# Masters_Project.net
KiCad netlist of a schematic drawn in EAGLE
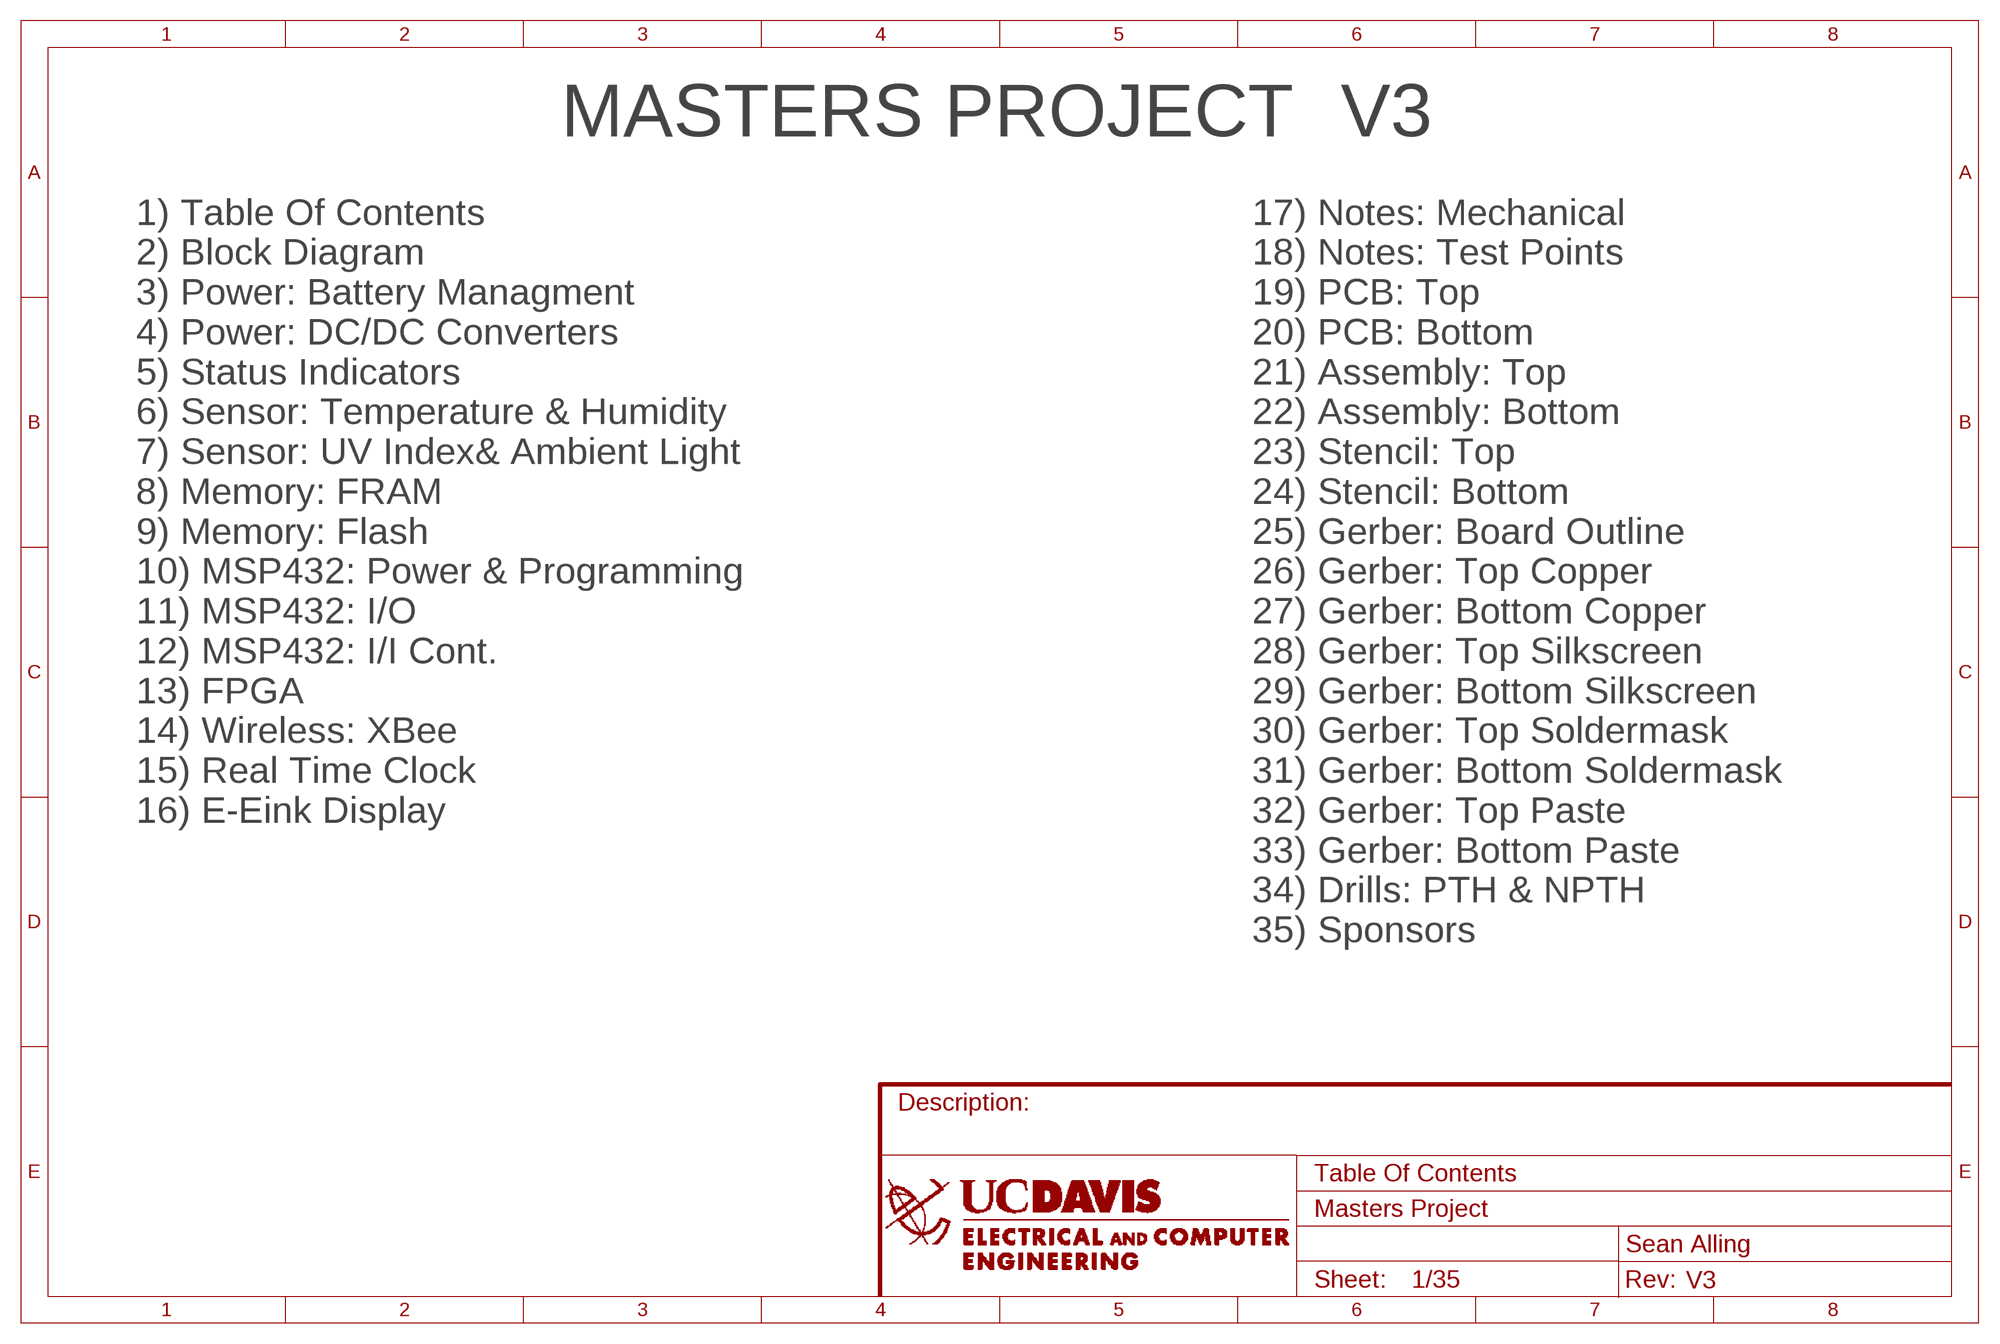
[diagram p0: schematic, sheet 1]
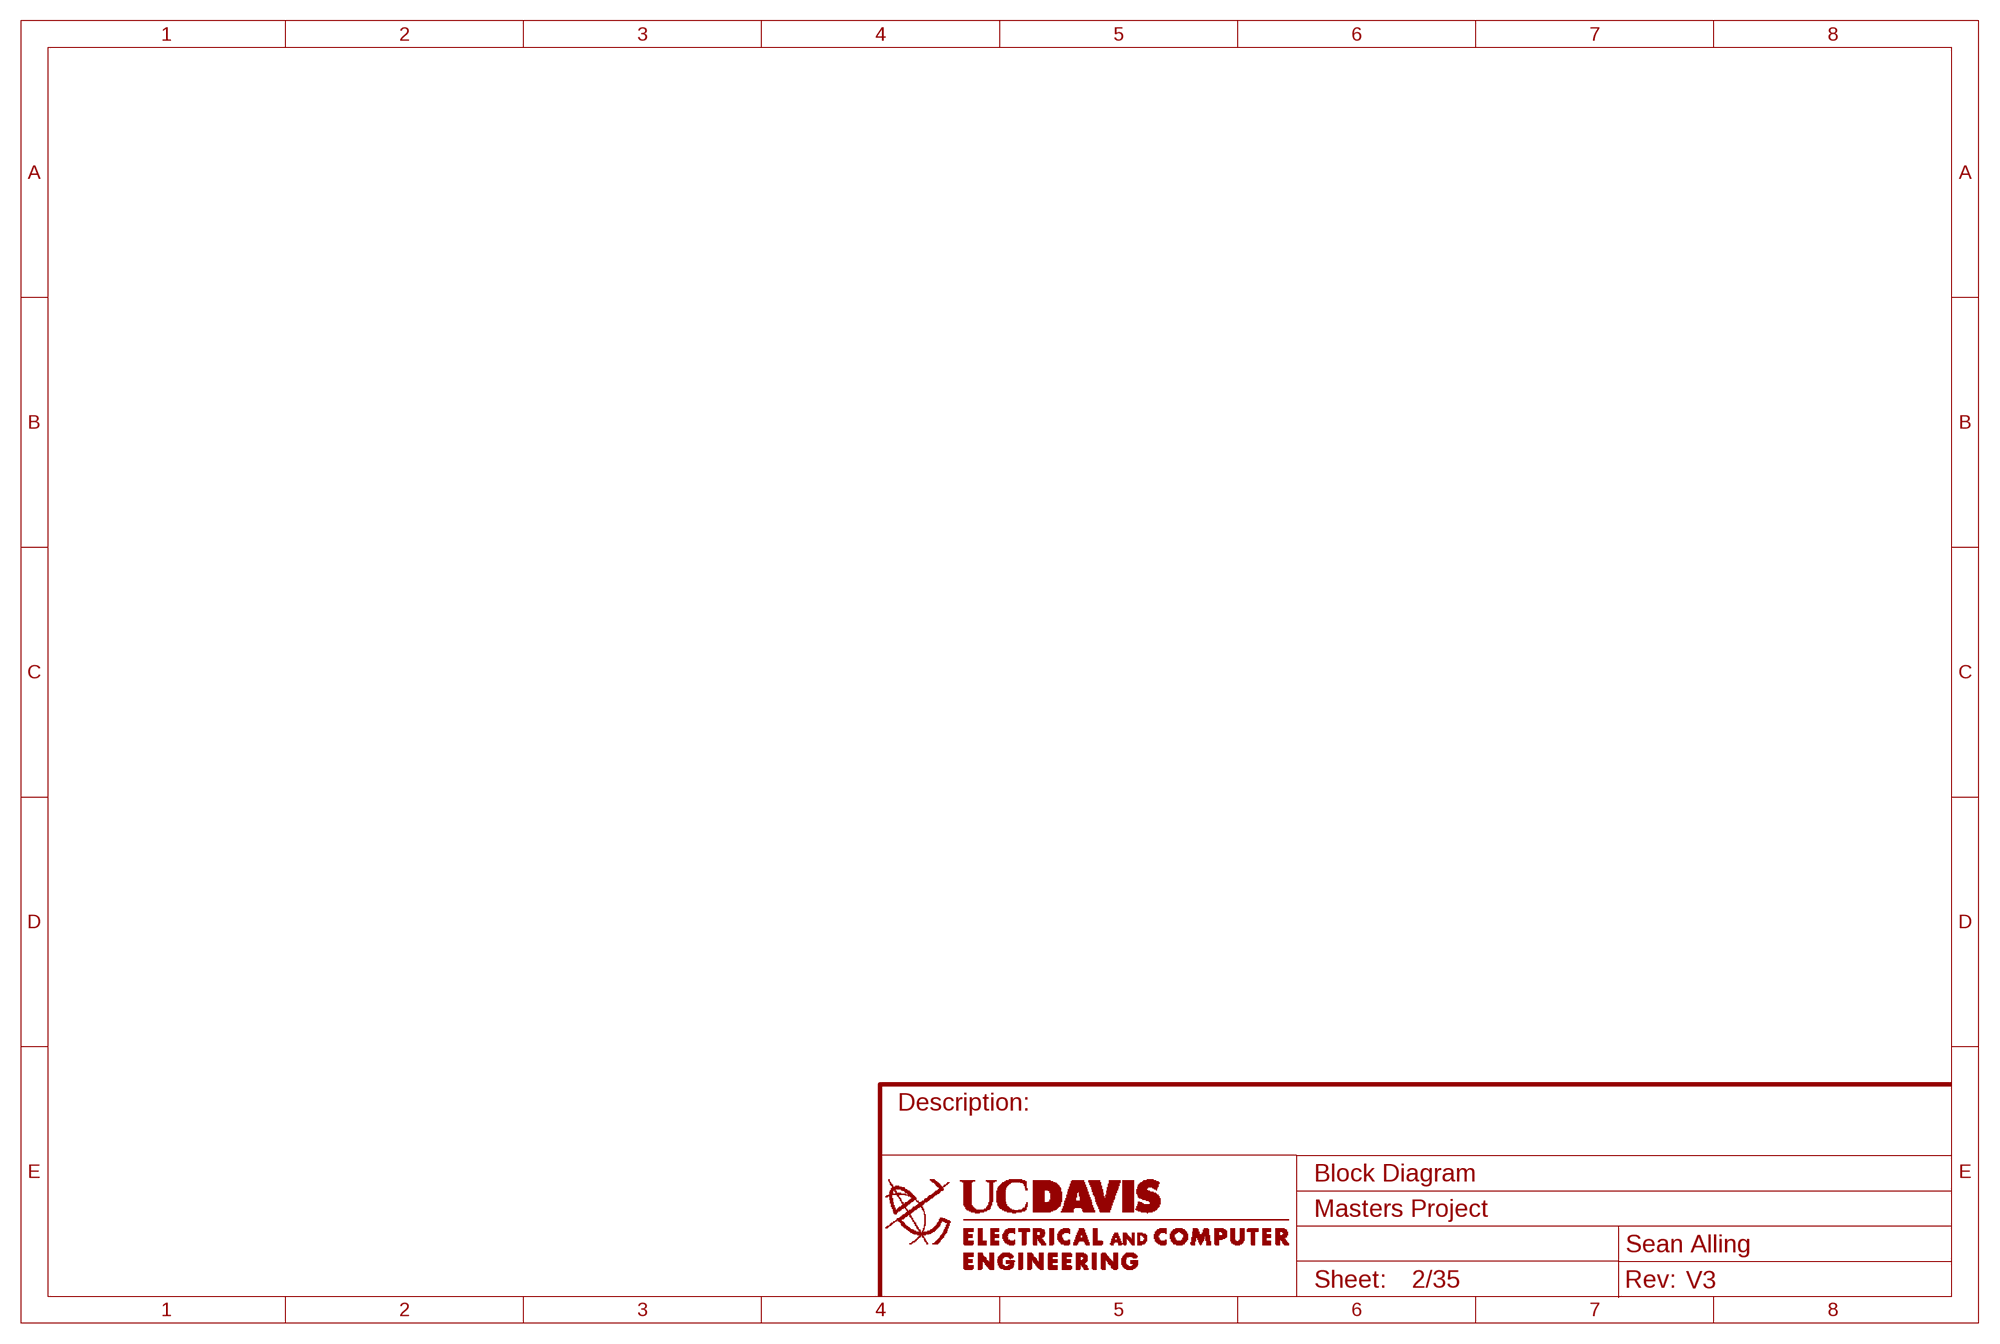
[diagram p1: schematic, sheet 2]
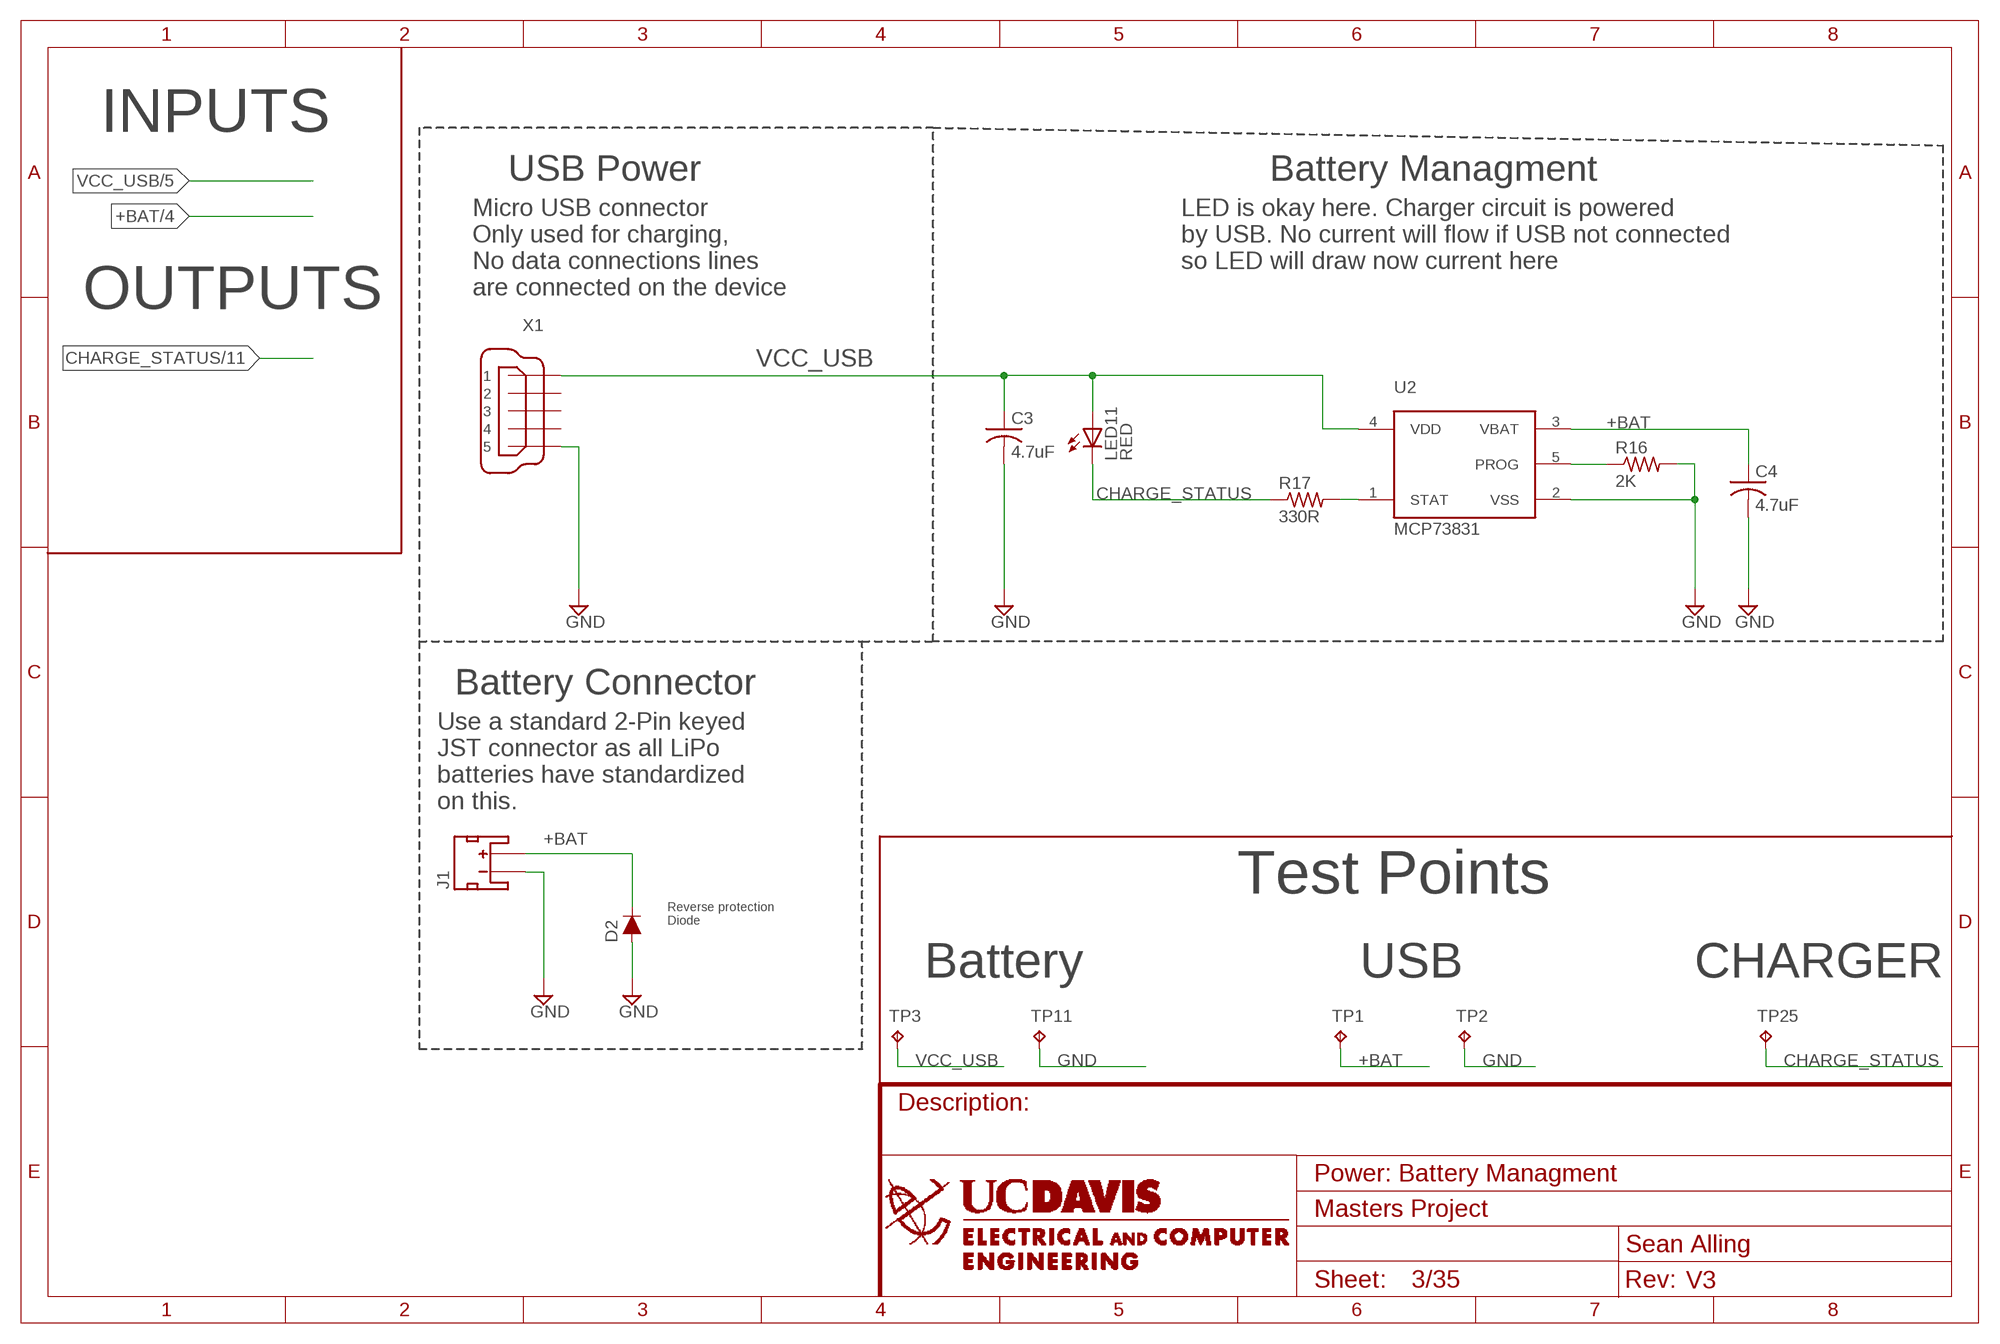
[diagram p2: schematic, sheet 3]
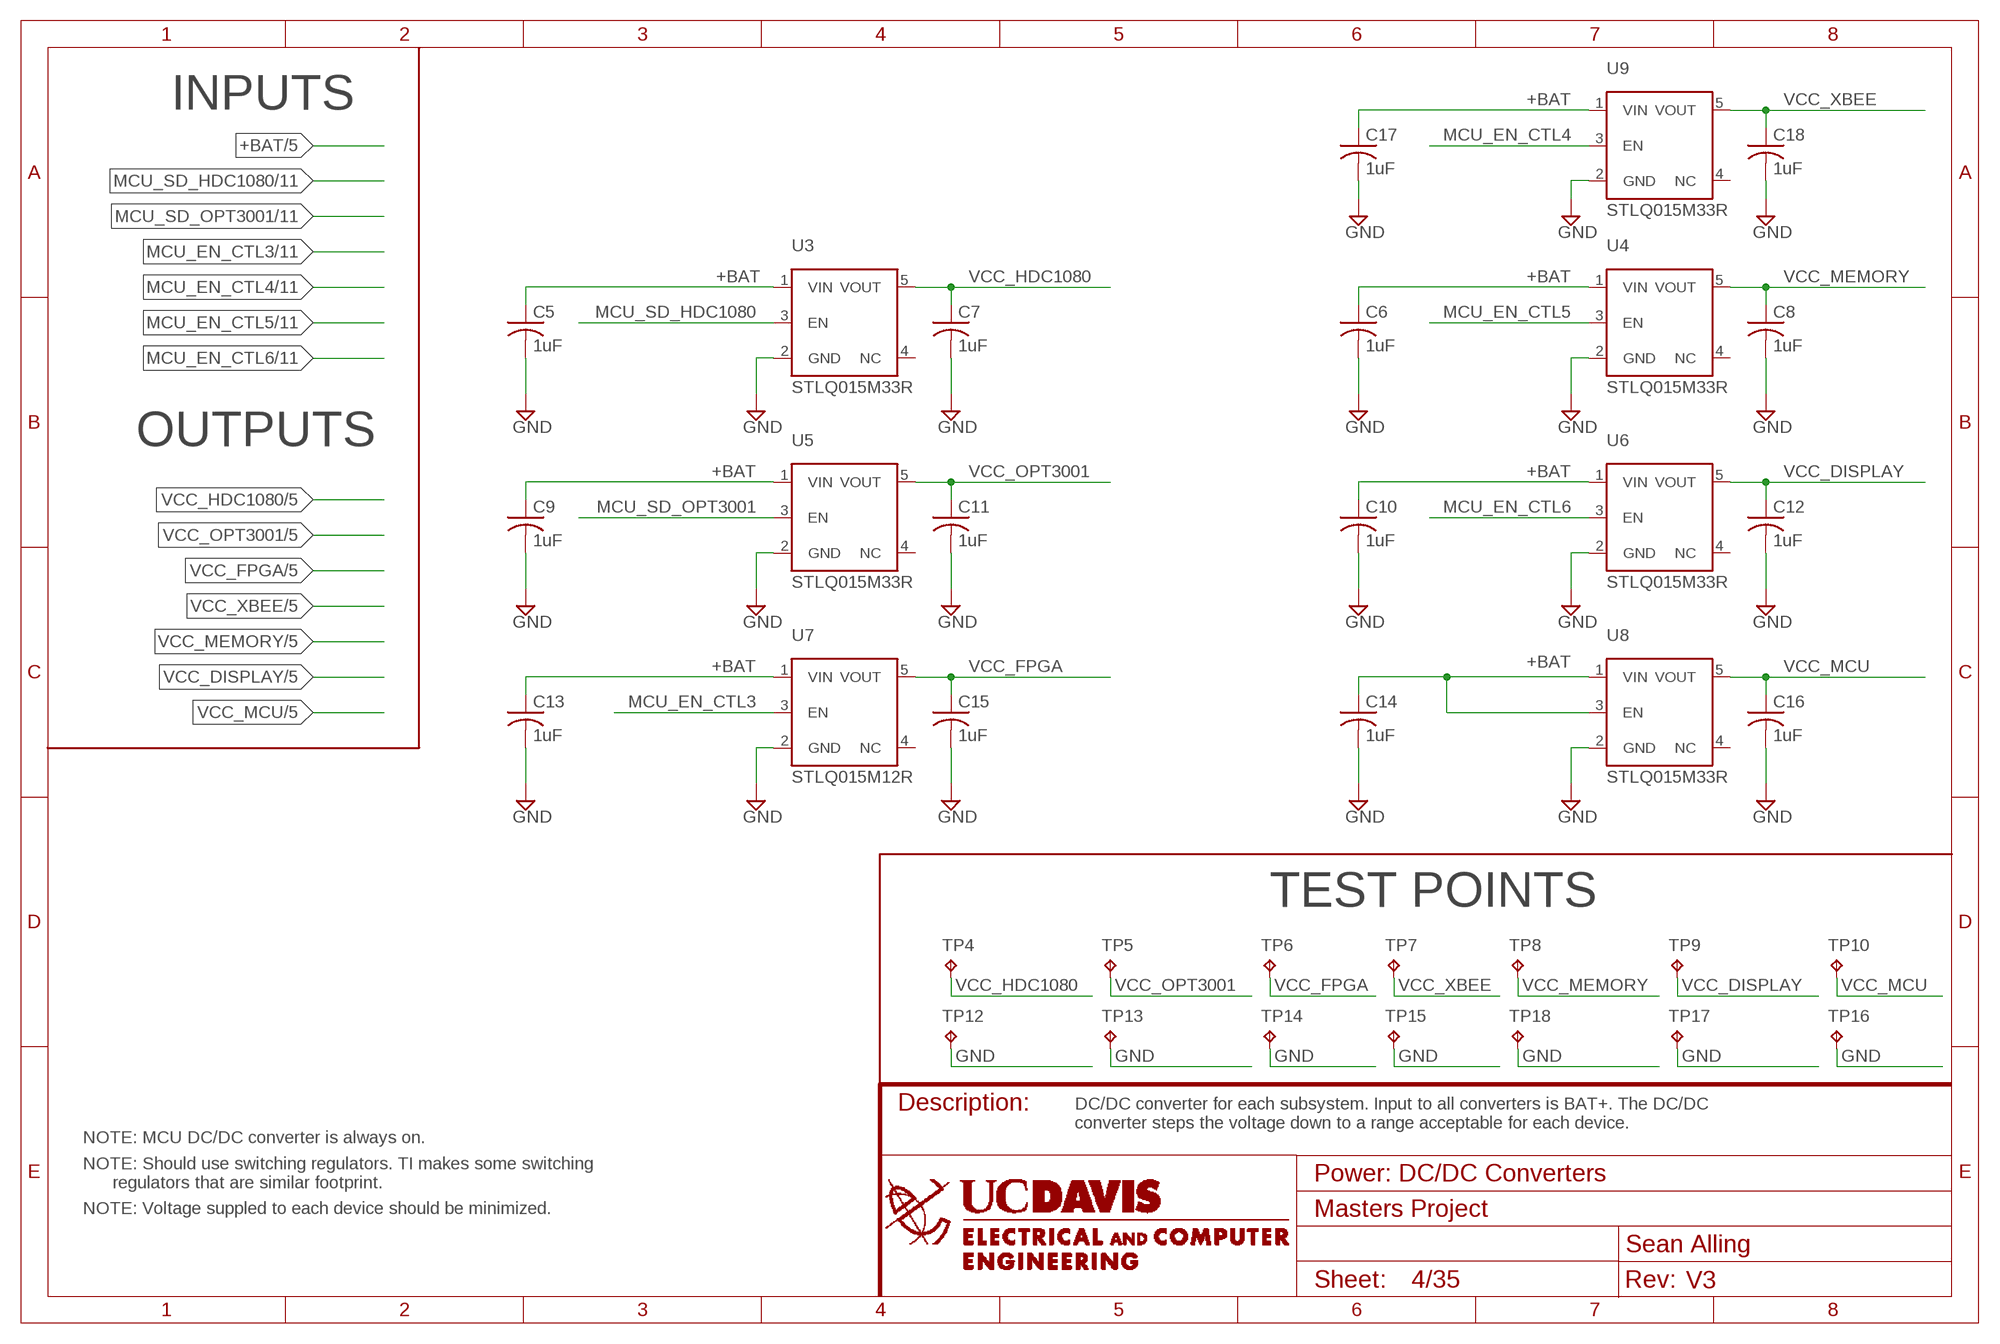
[diagram p3: schematic, sheet 4]
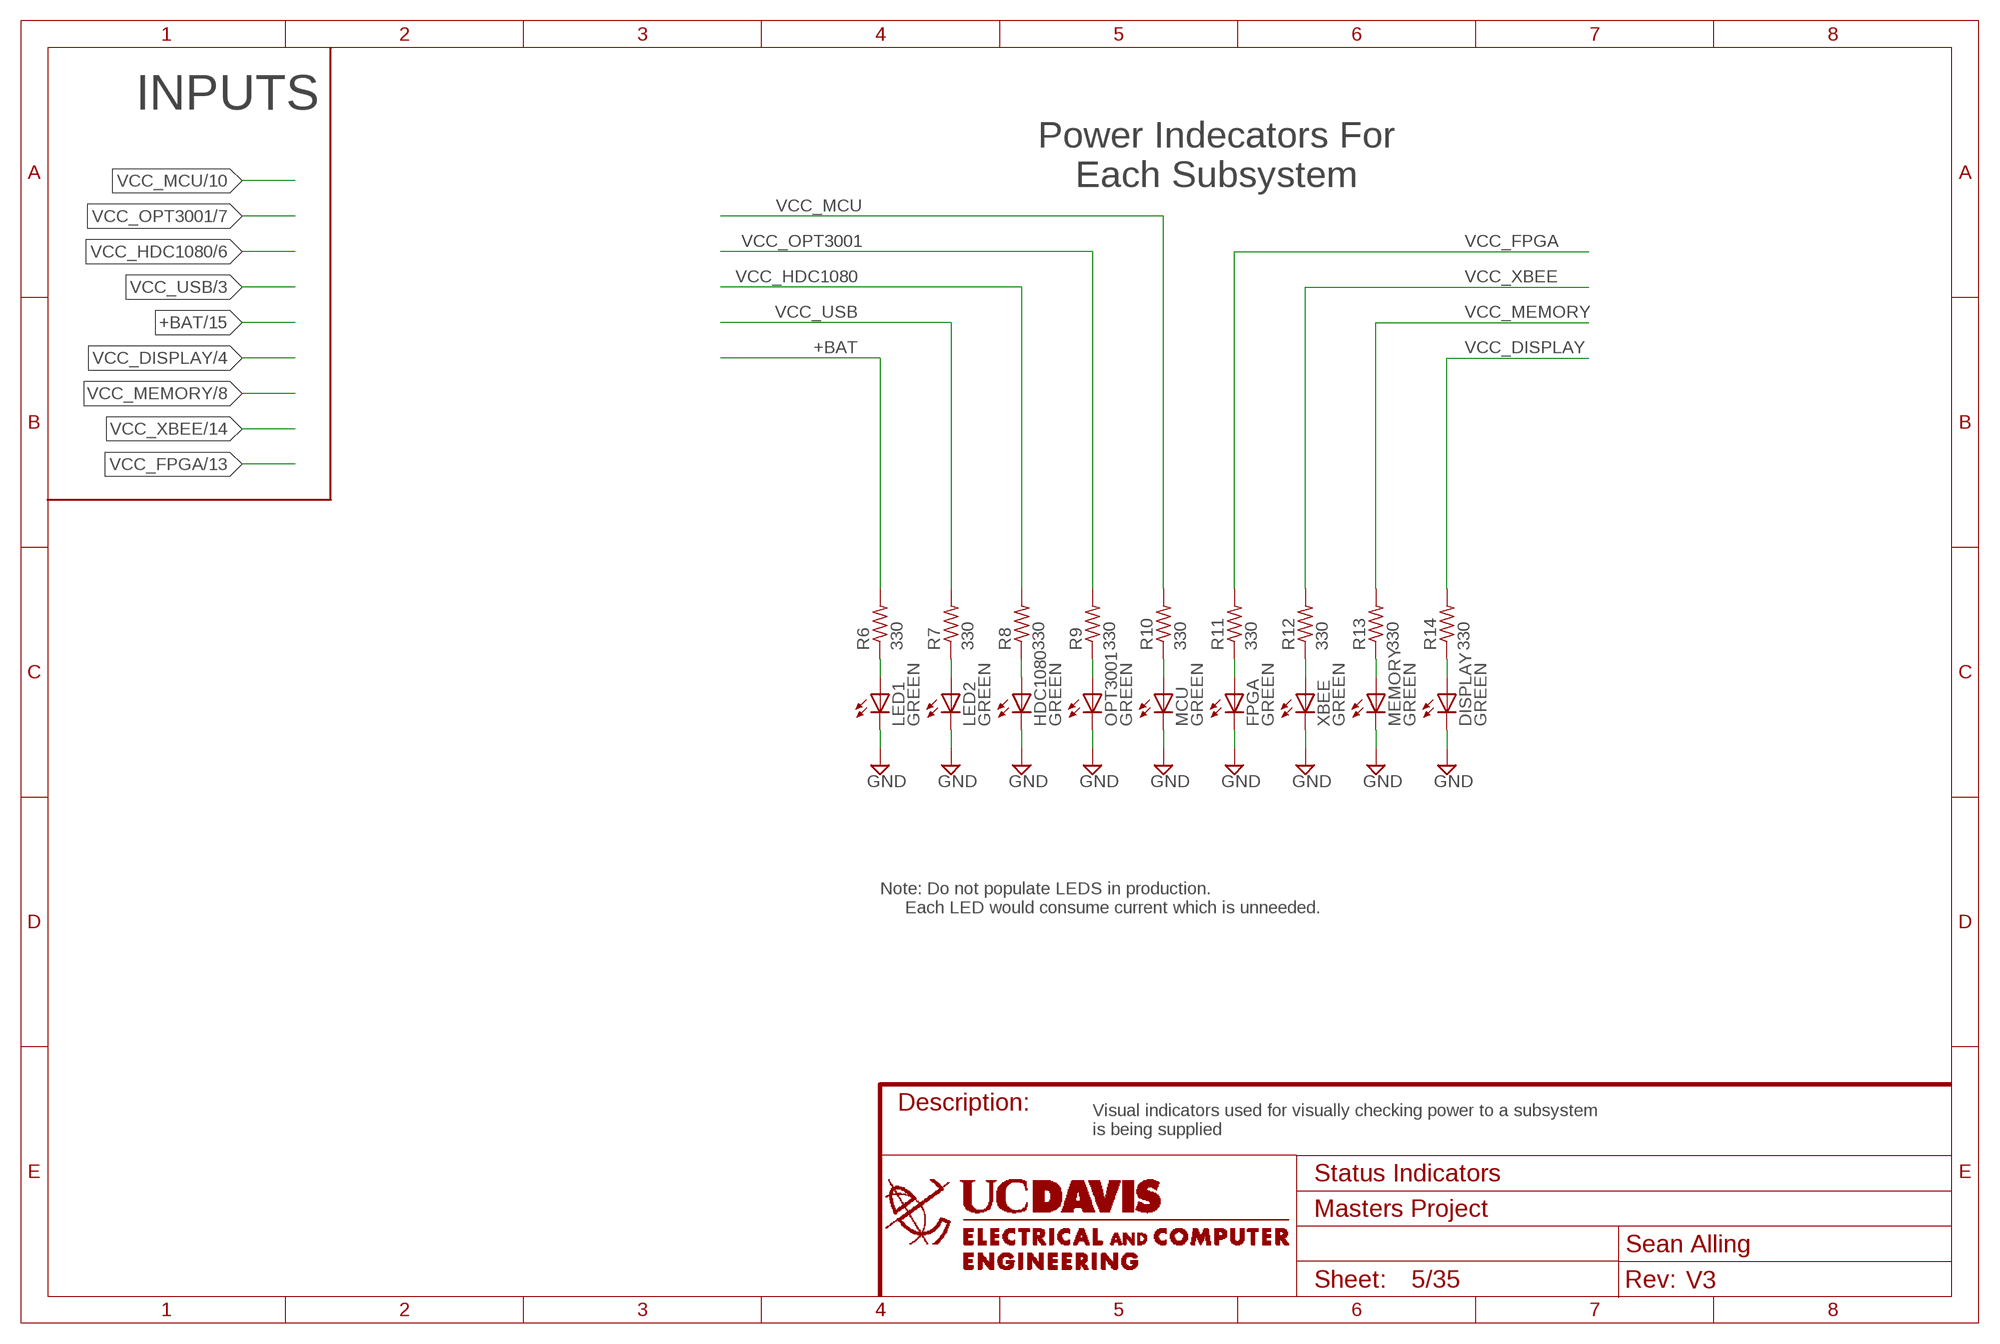
[diagram p4: schematic, sheet 5]
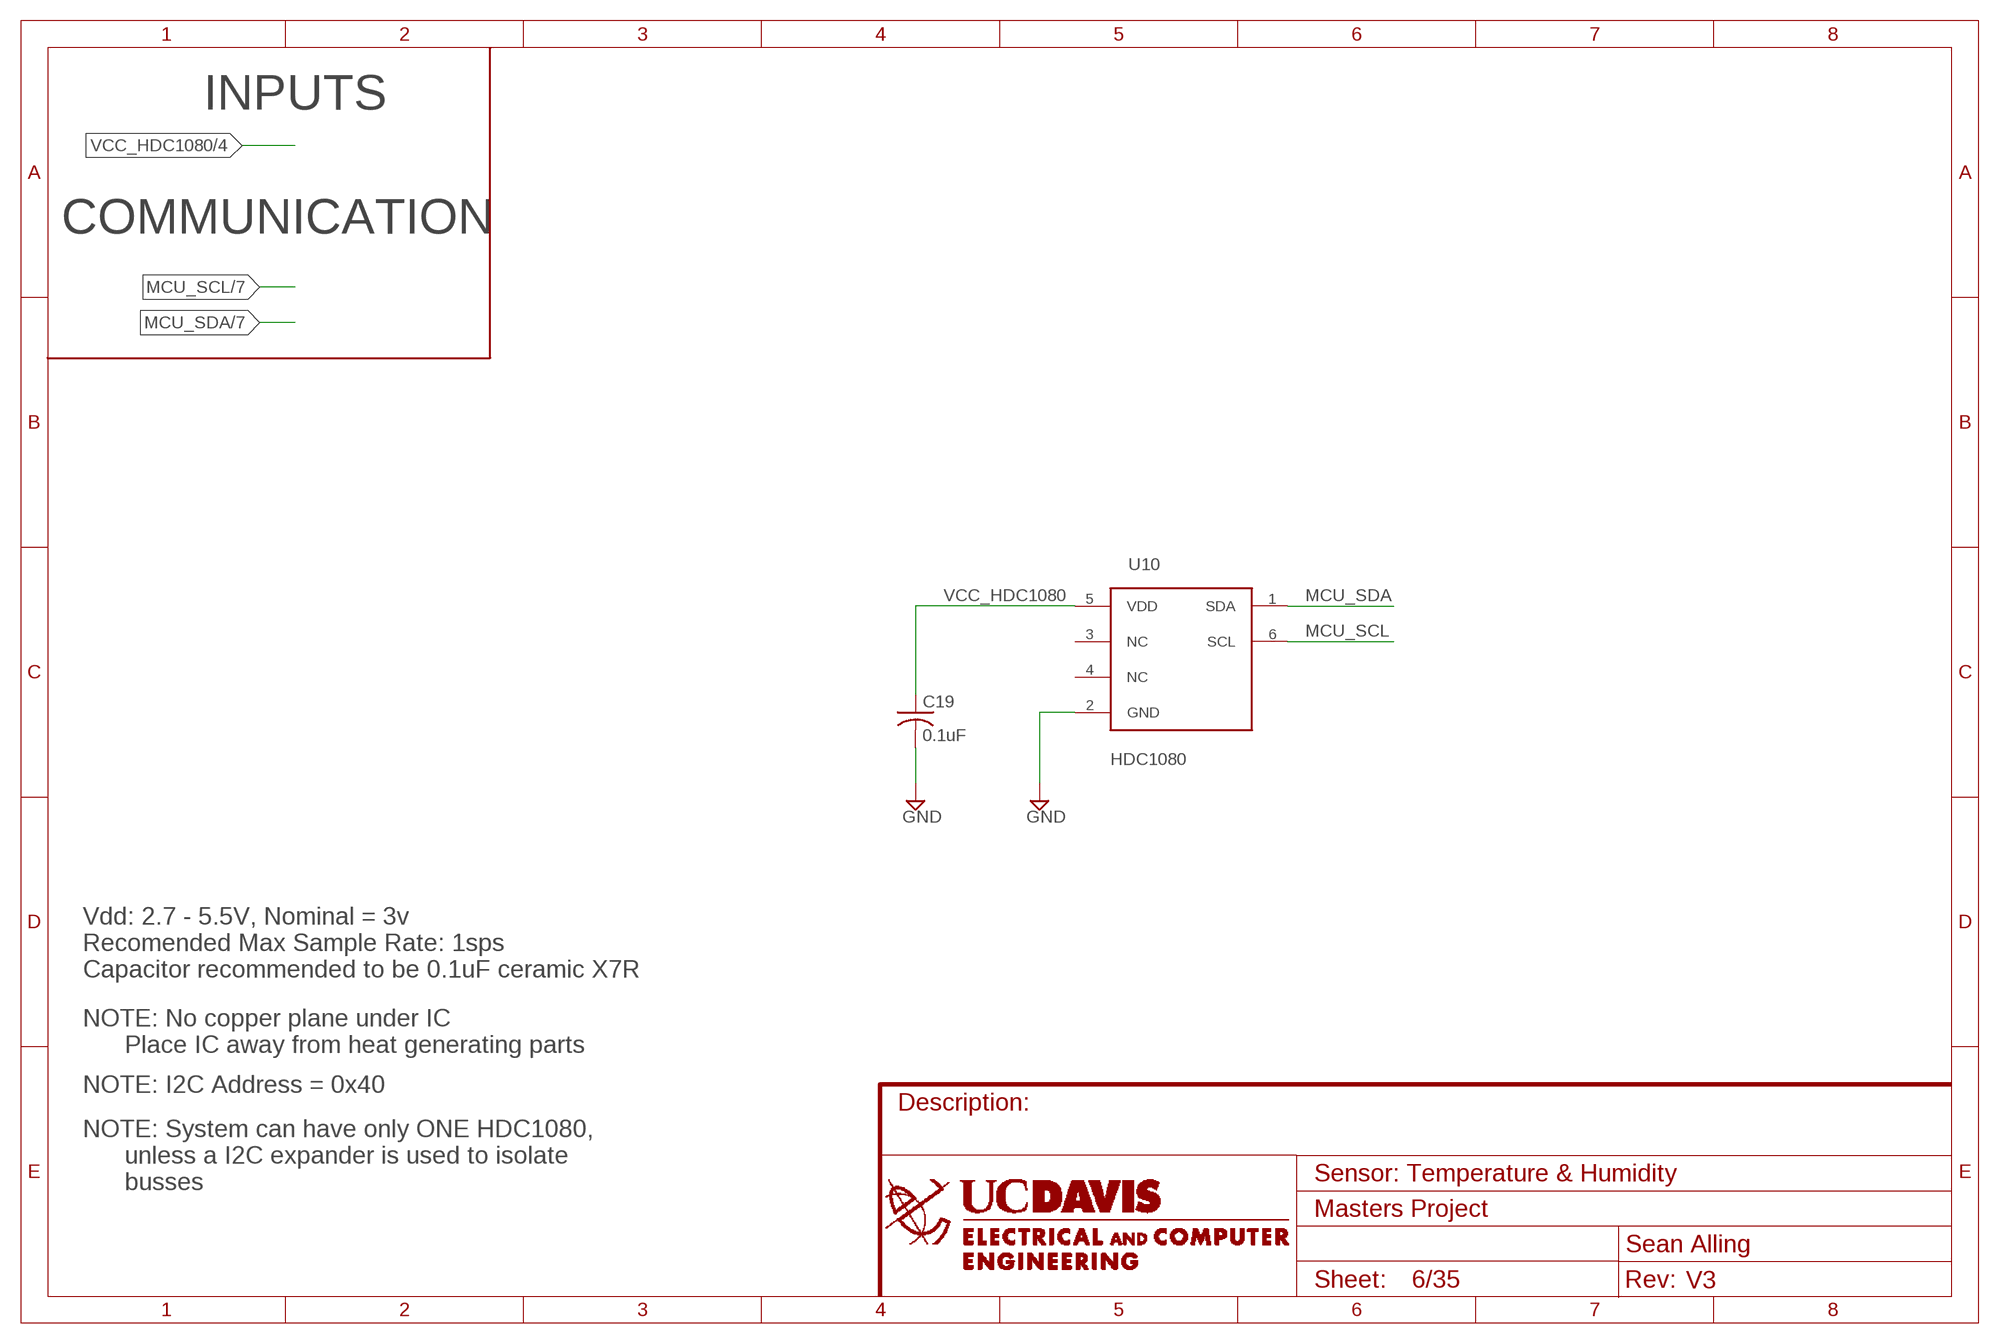
[diagram p5: schematic, sheet 6]
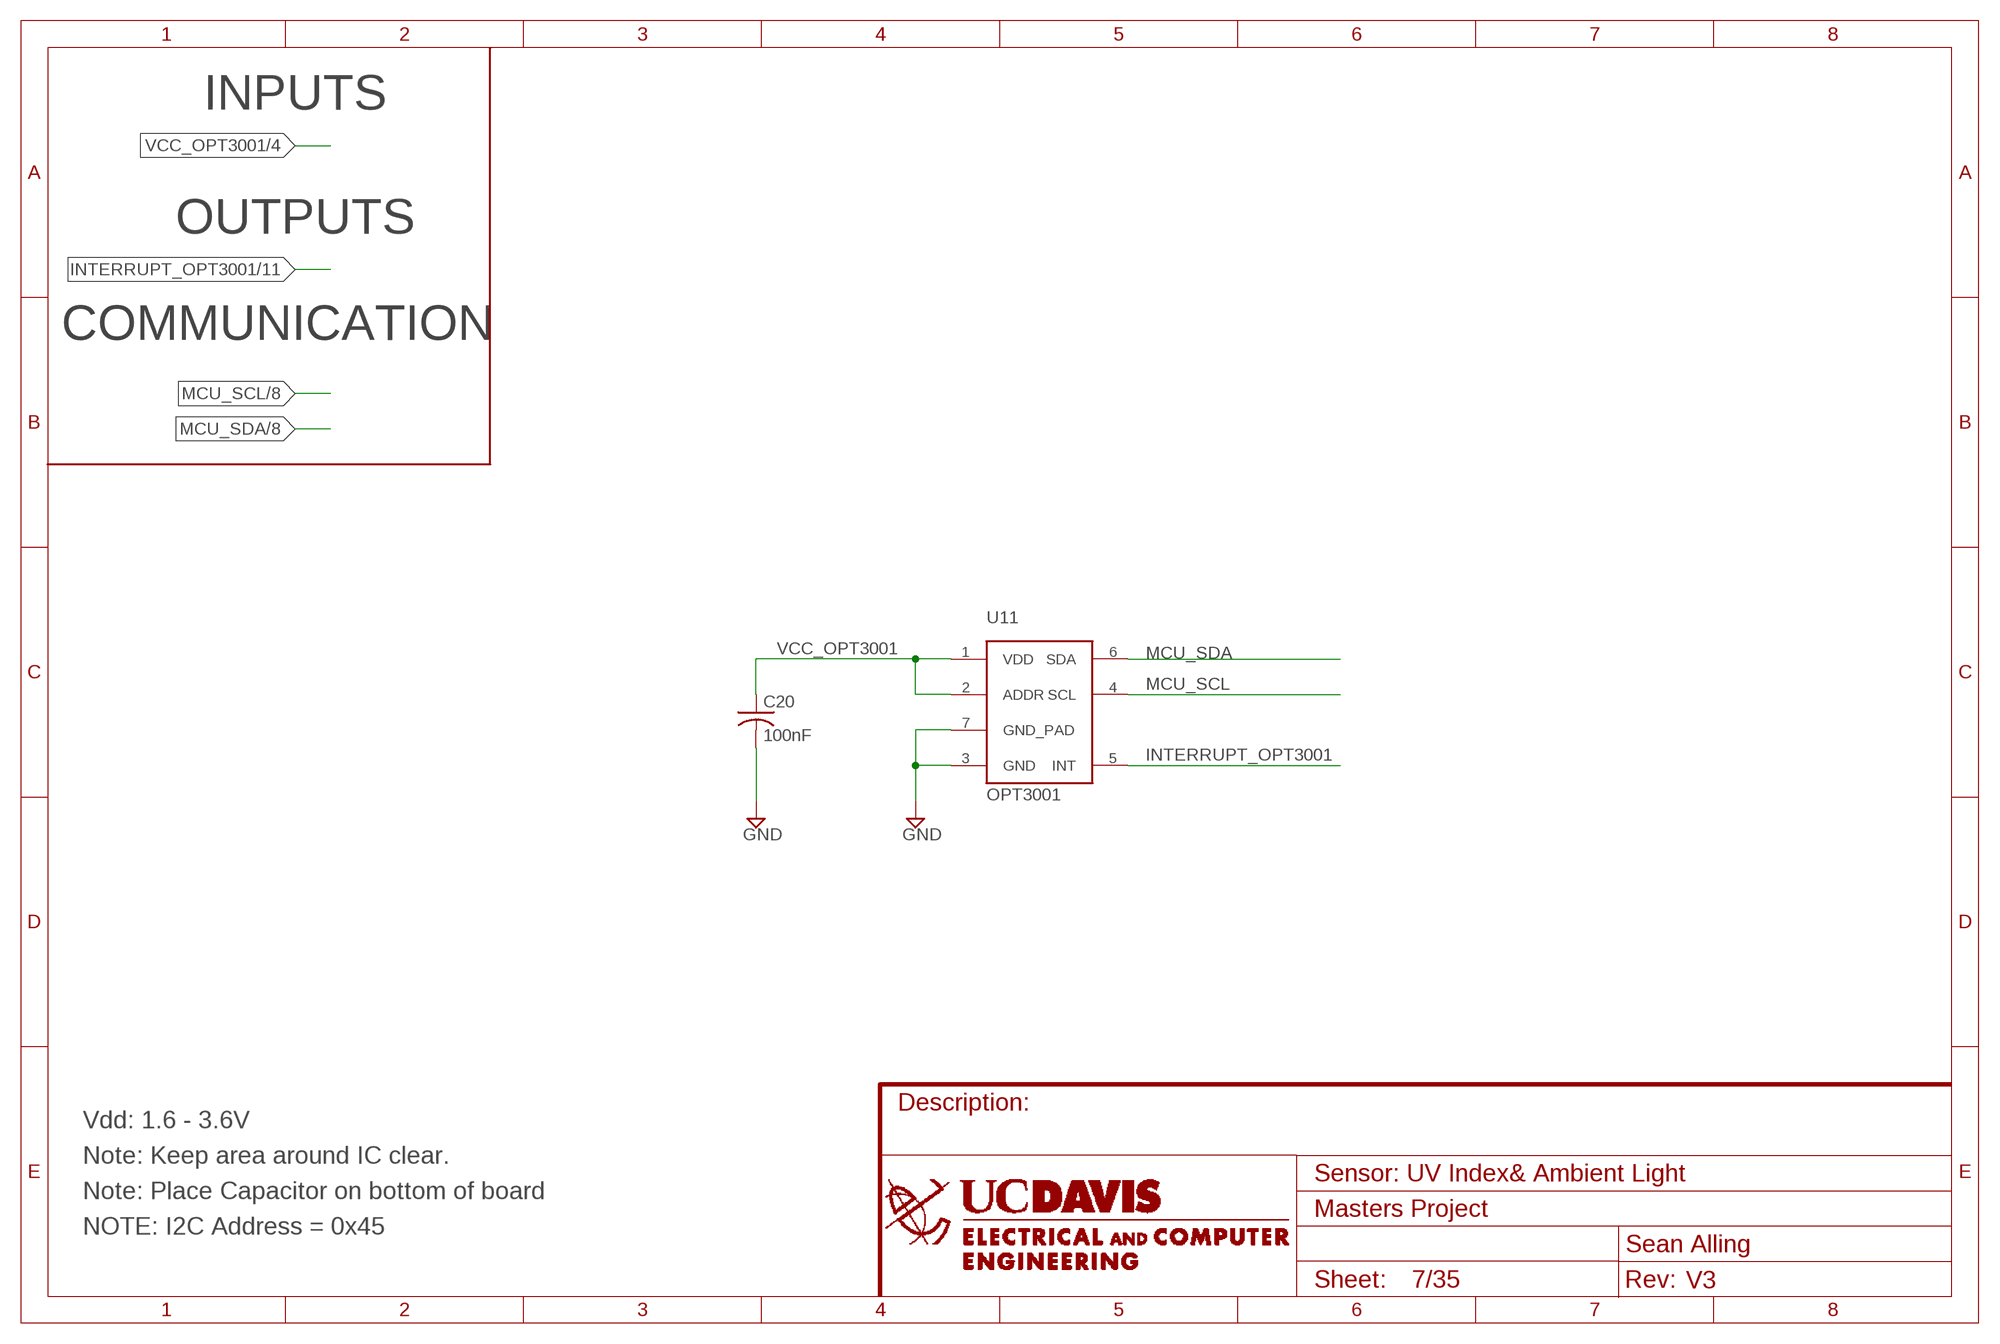
[diagram p6: schematic, sheet 7]
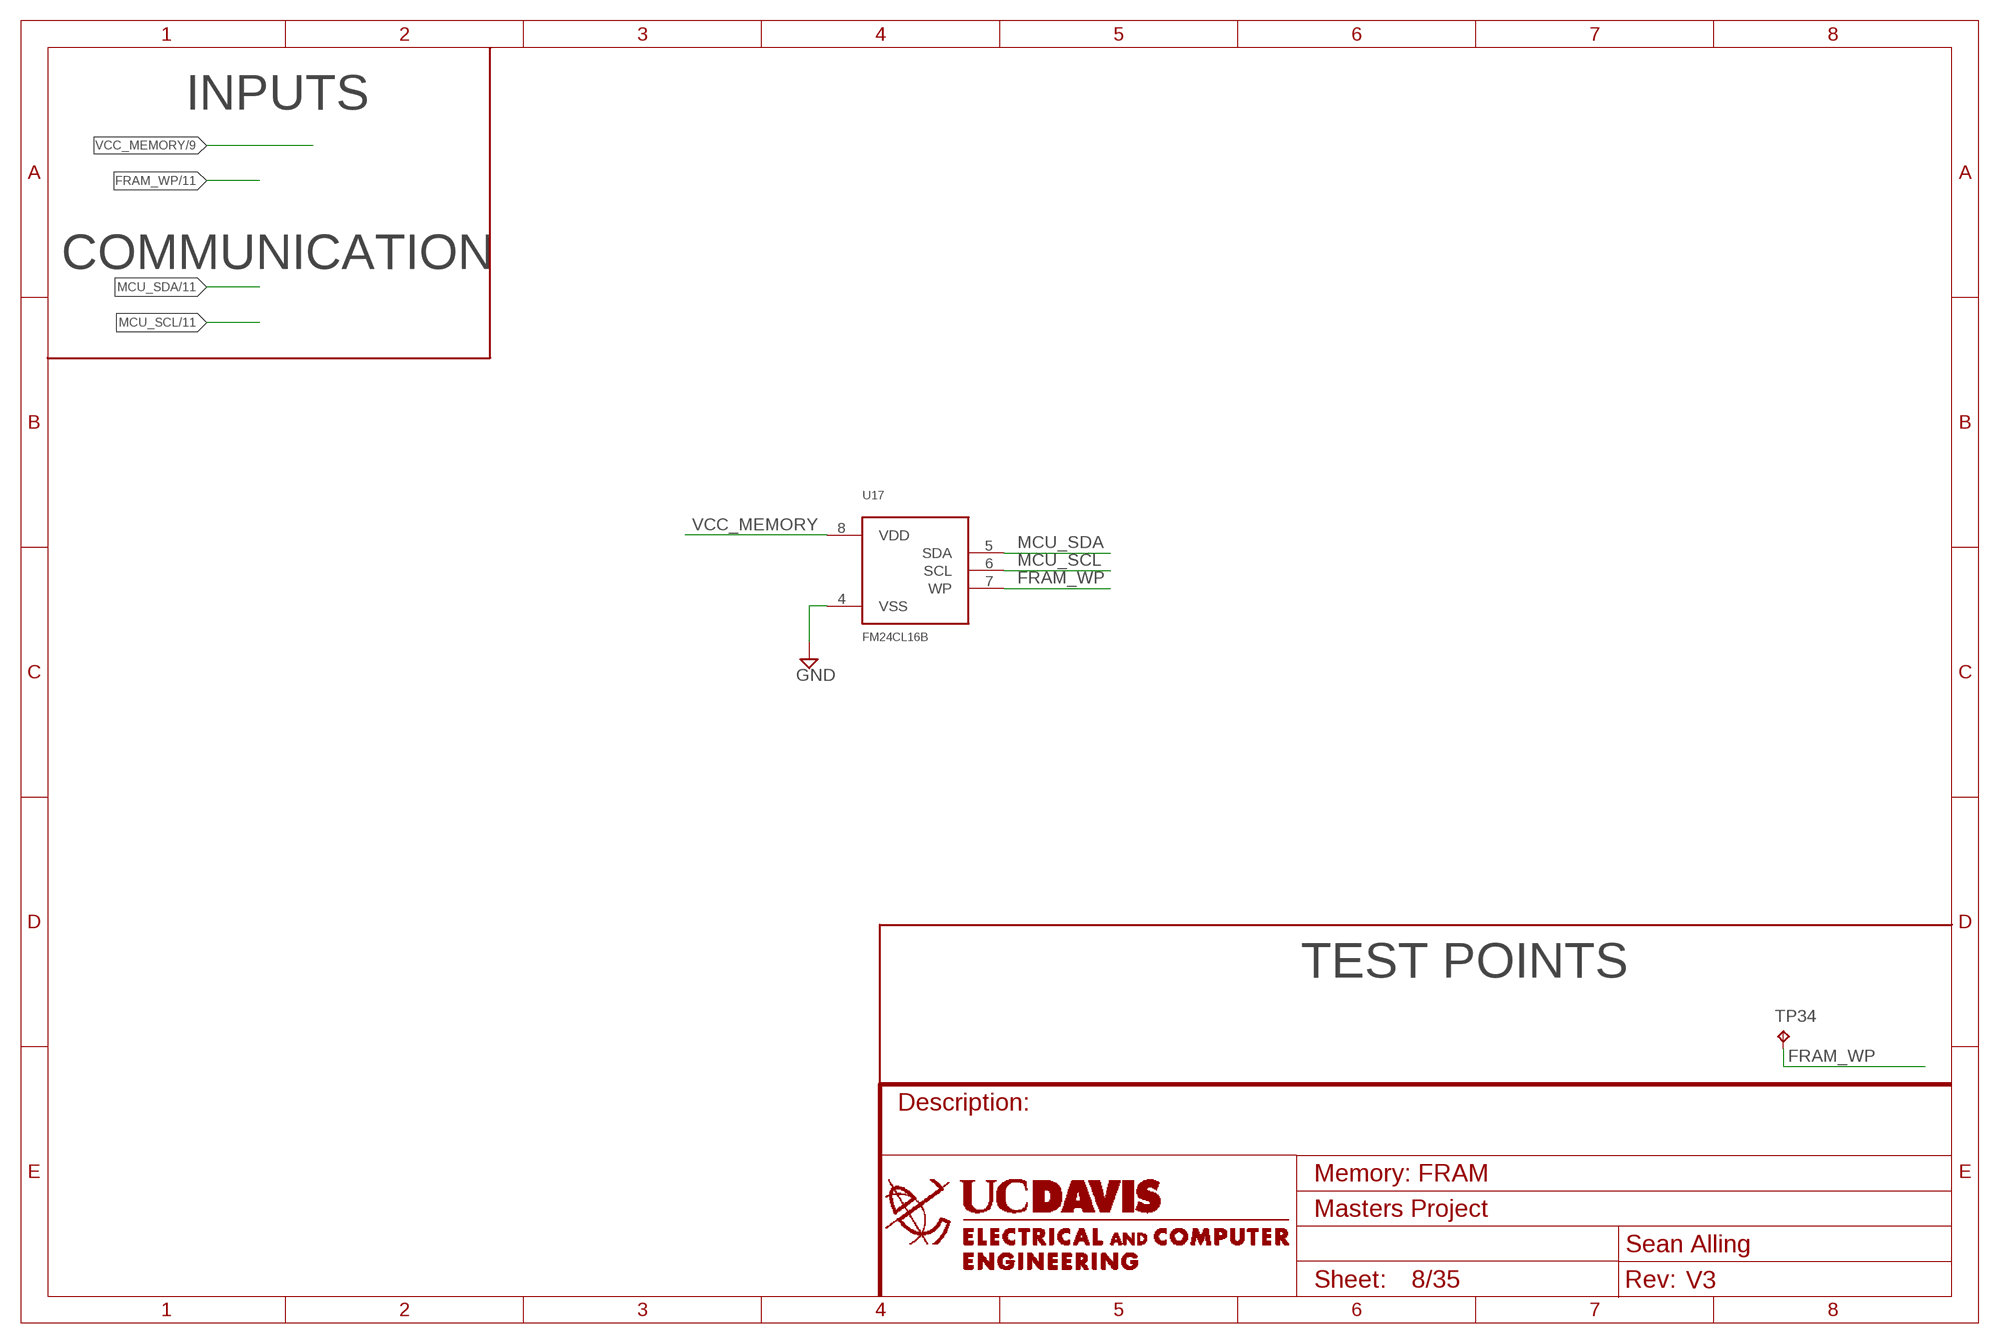
[diagram p7: schematic, sheet 8]
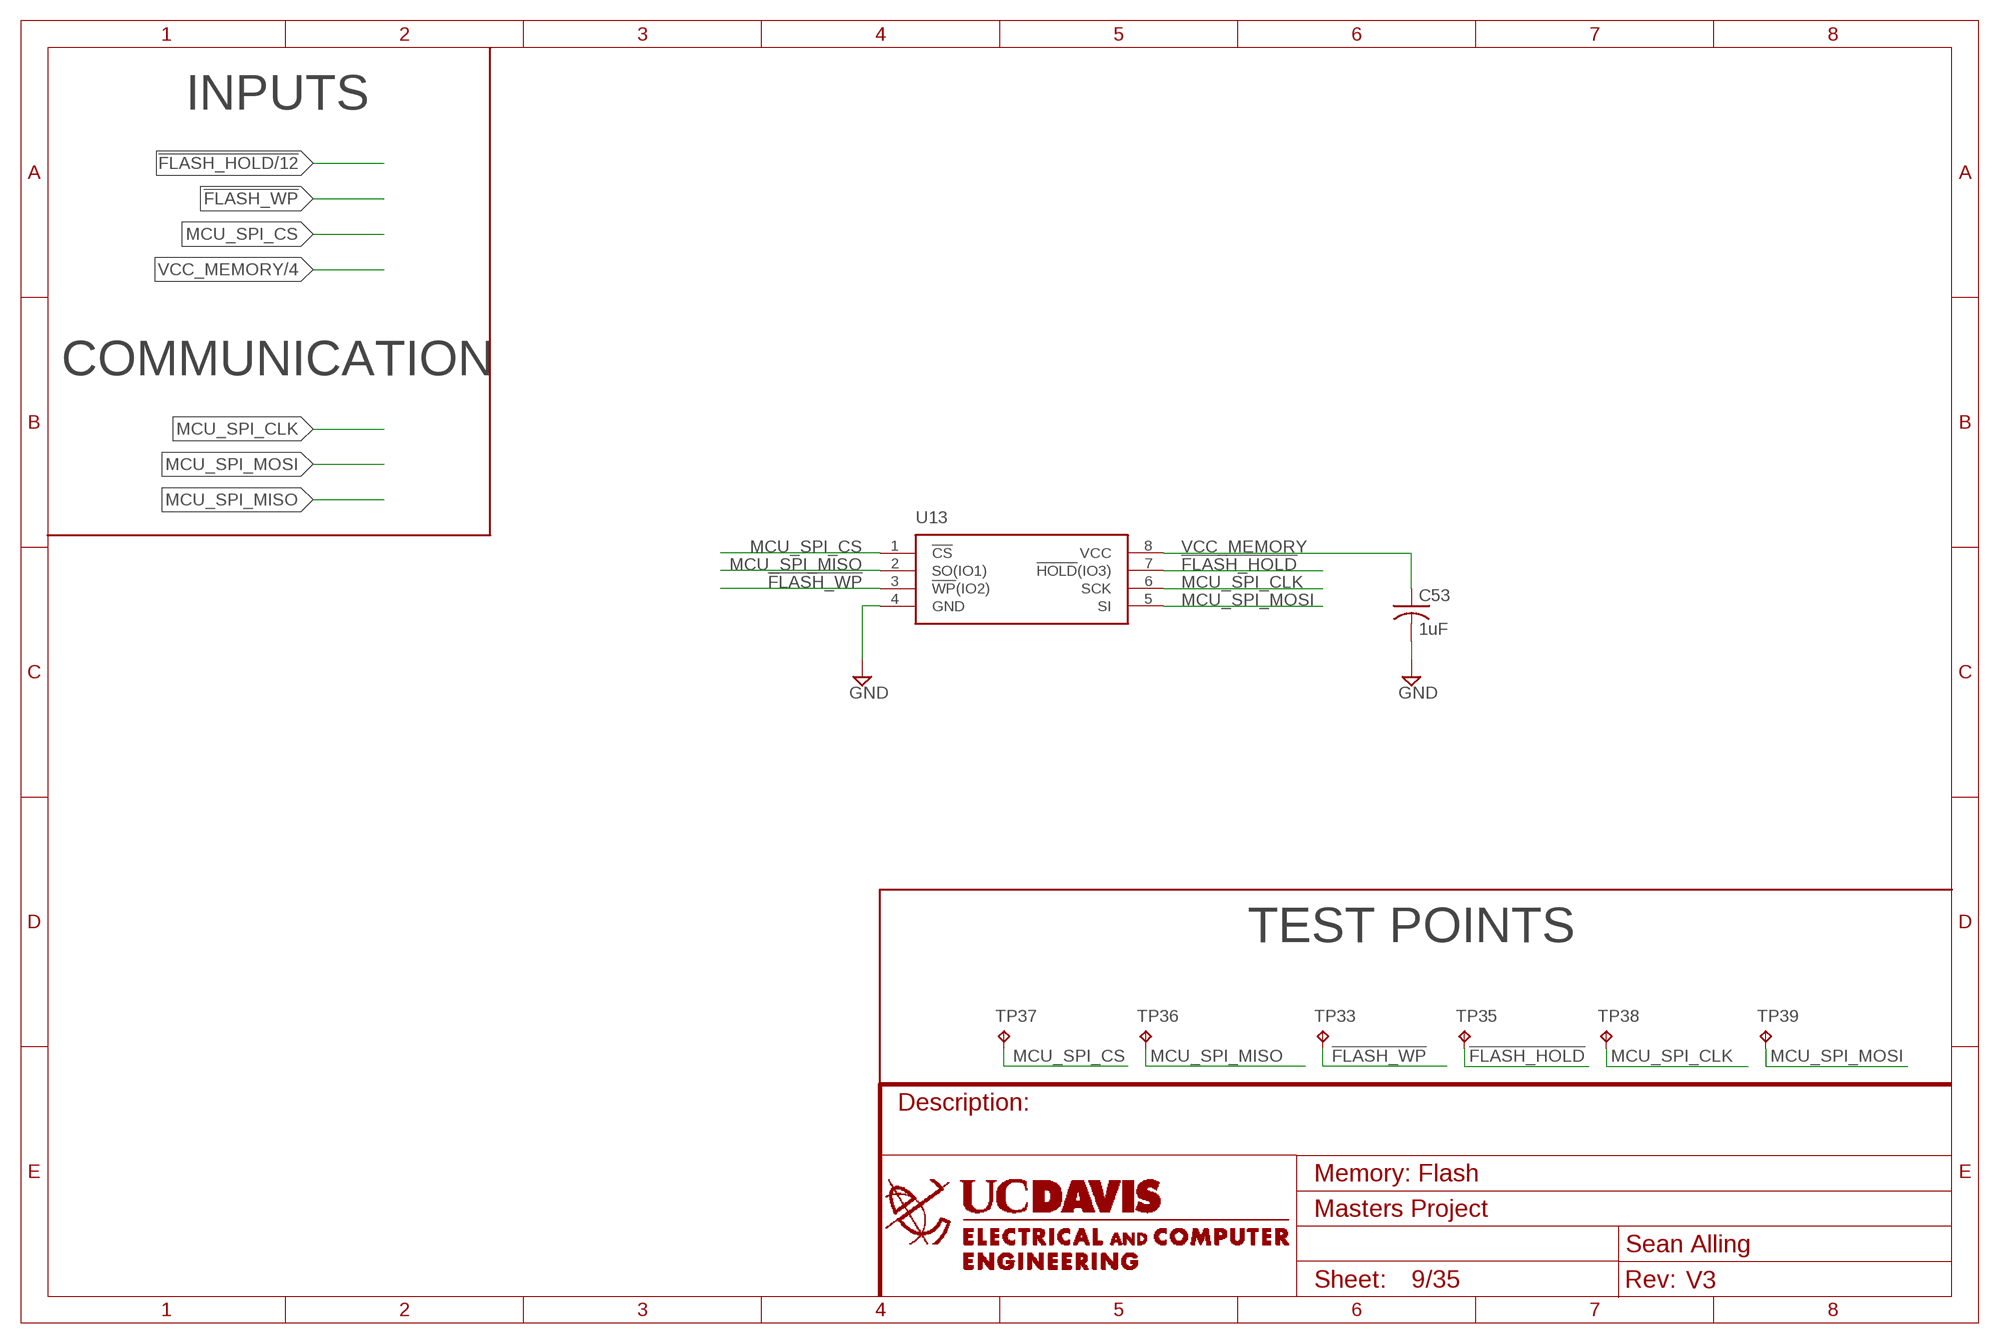
[diagram p8: schematic, sheet 9]
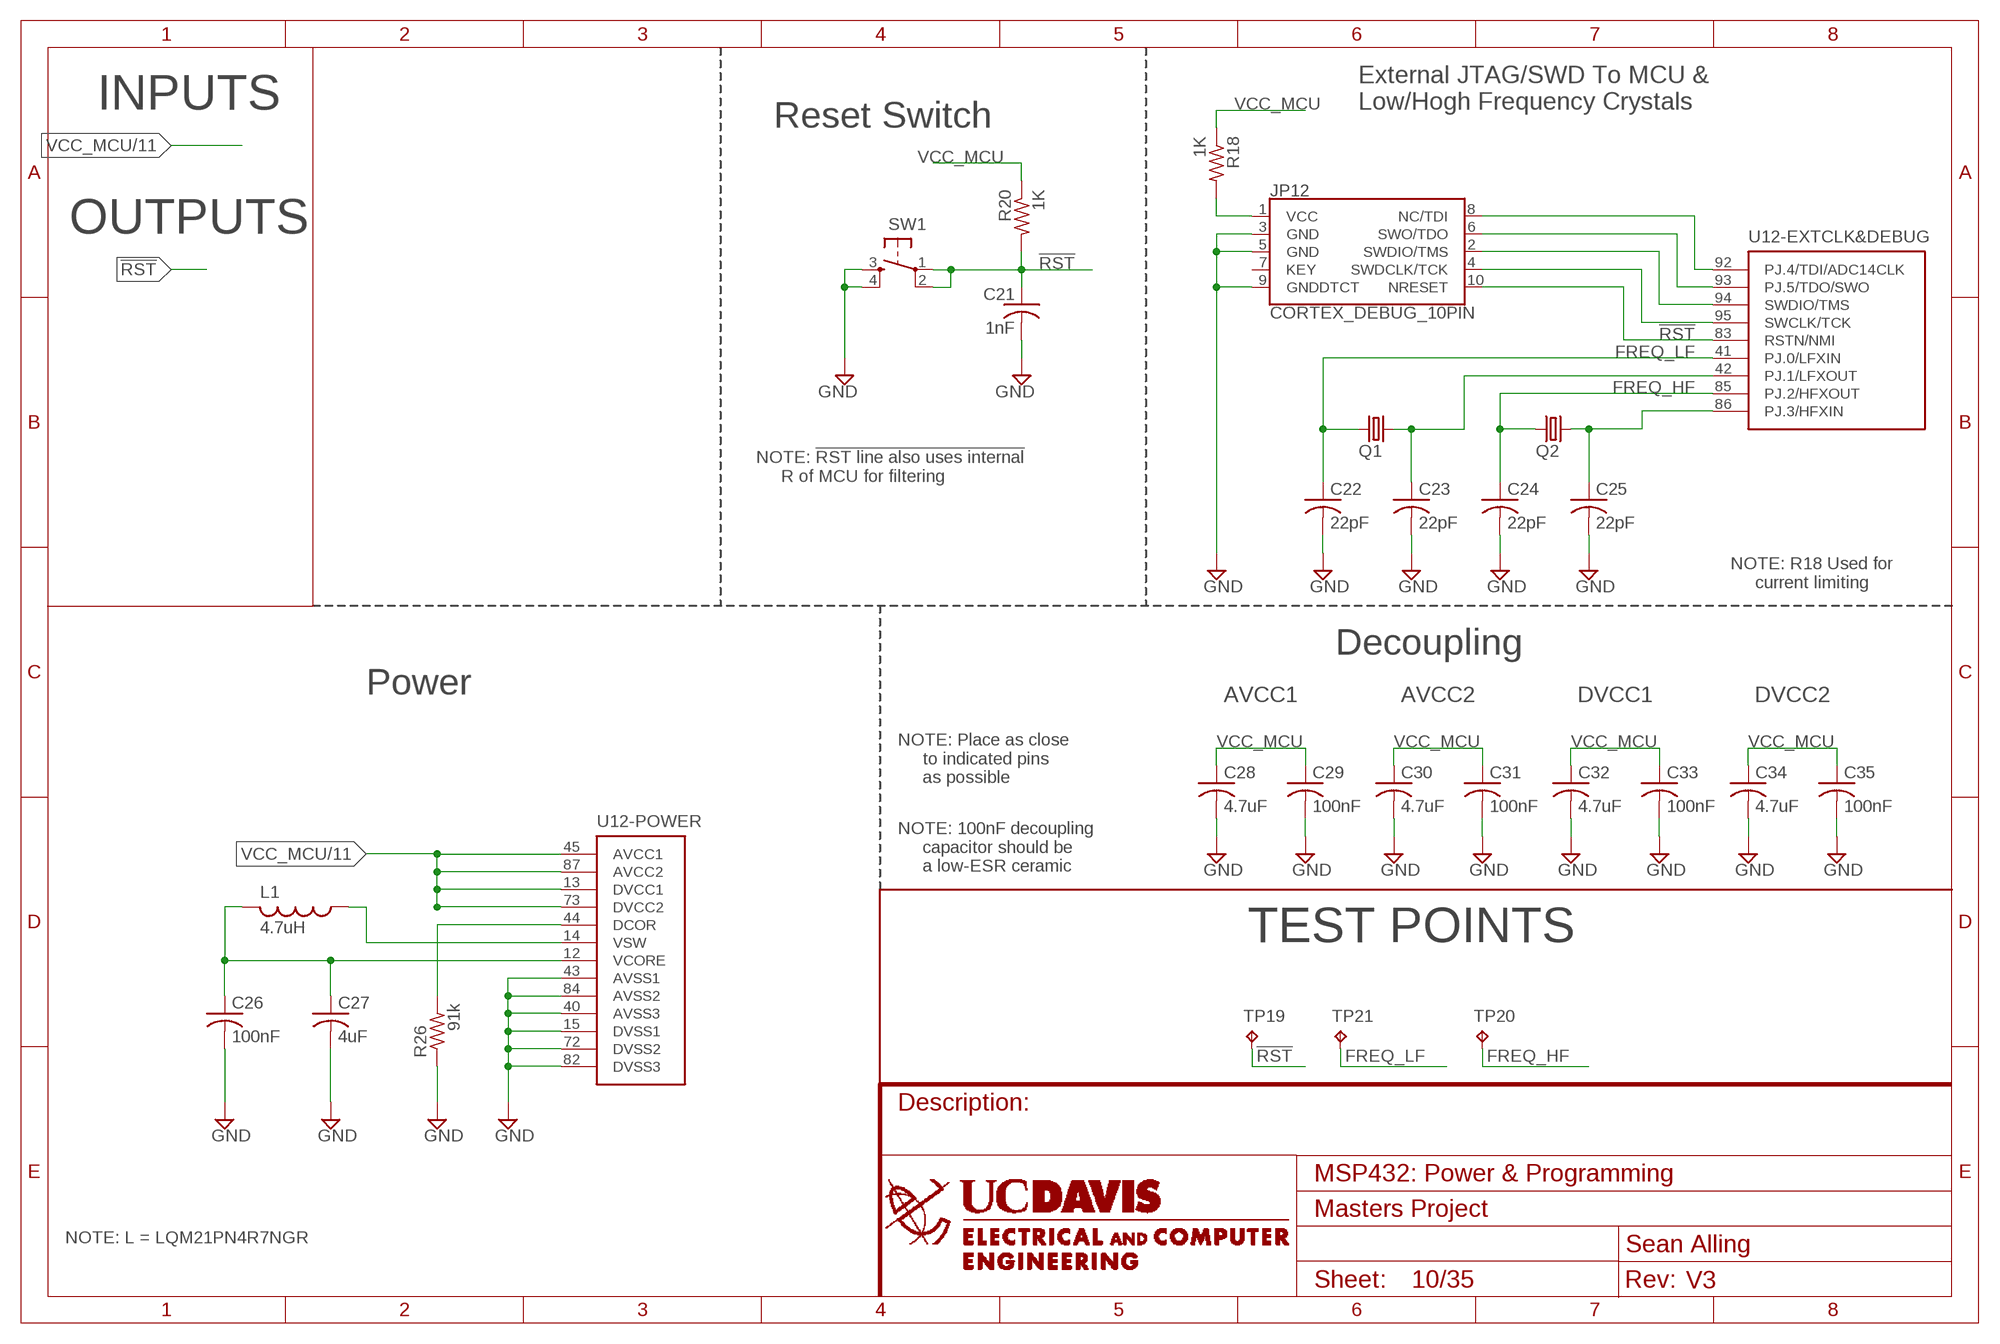
[diagram p9: schematic, sheet 10]
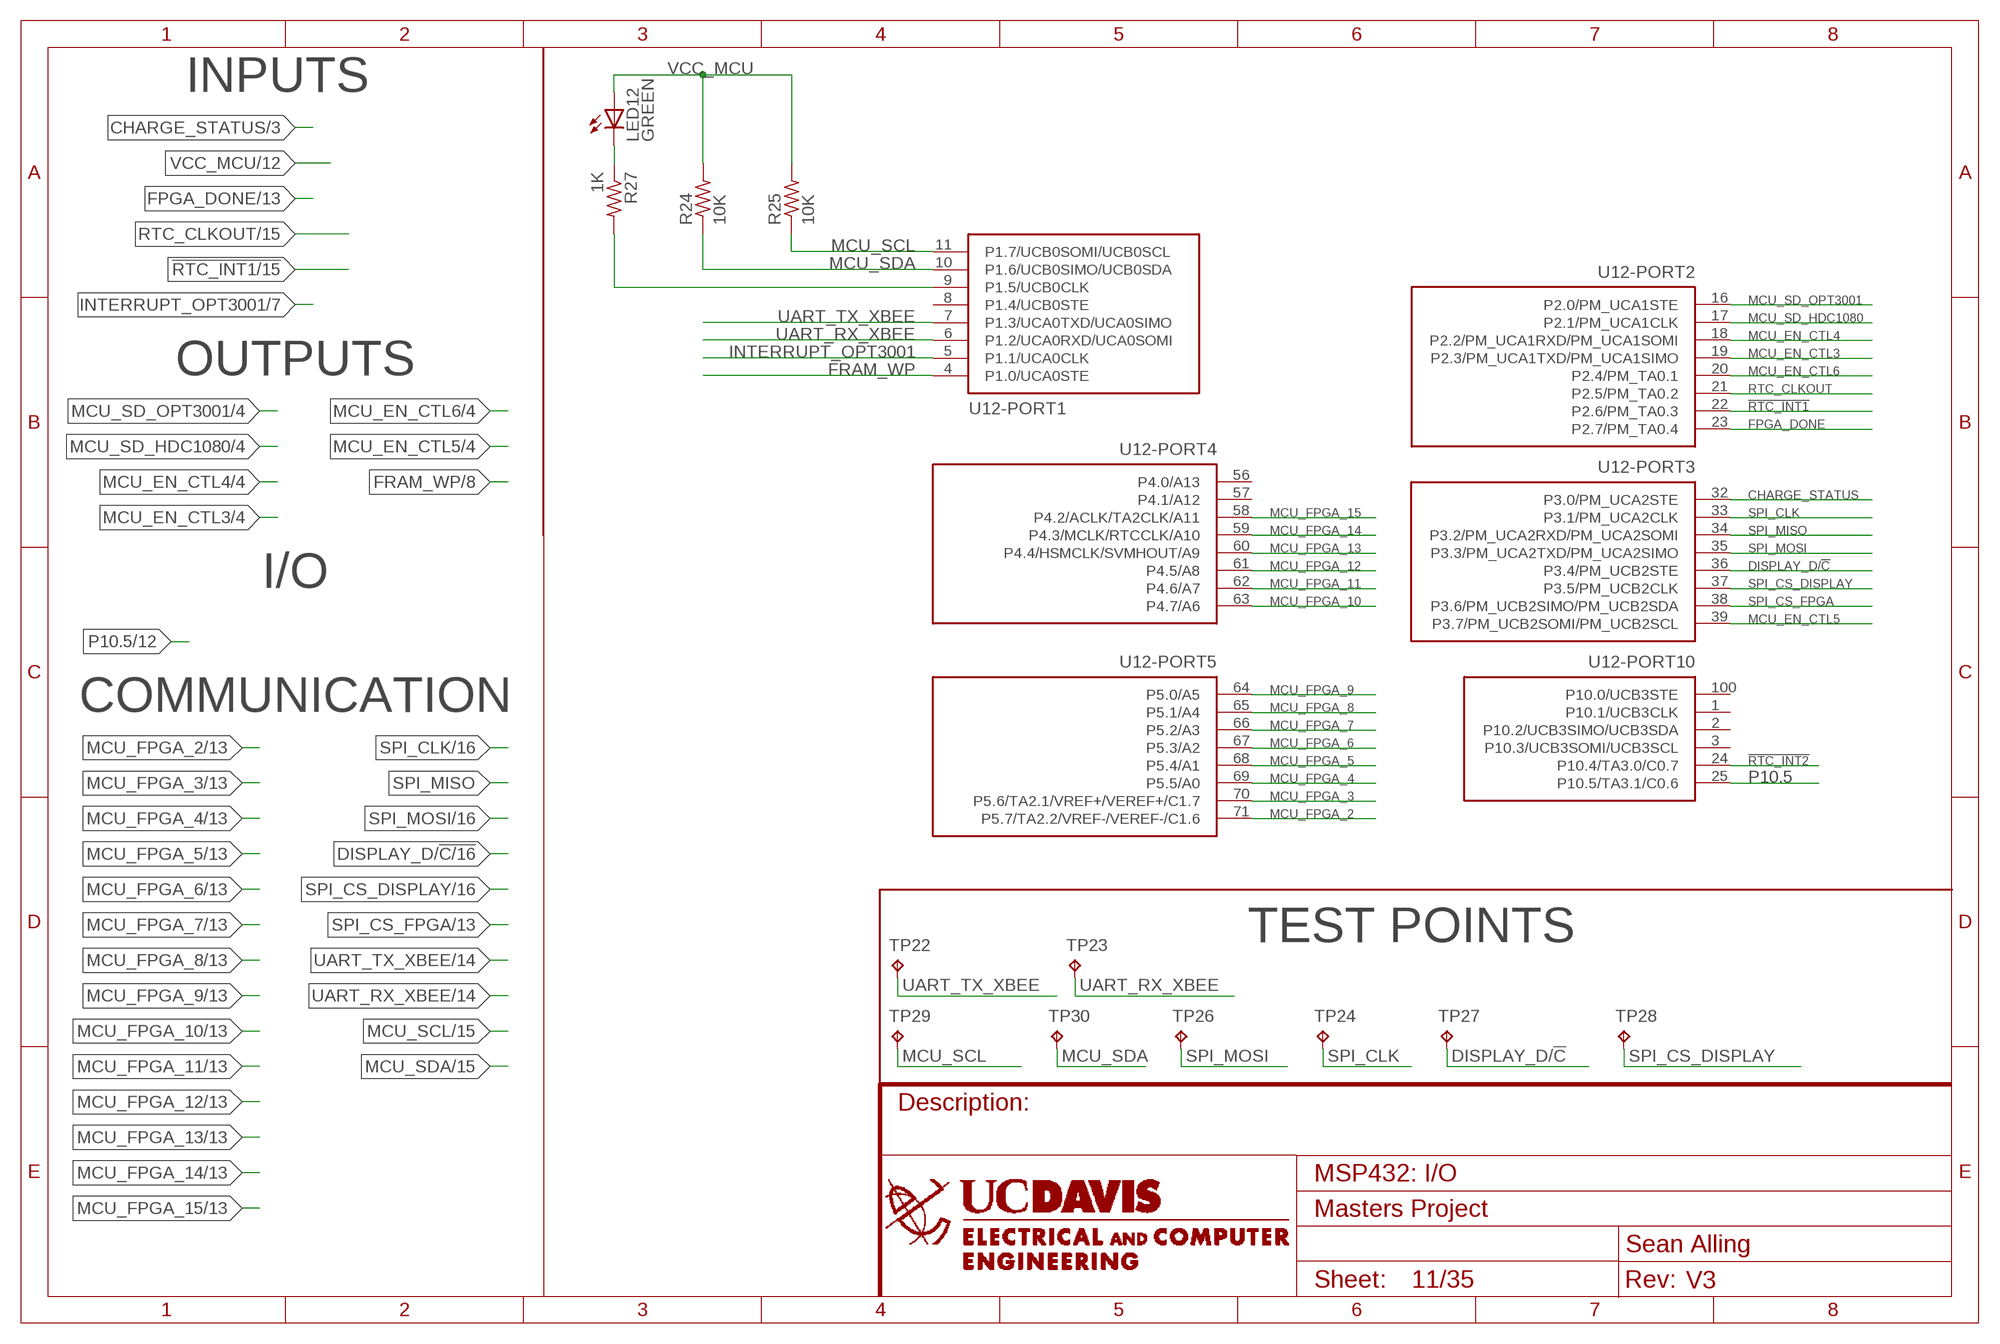
[diagram p10: schematic, sheet 11]
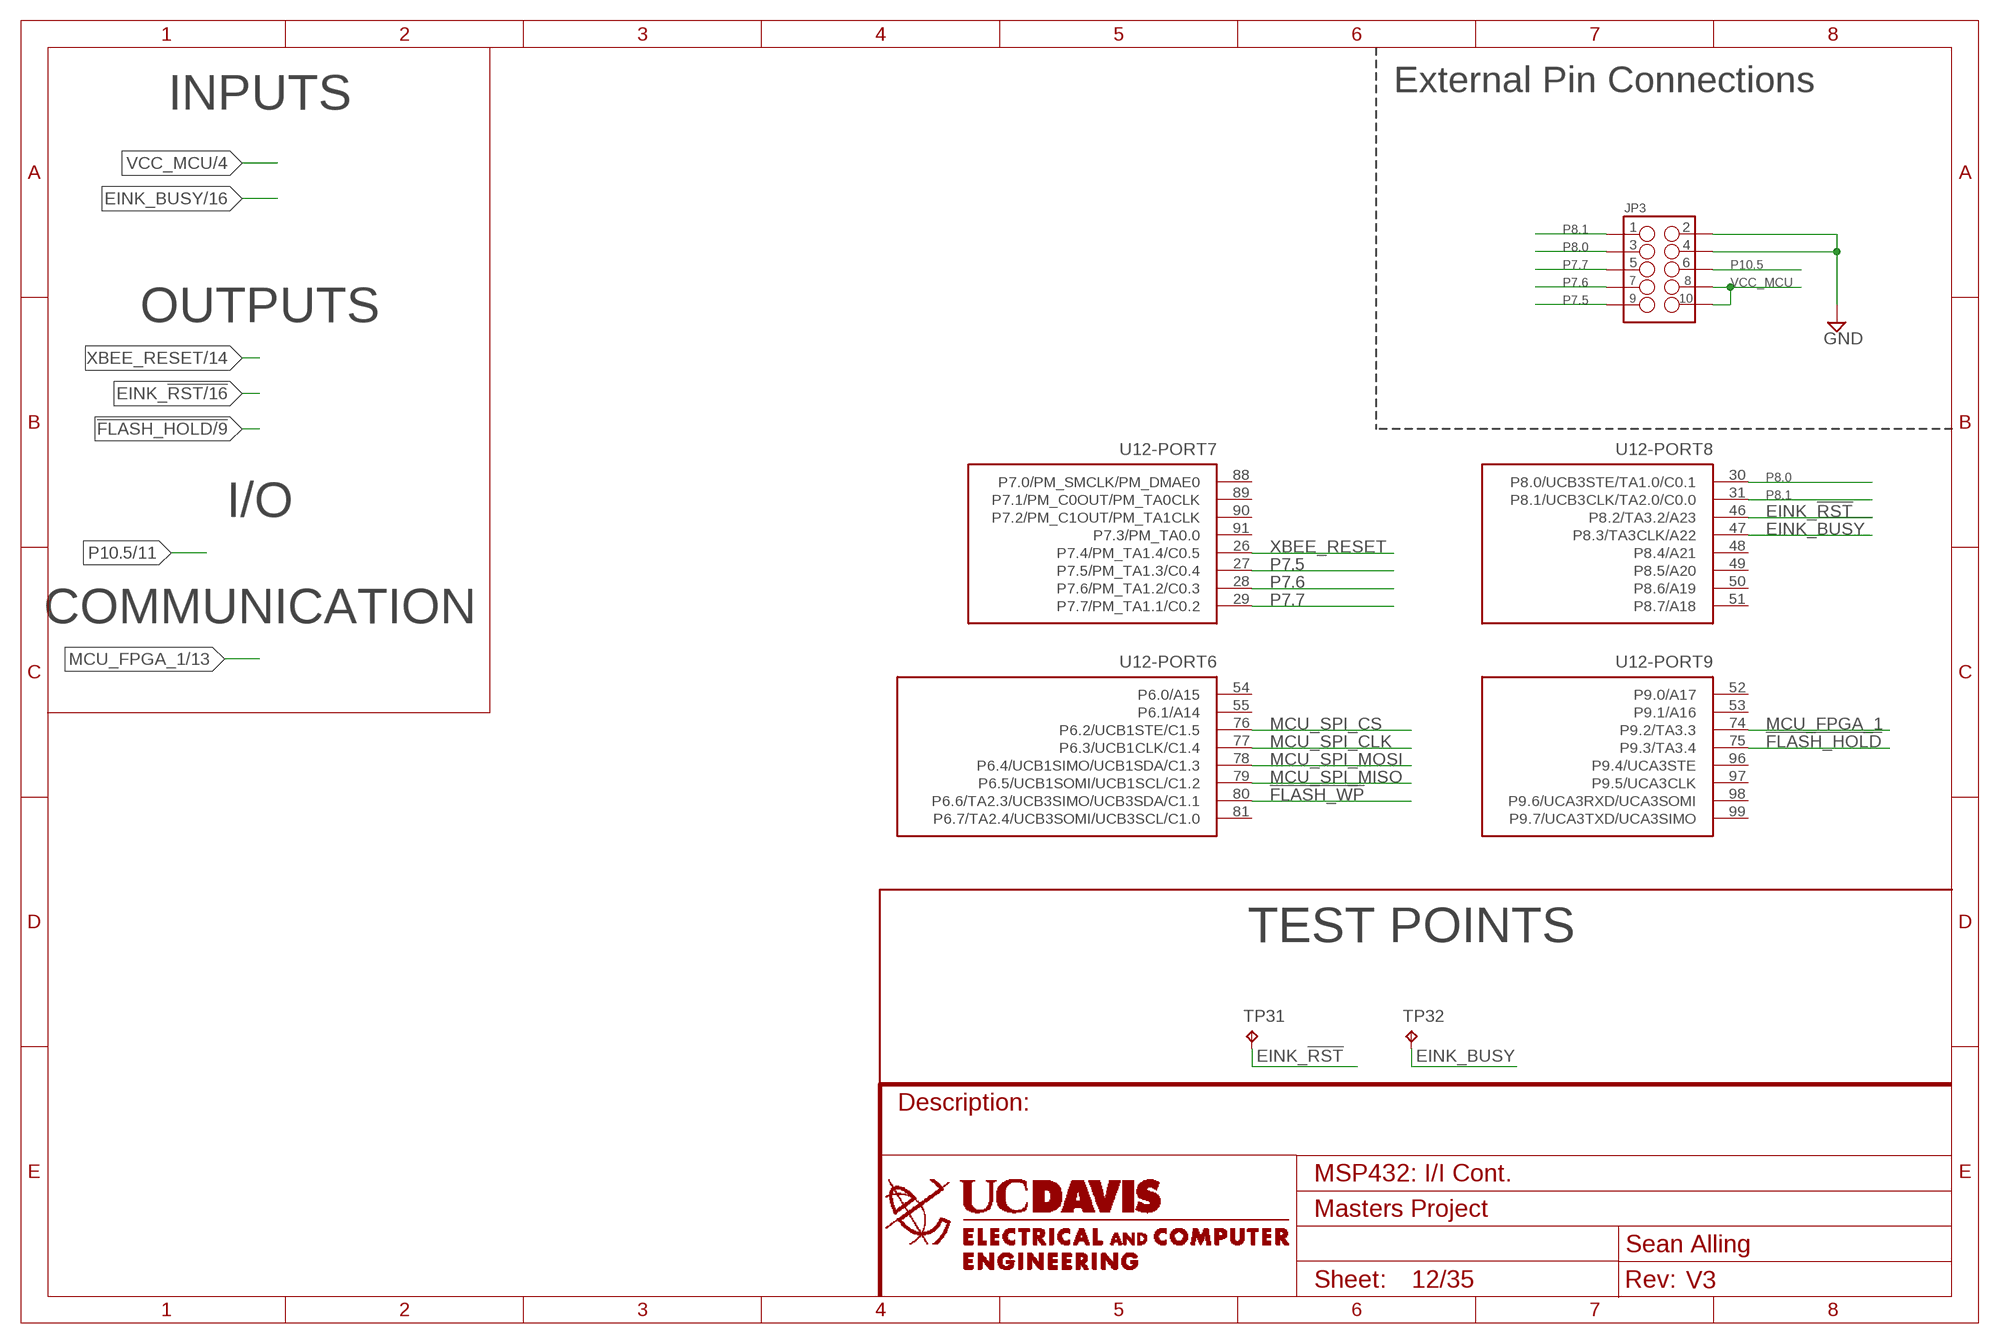
[diagram p11: schematic, sheet 12]
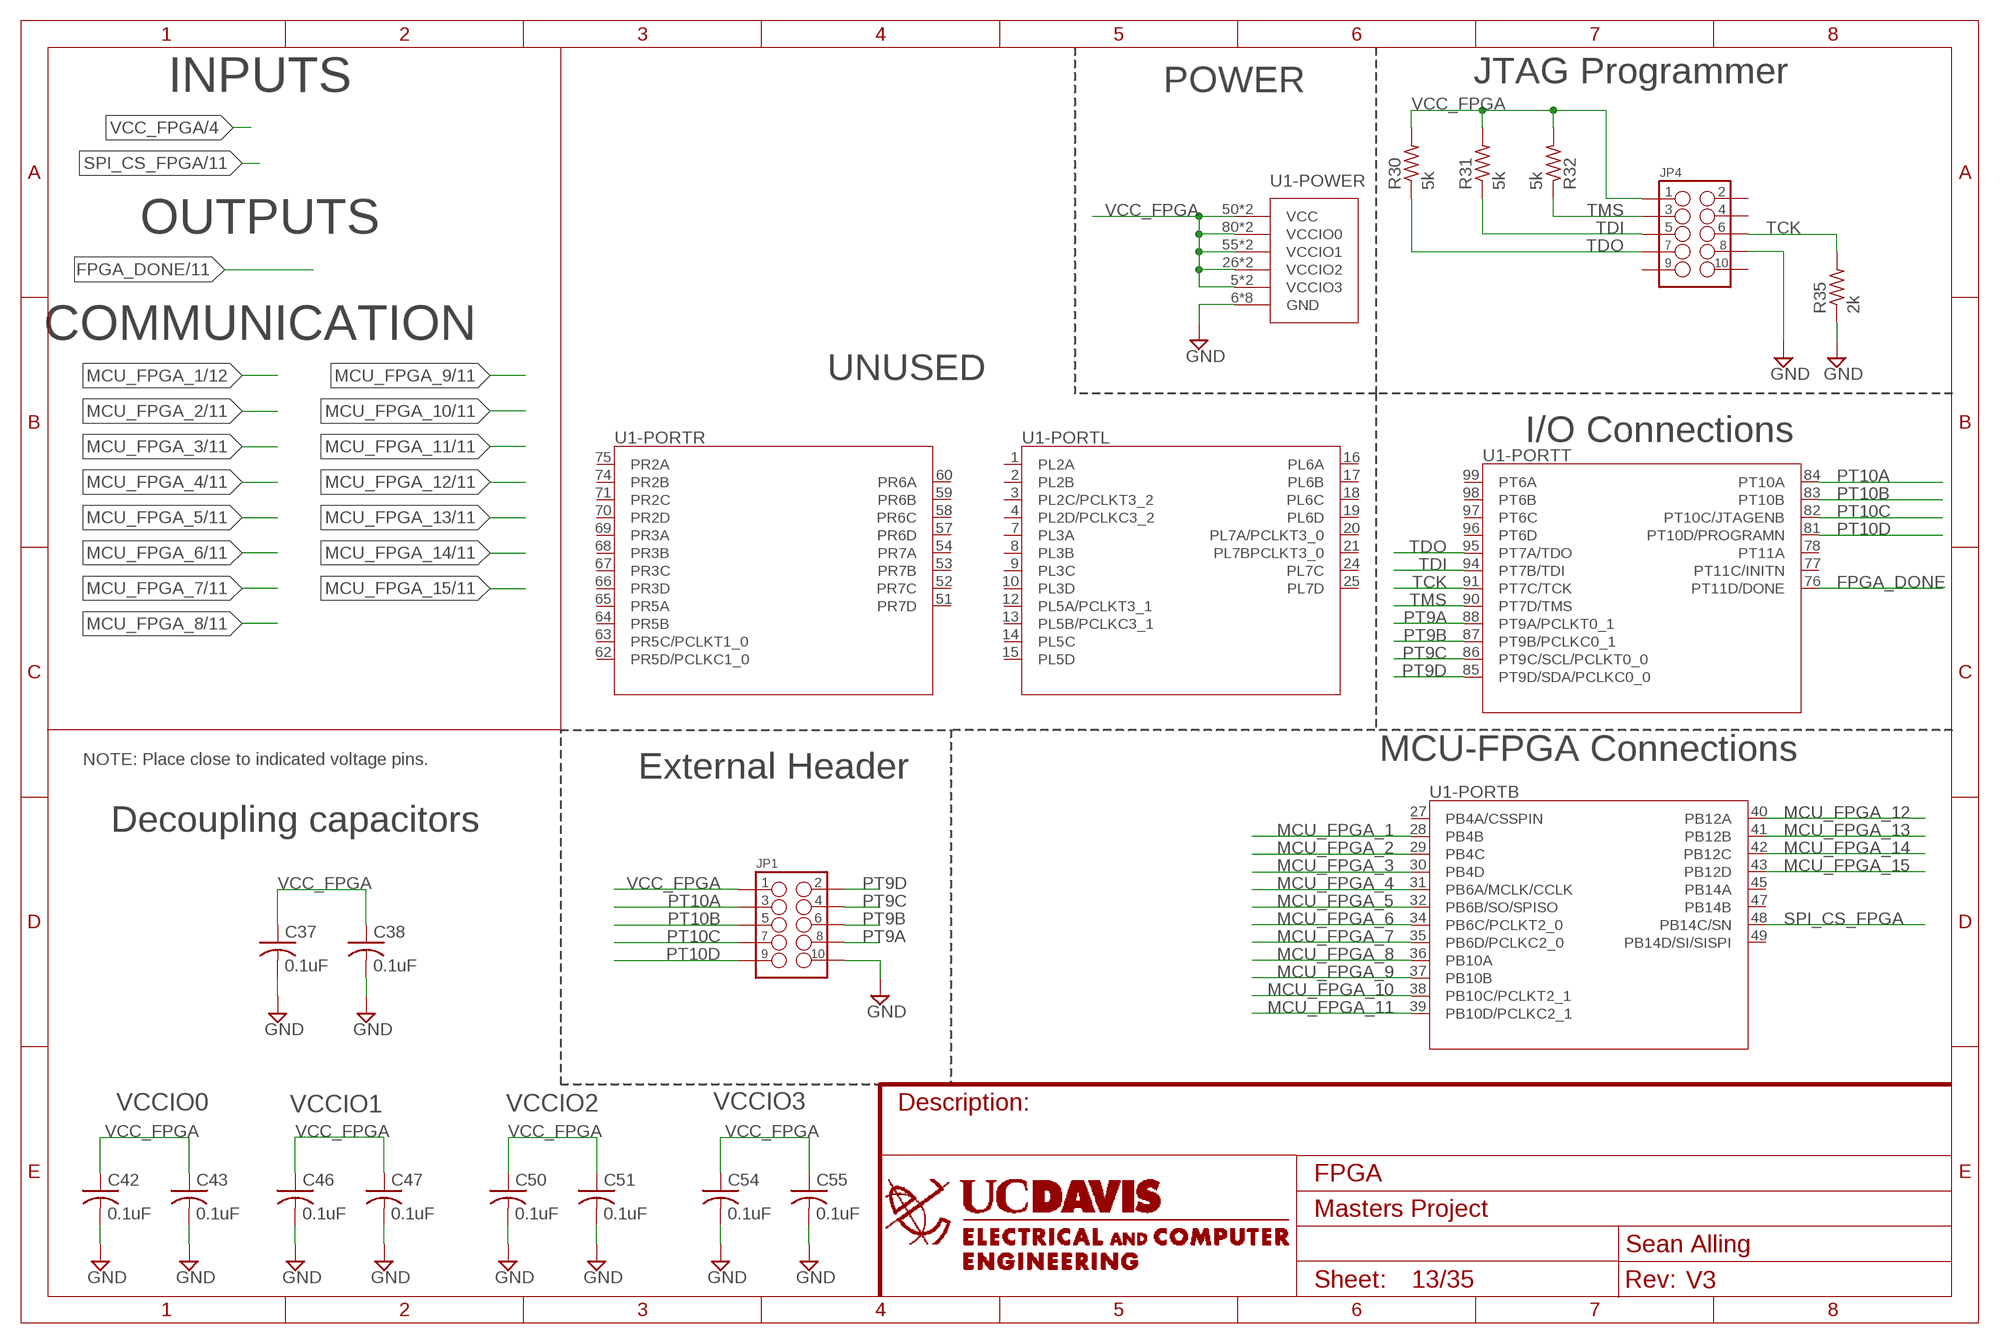
[diagram p12: schematic, sheet 13]
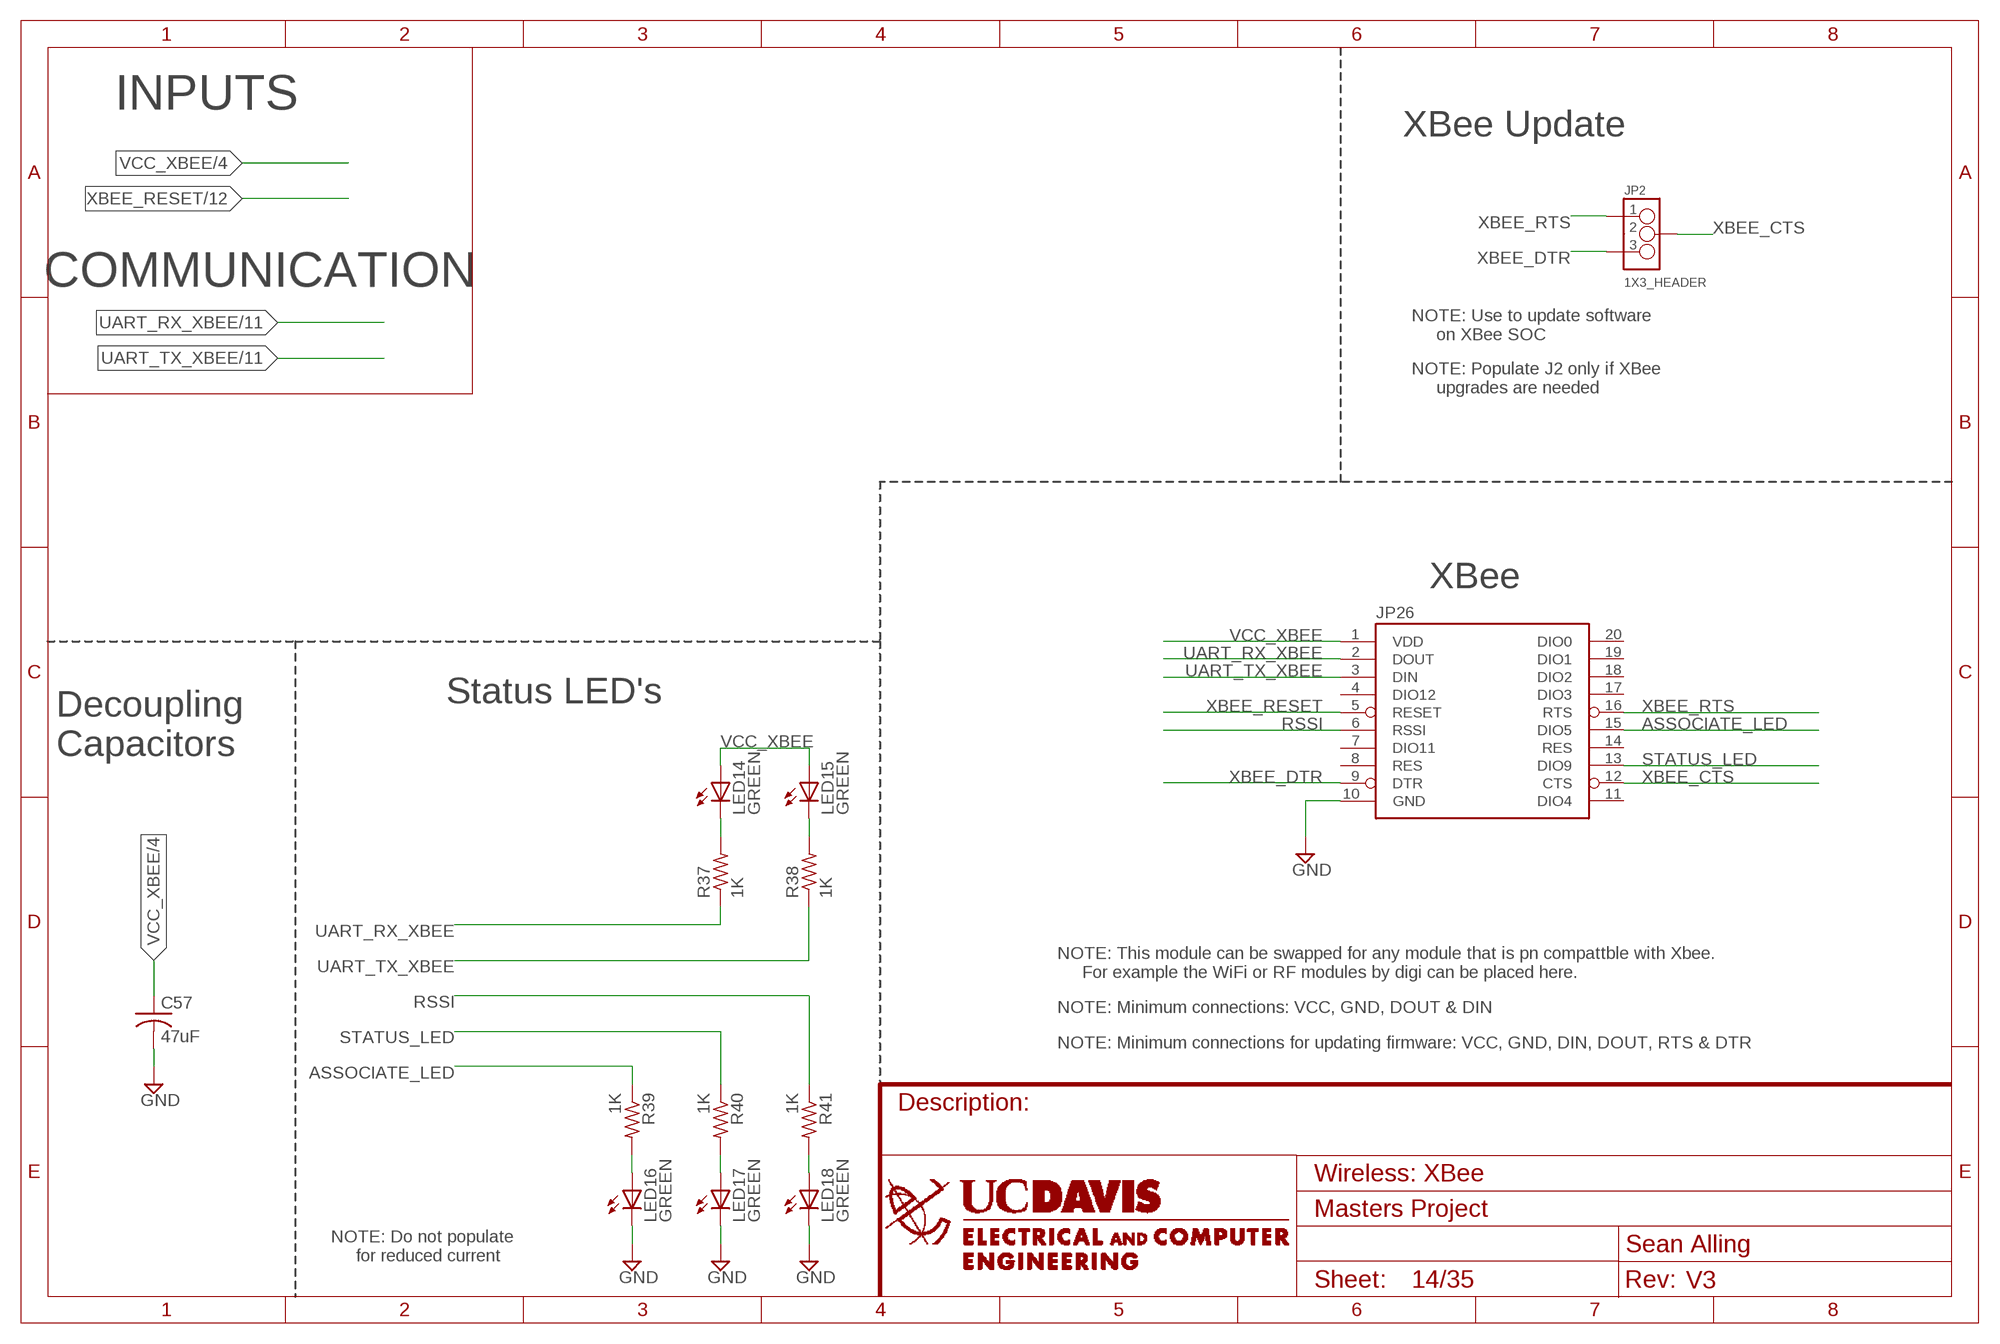
[diagram p13: schematic, sheet 14]
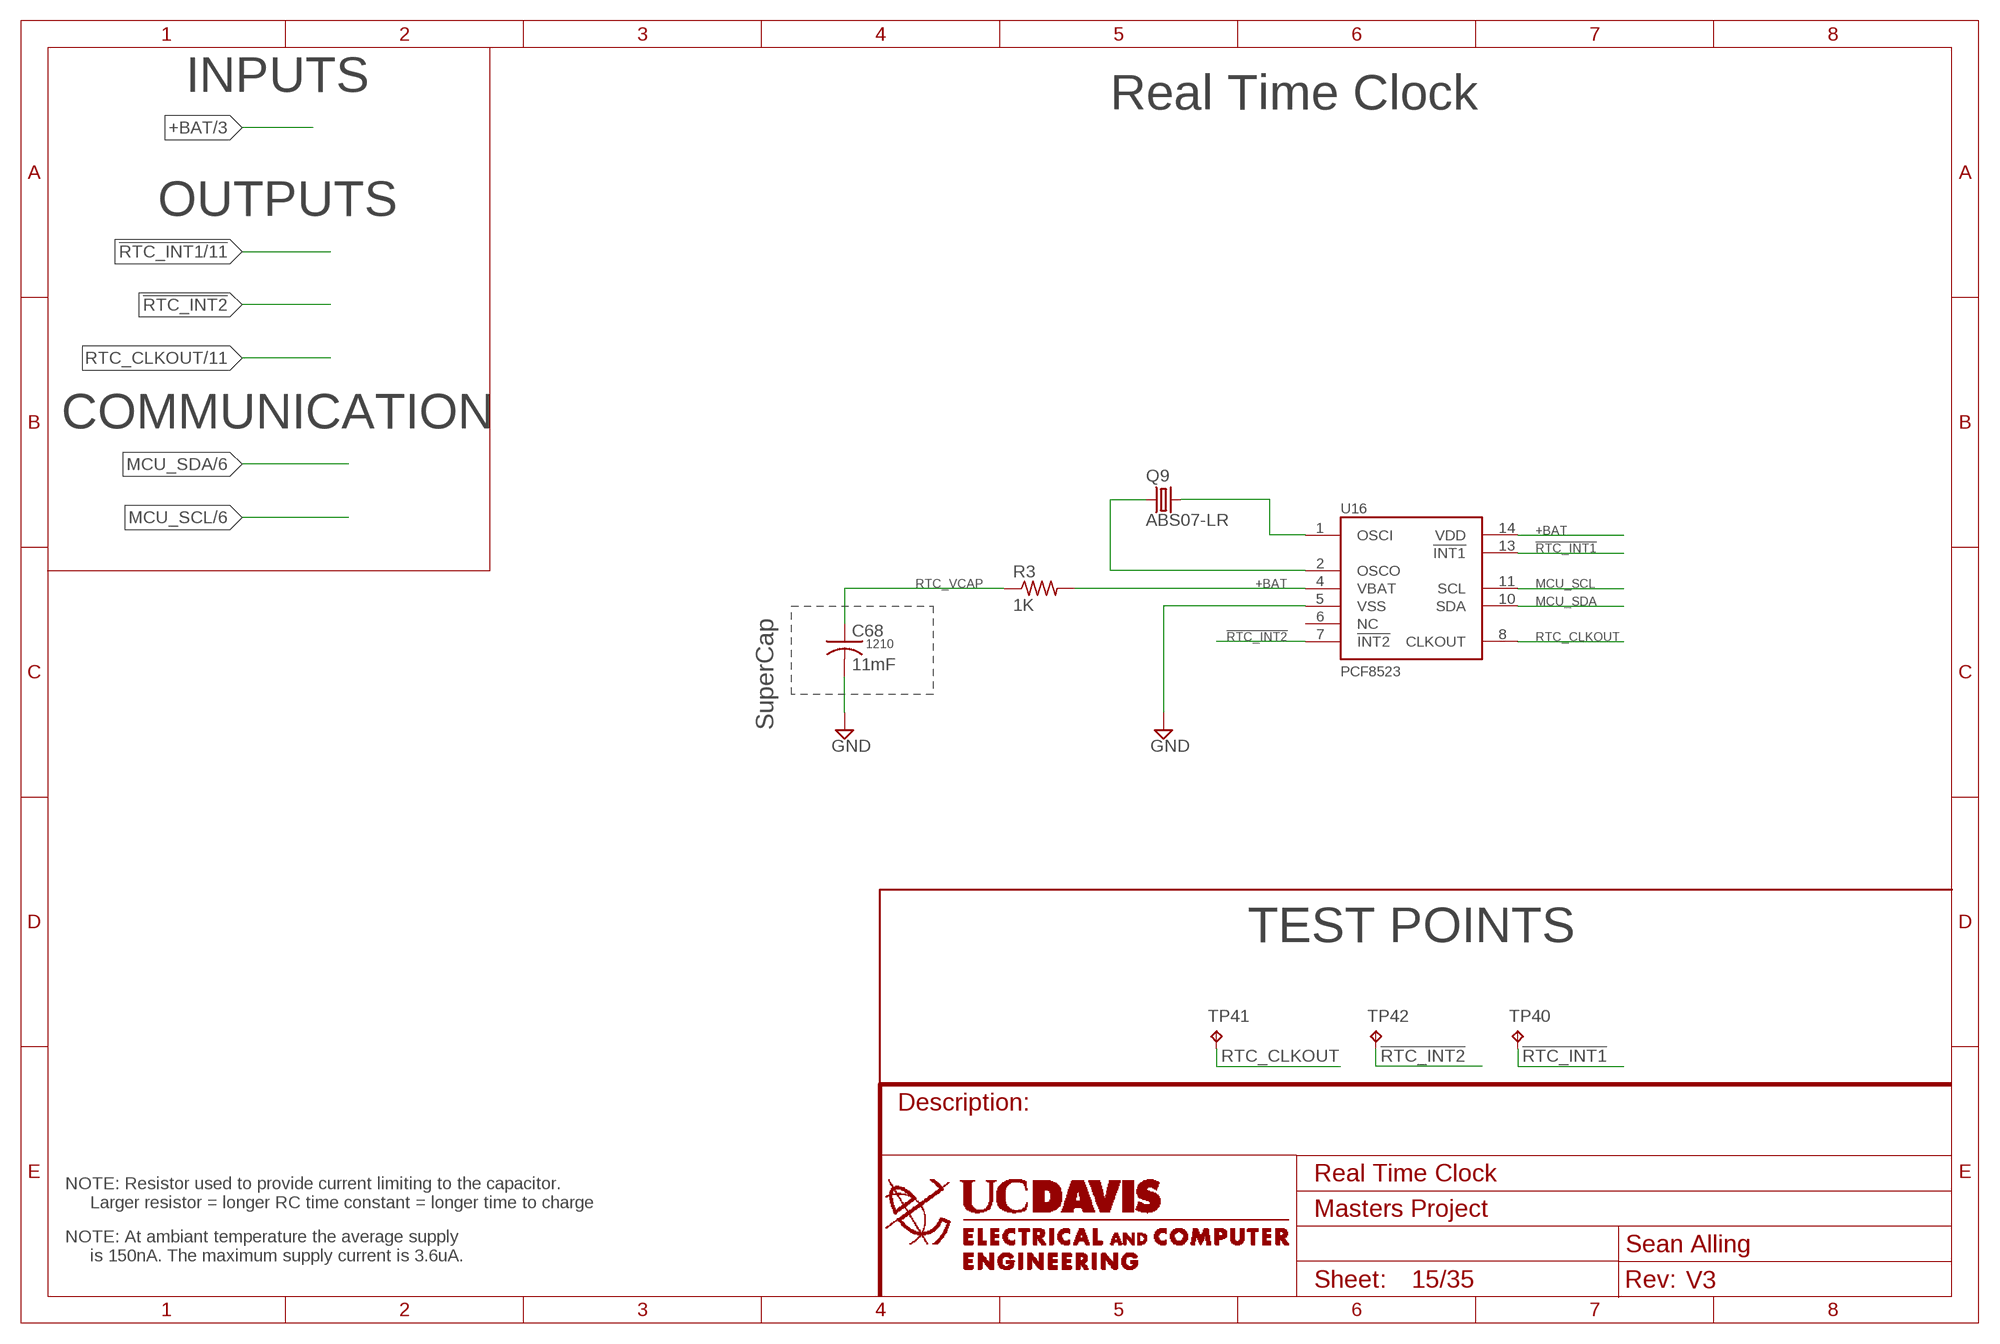
[diagram p14: schematic, sheet 15]
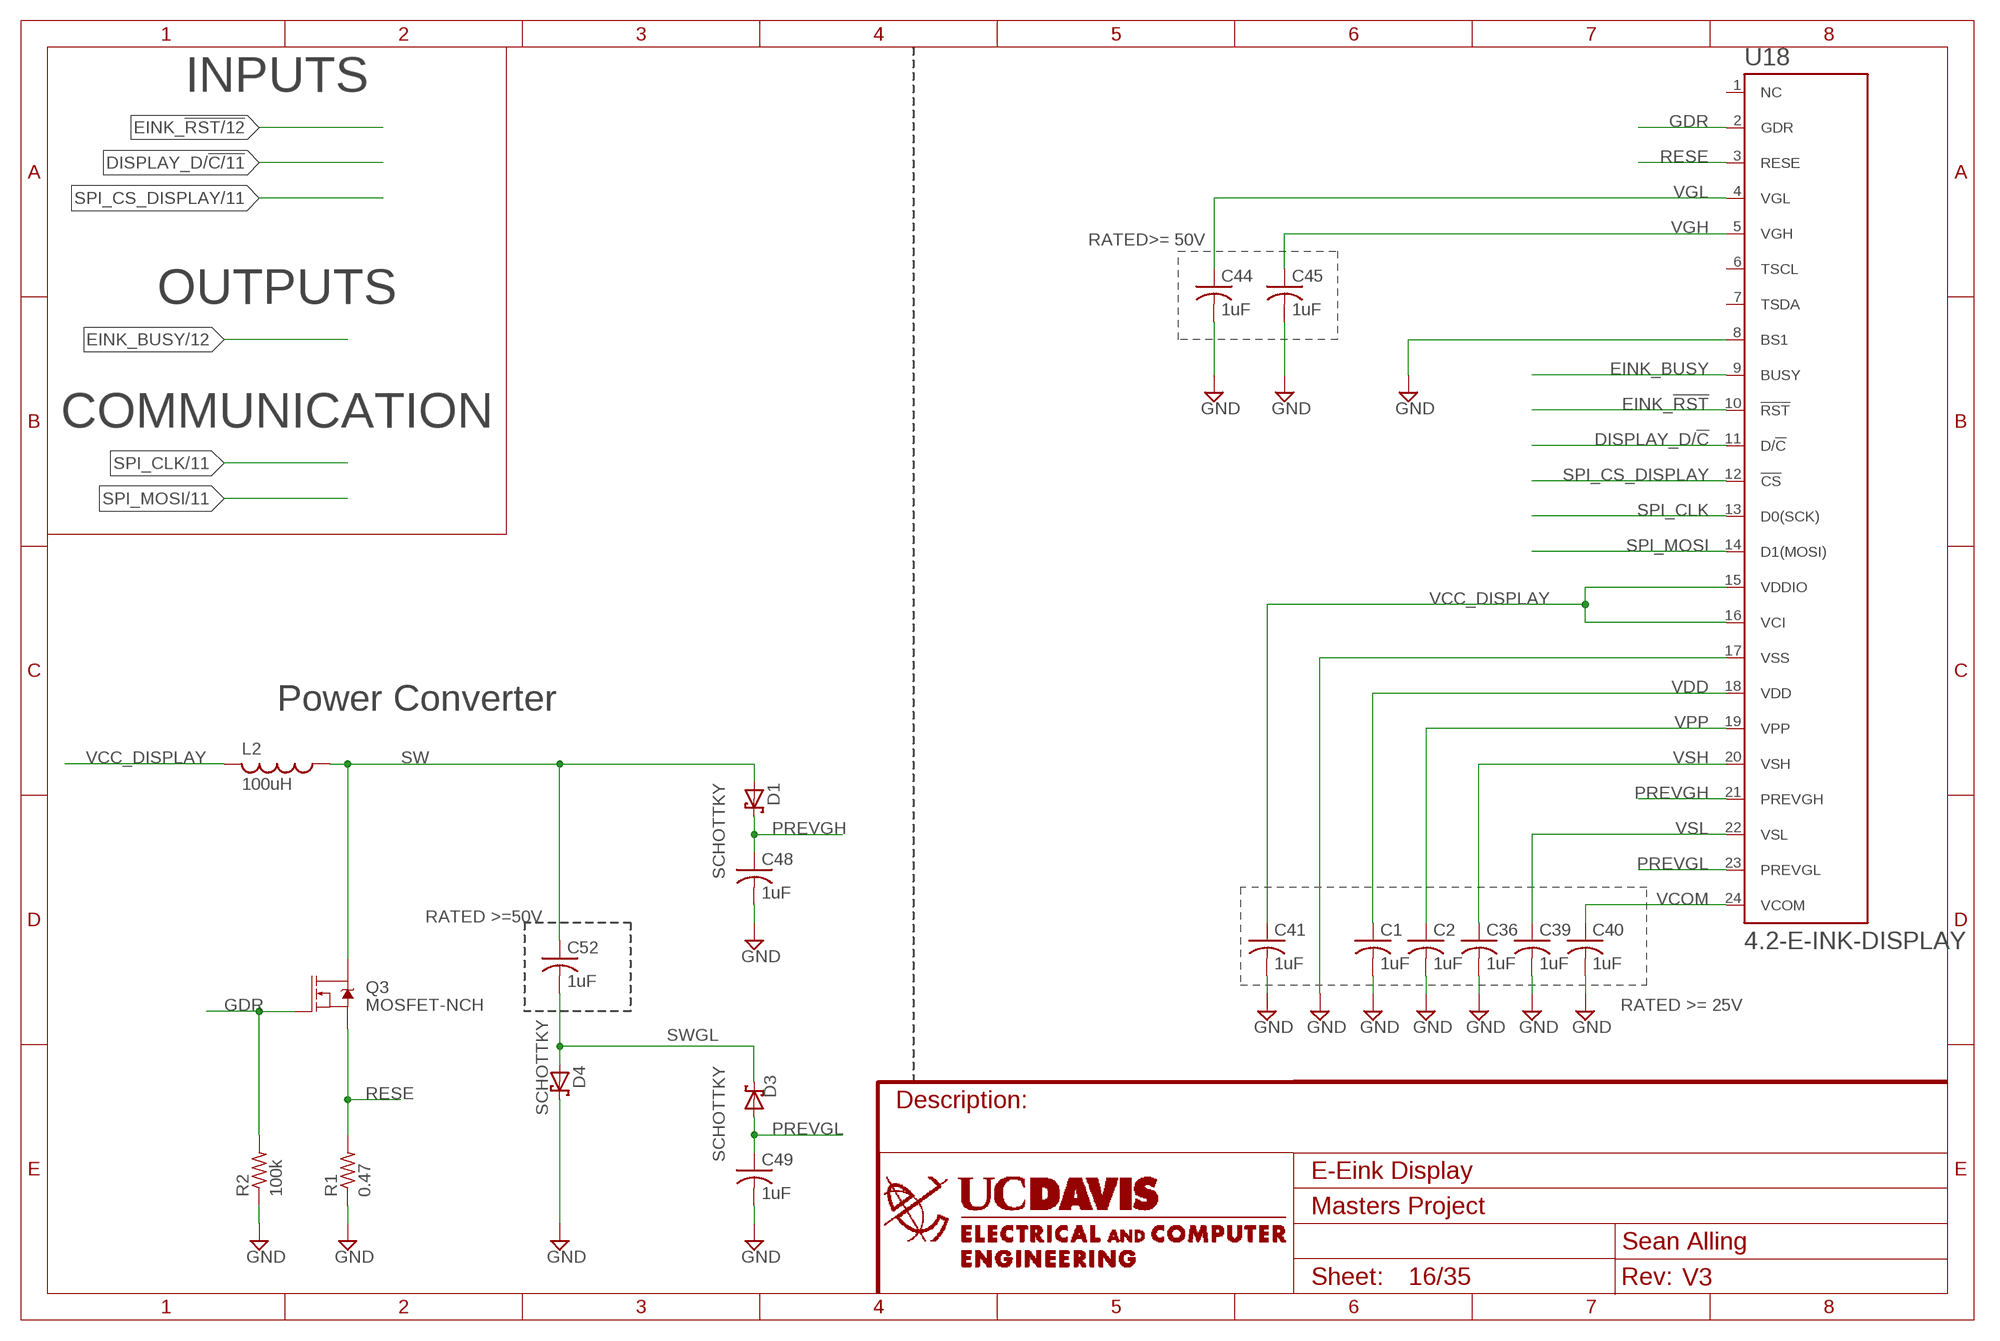
[diagram p15: schematic, sheet 16]
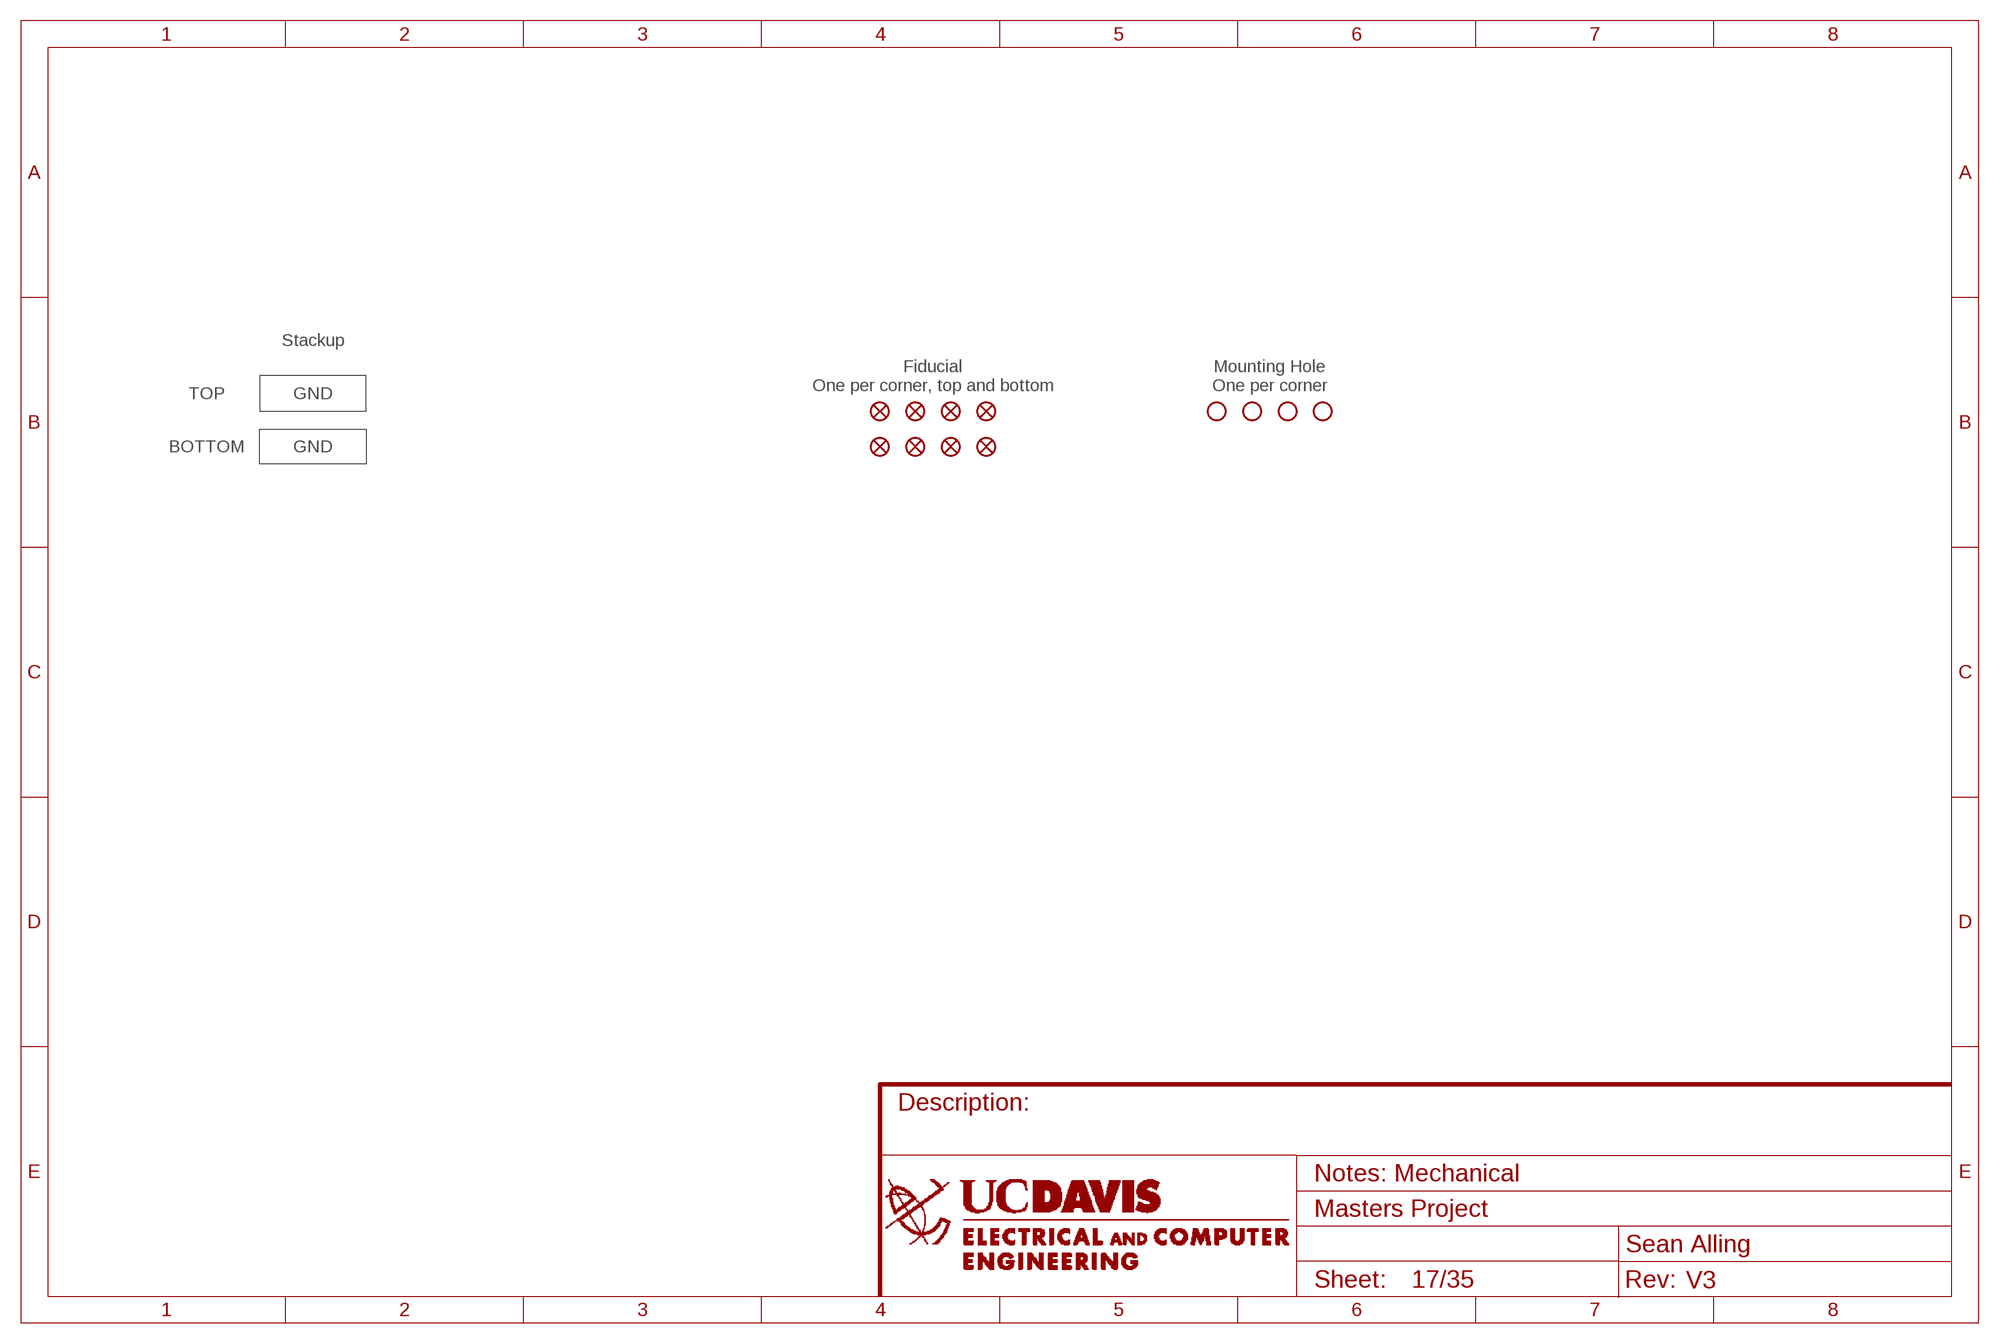
[diagram p16: schematic, sheet 17]
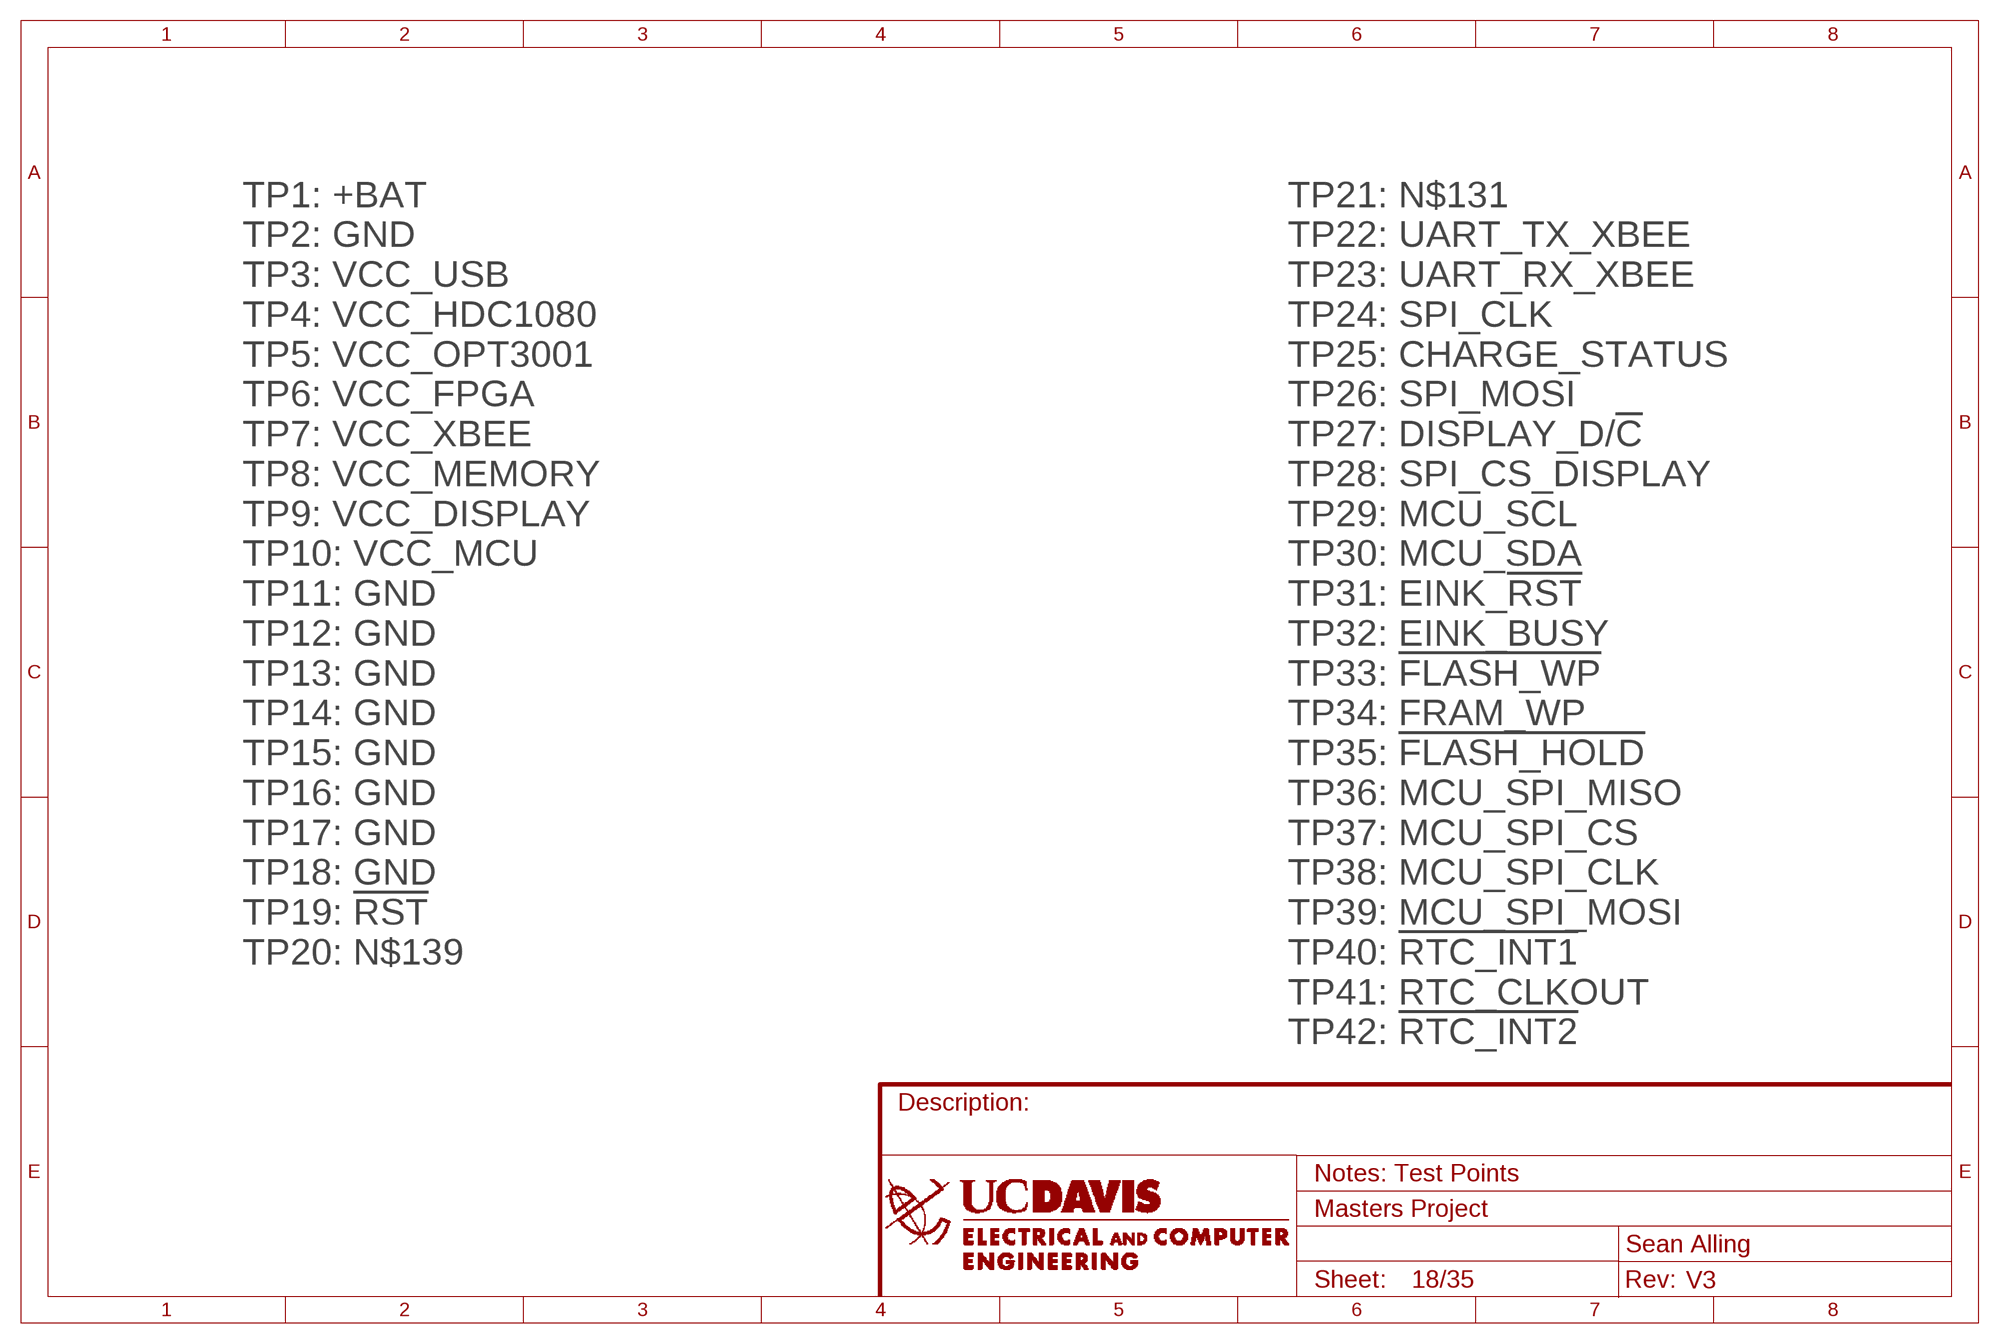
[diagram p17: schematic, sheet 18]
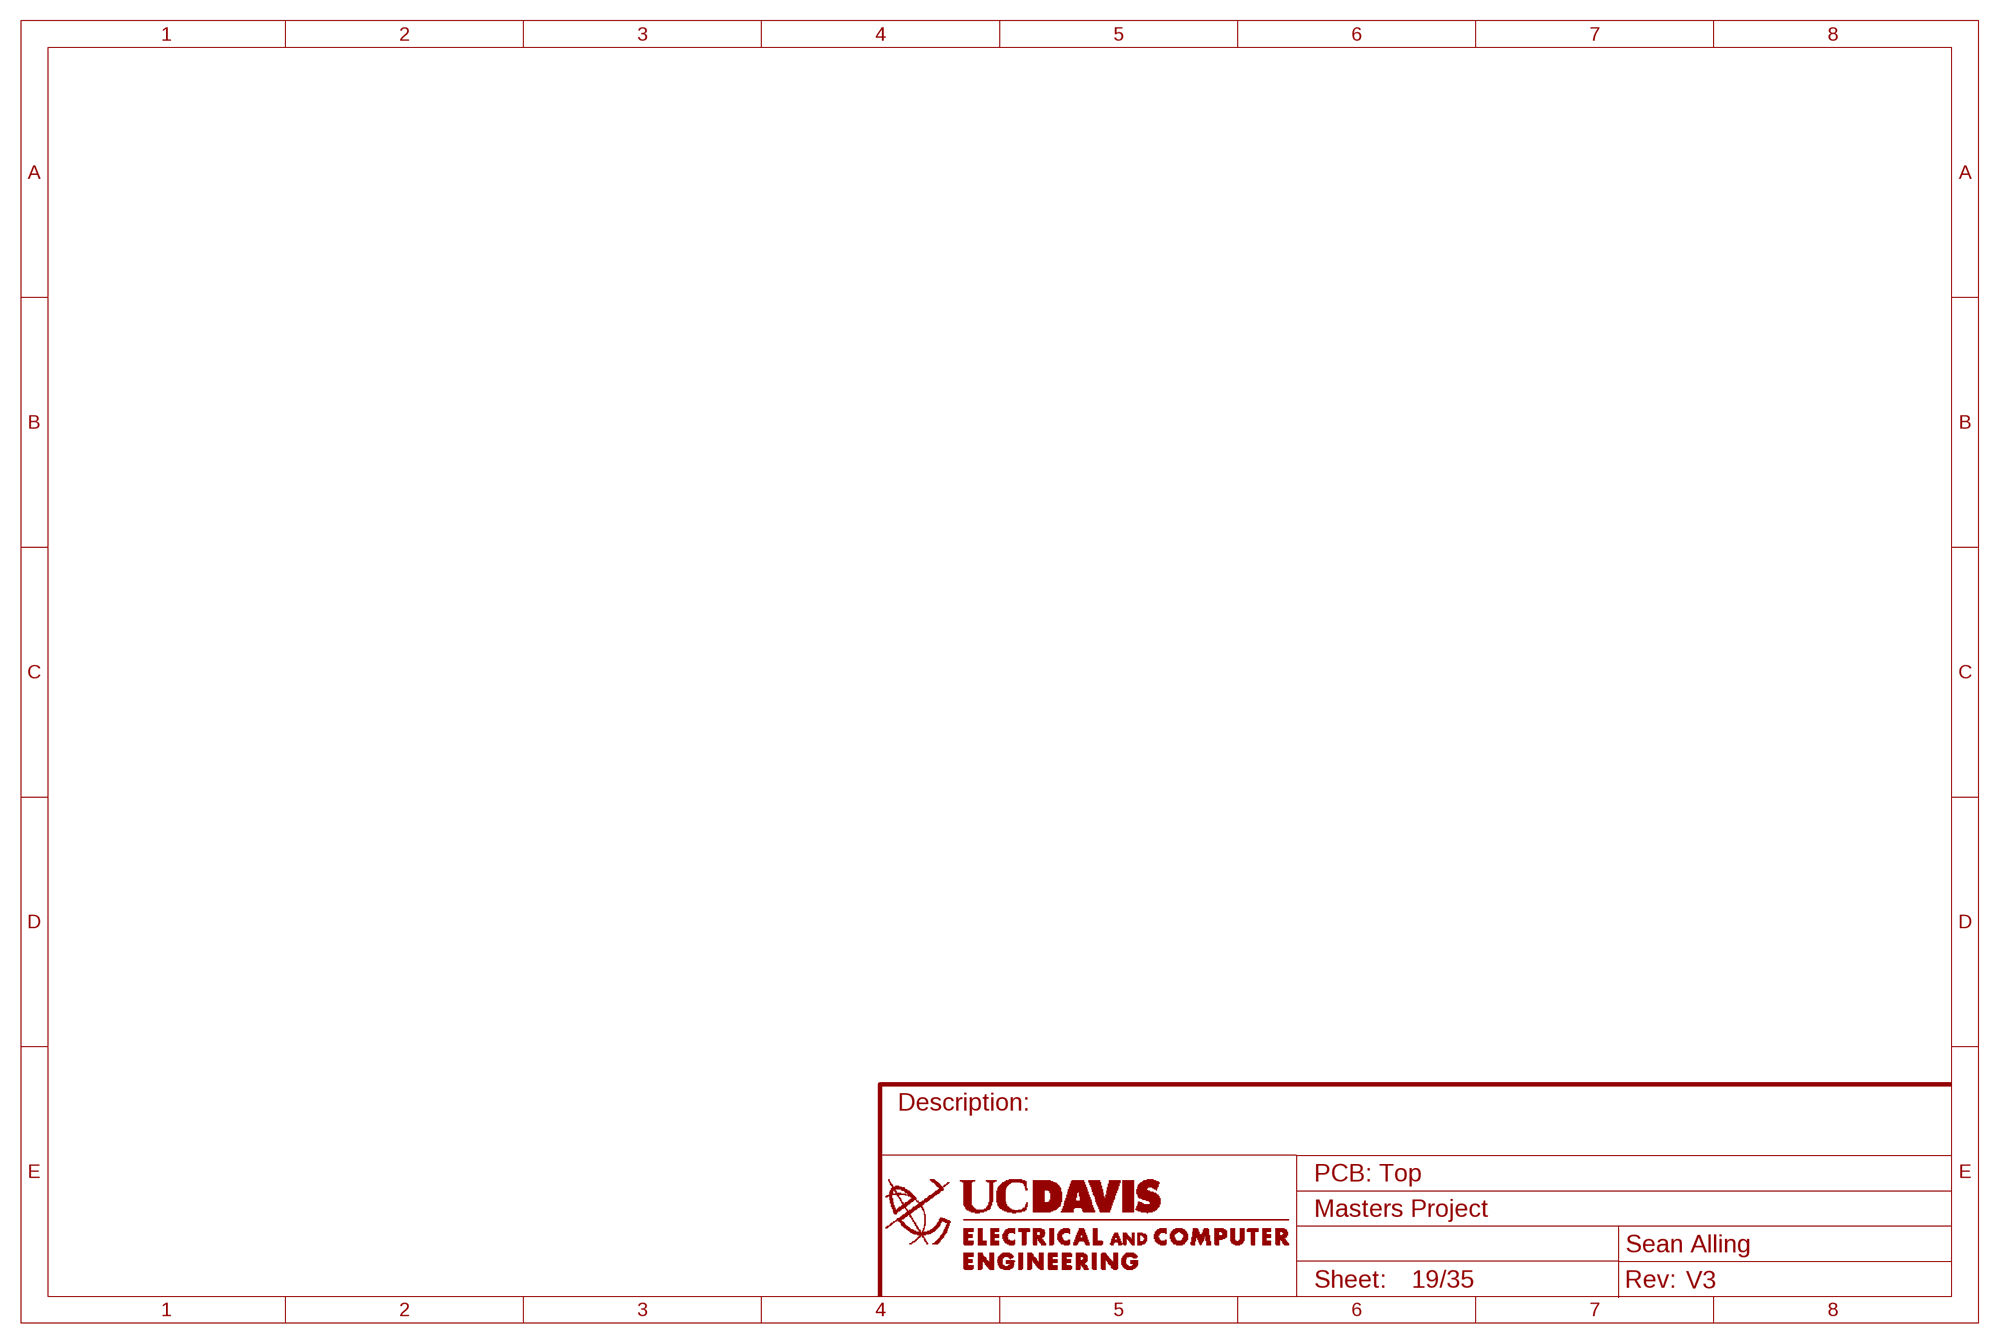
[diagram p18: schematic, sheet 19]
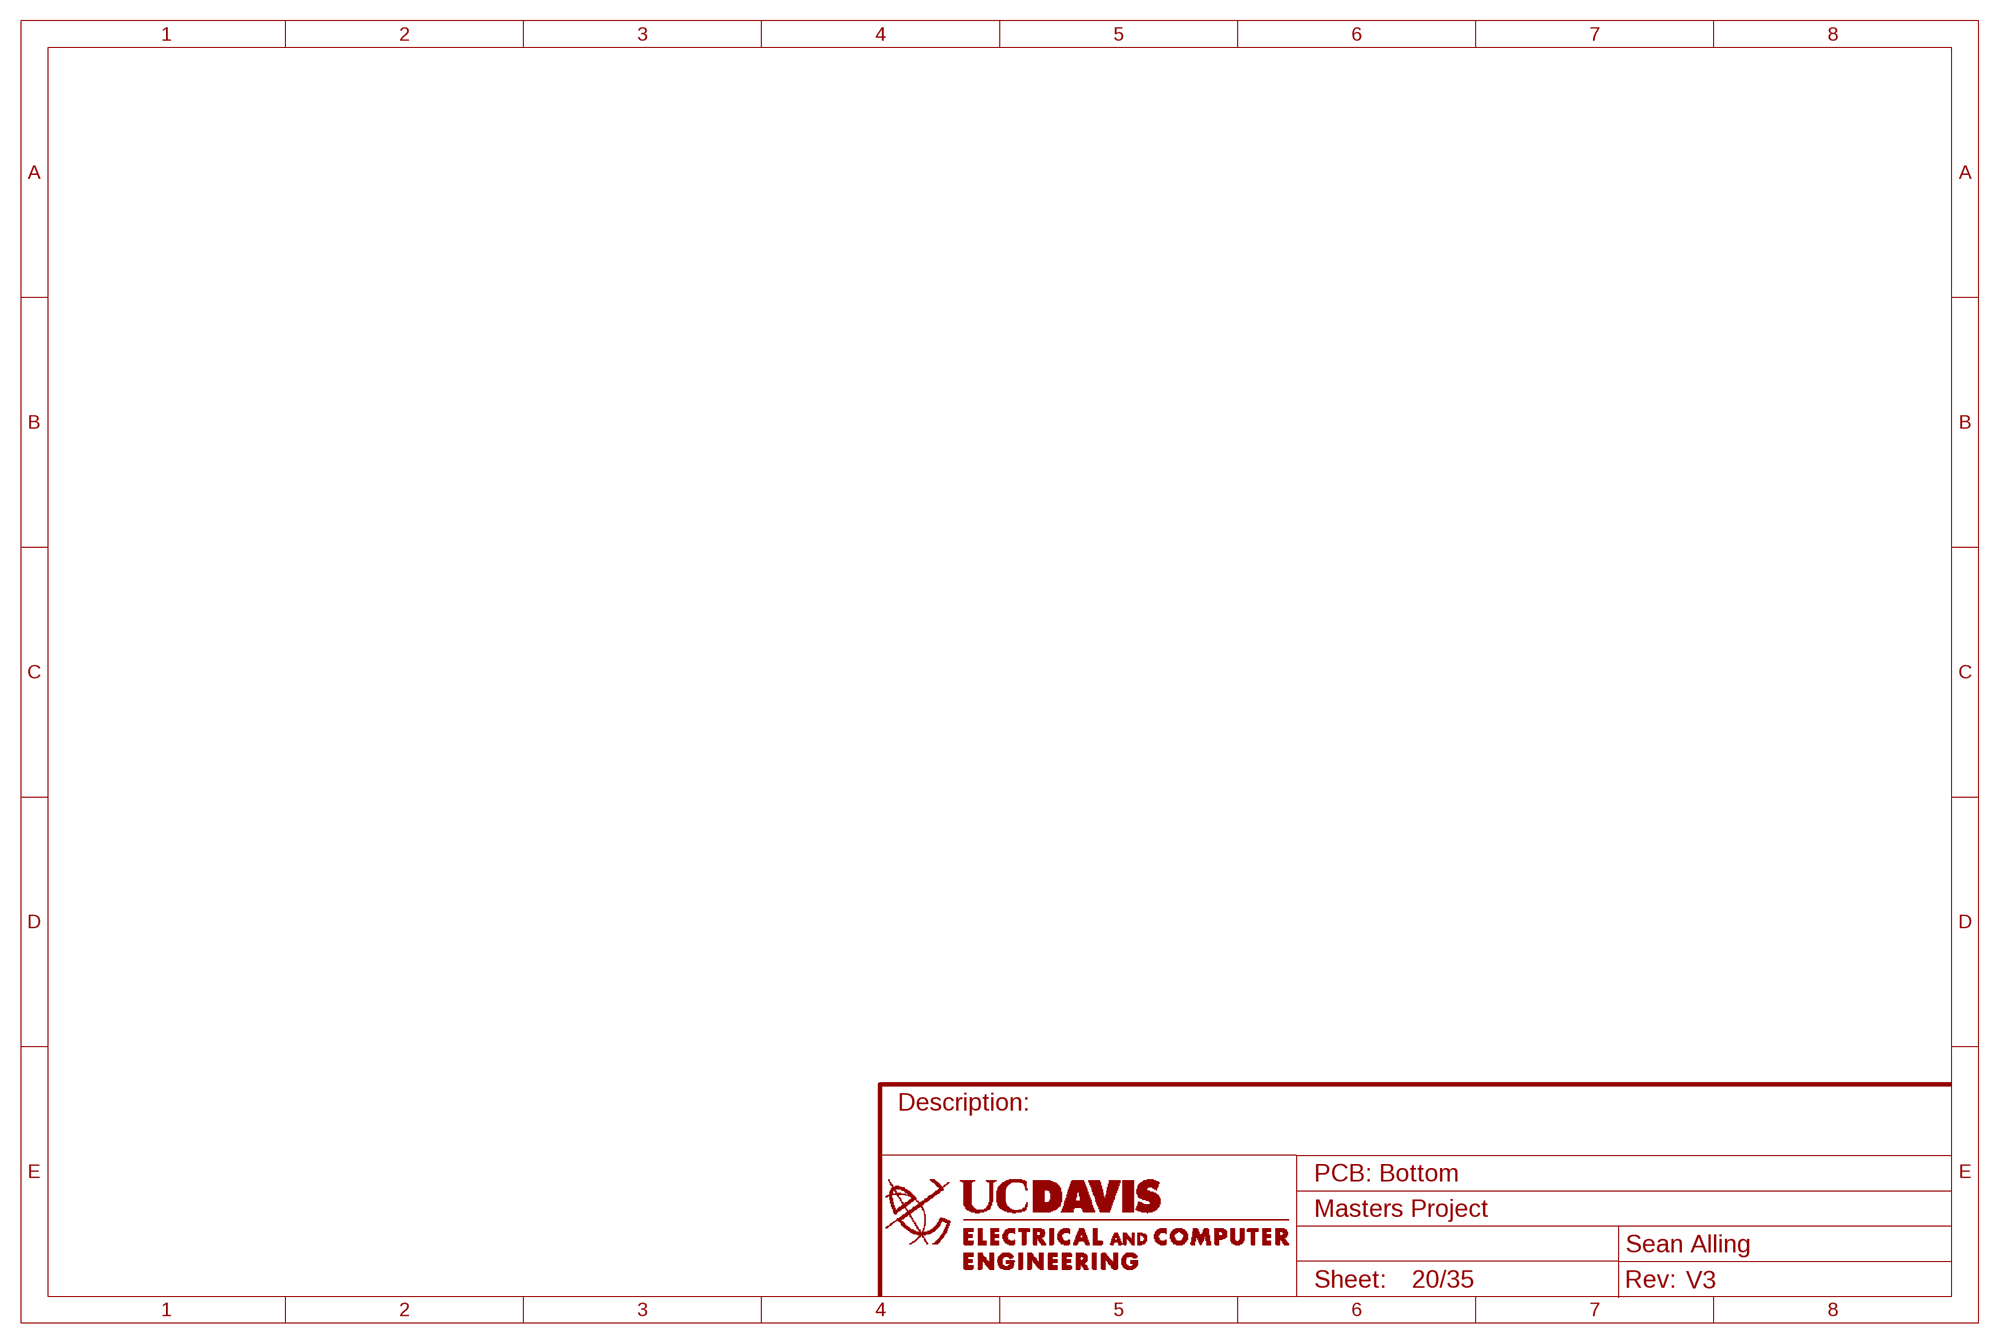
[diagram p19: schematic, sheet 20]
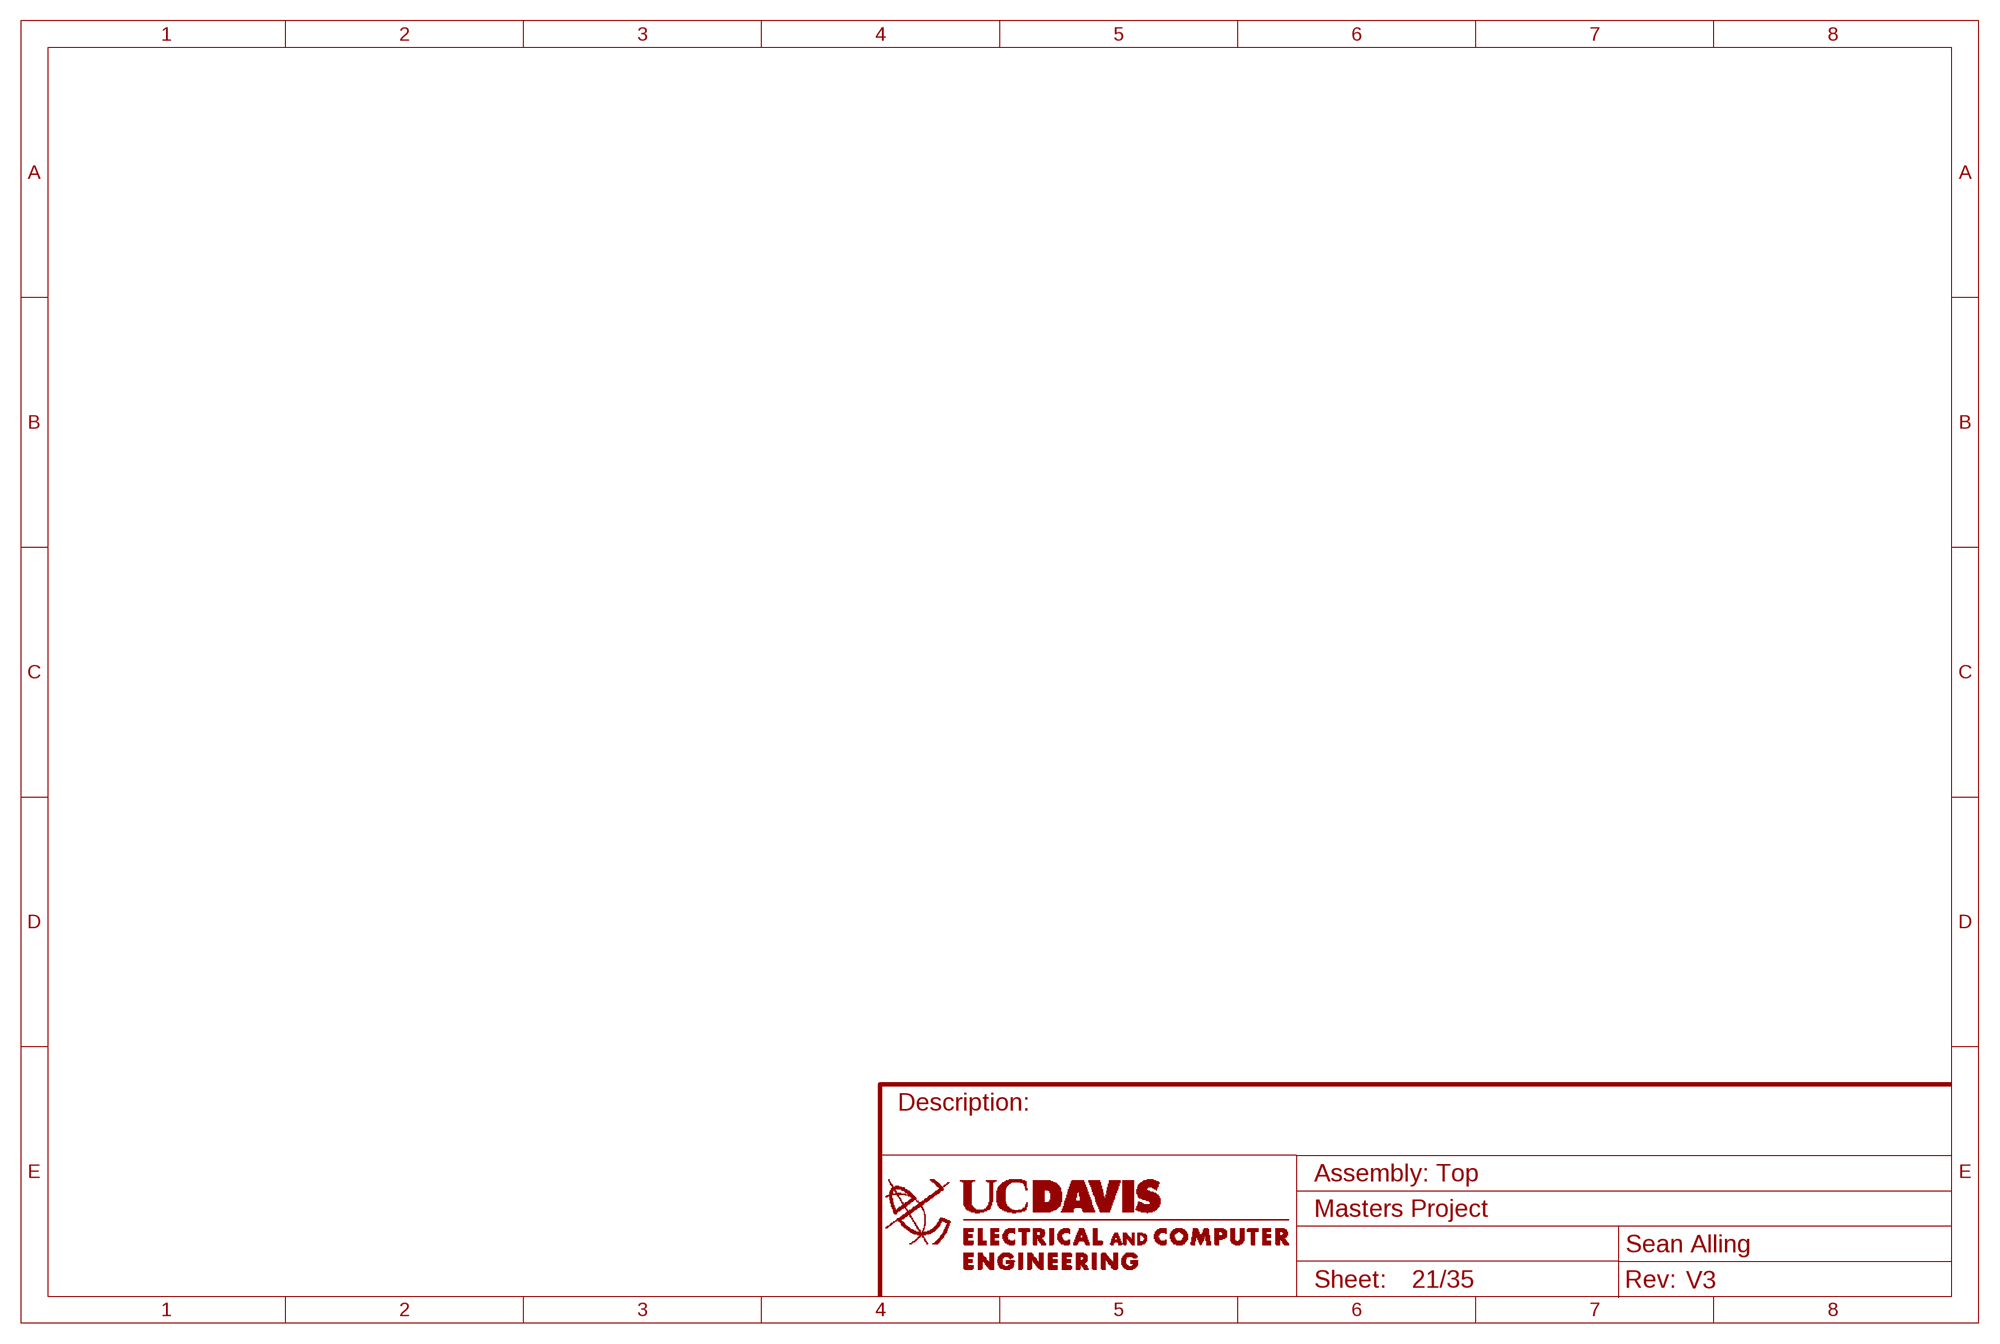
[diagram p20: schematic, sheet 21]
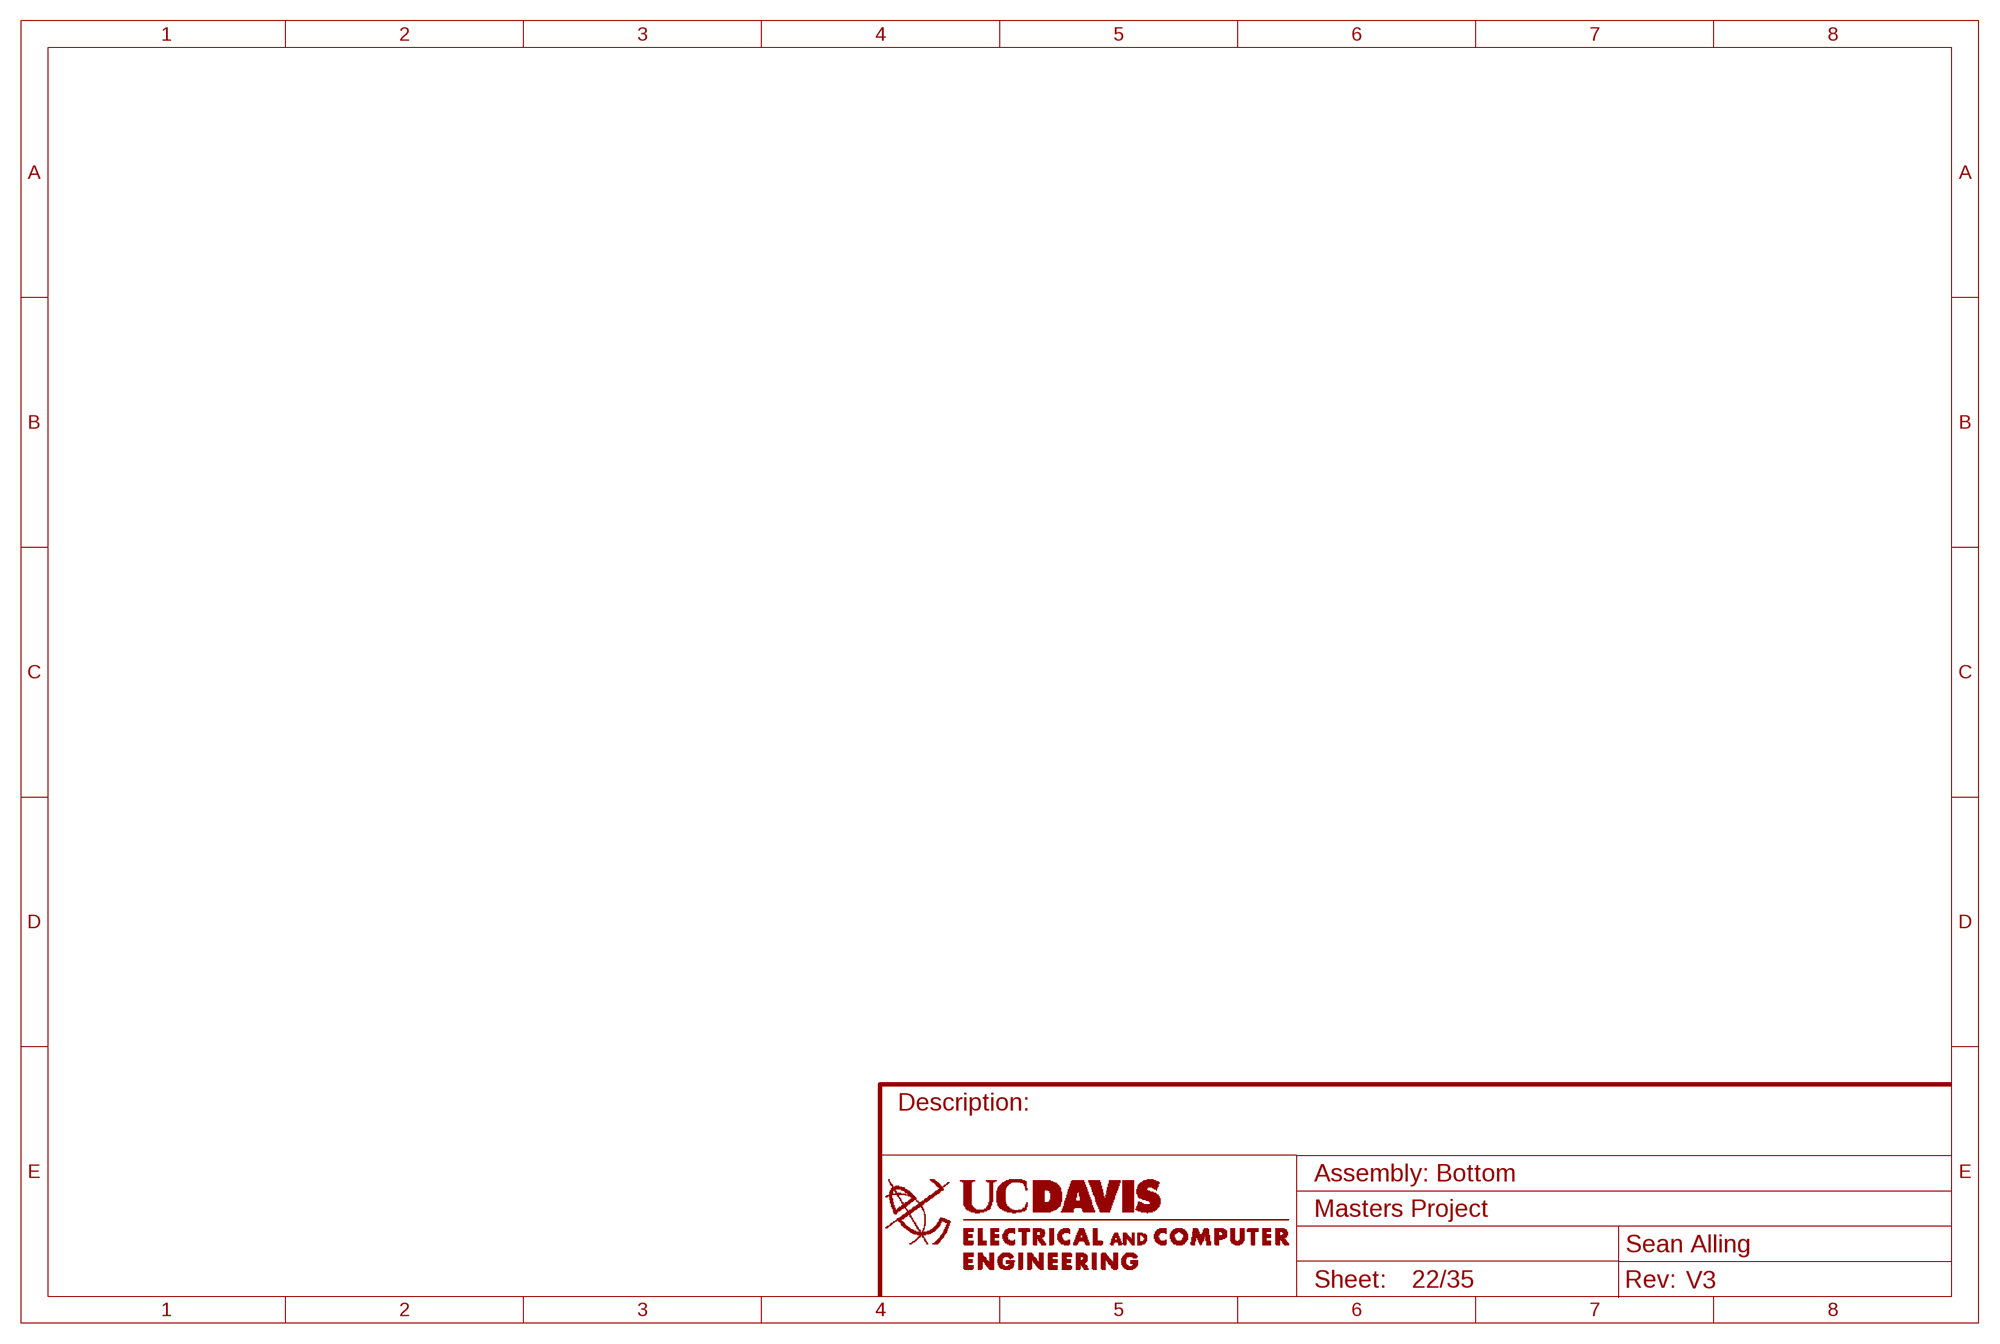
[diagram p21: schematic, sheet 22]
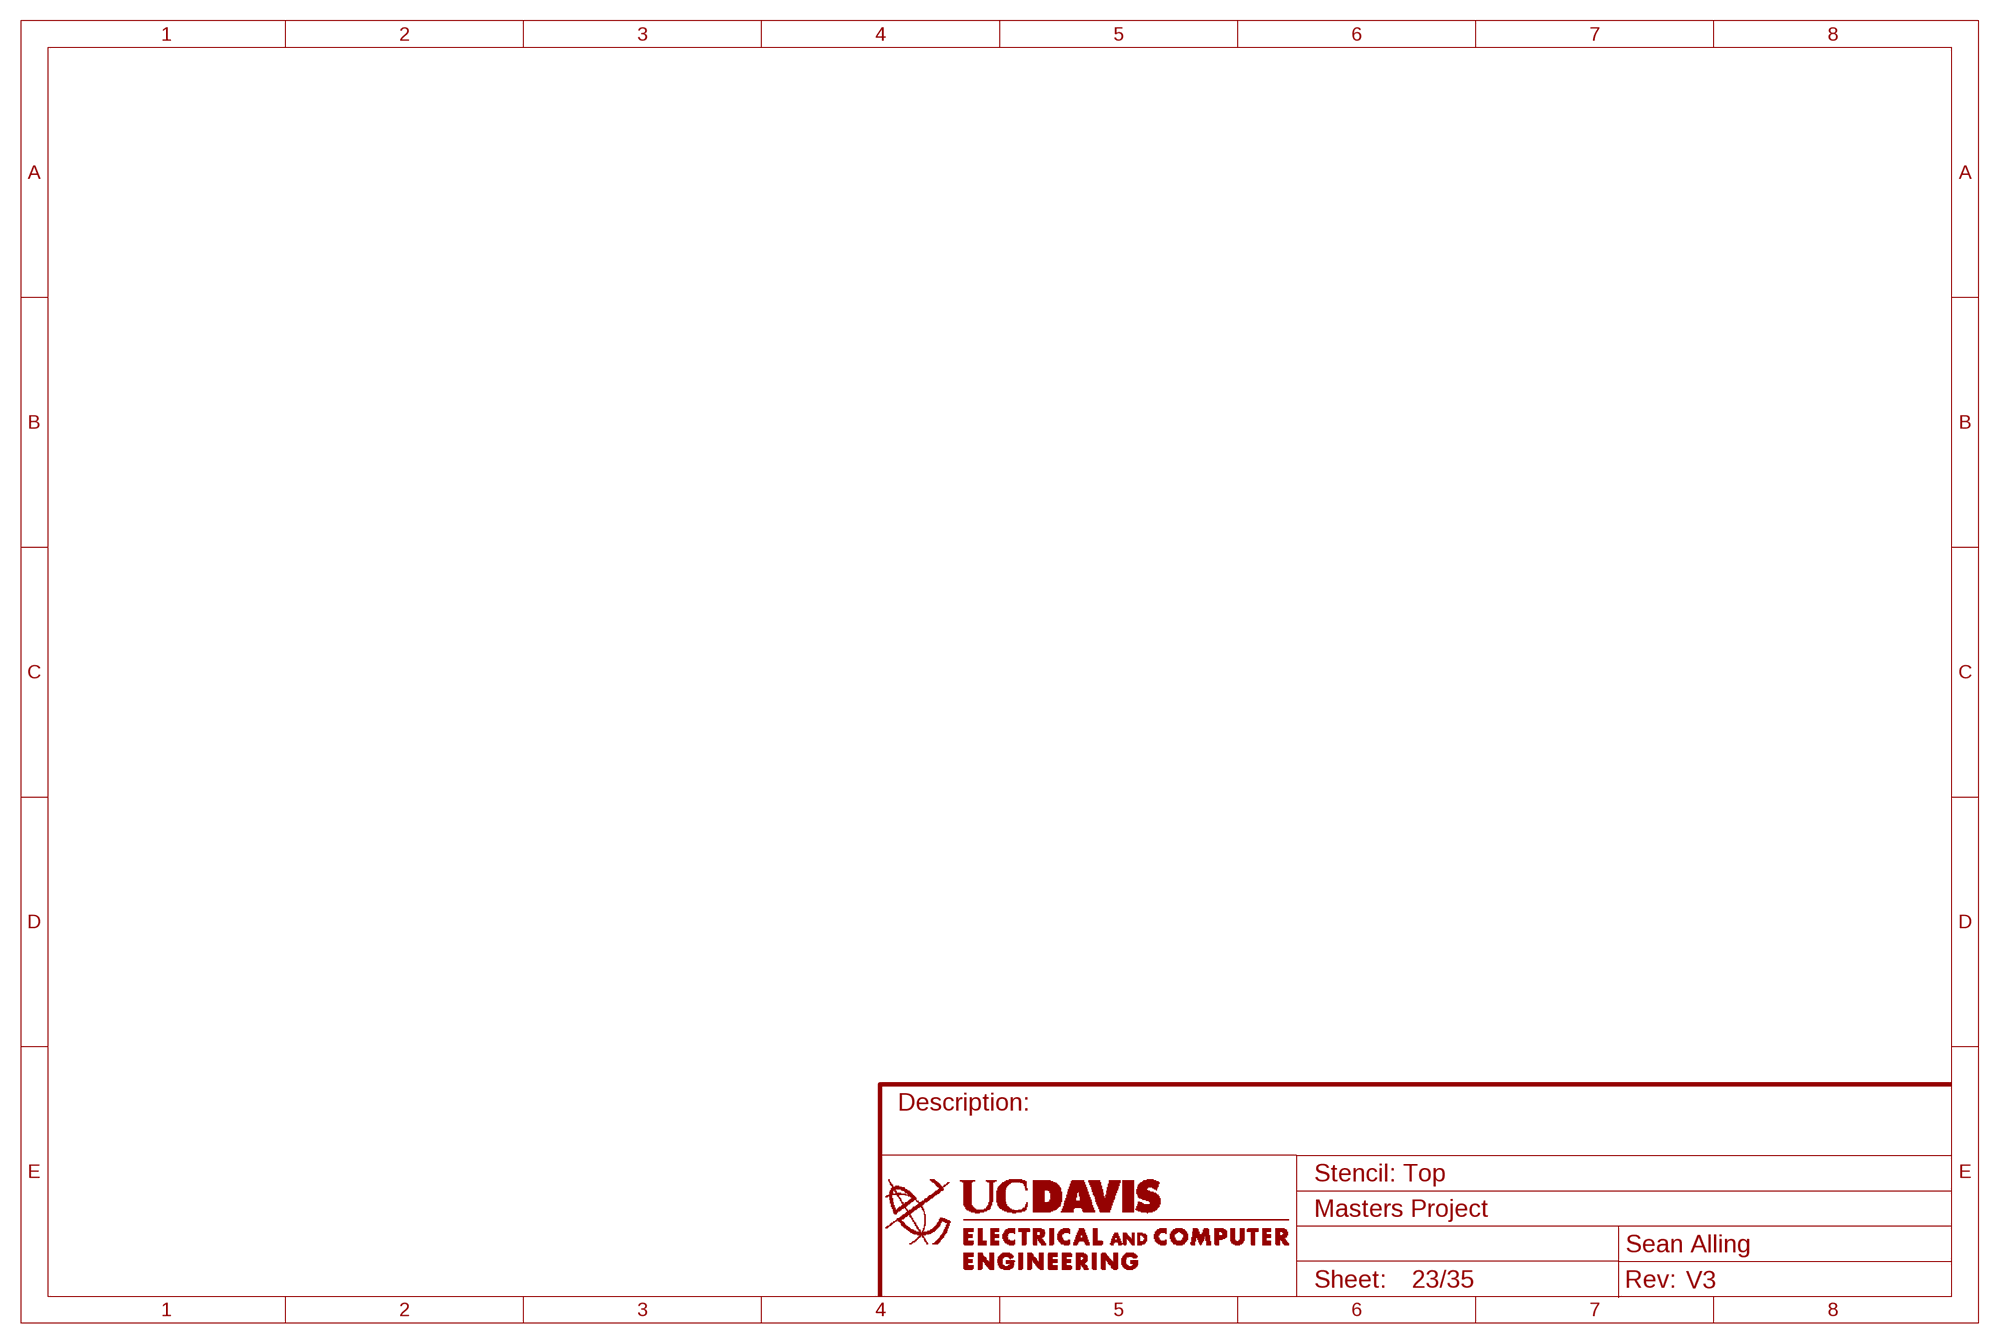
[diagram p22: schematic, sheet 23]
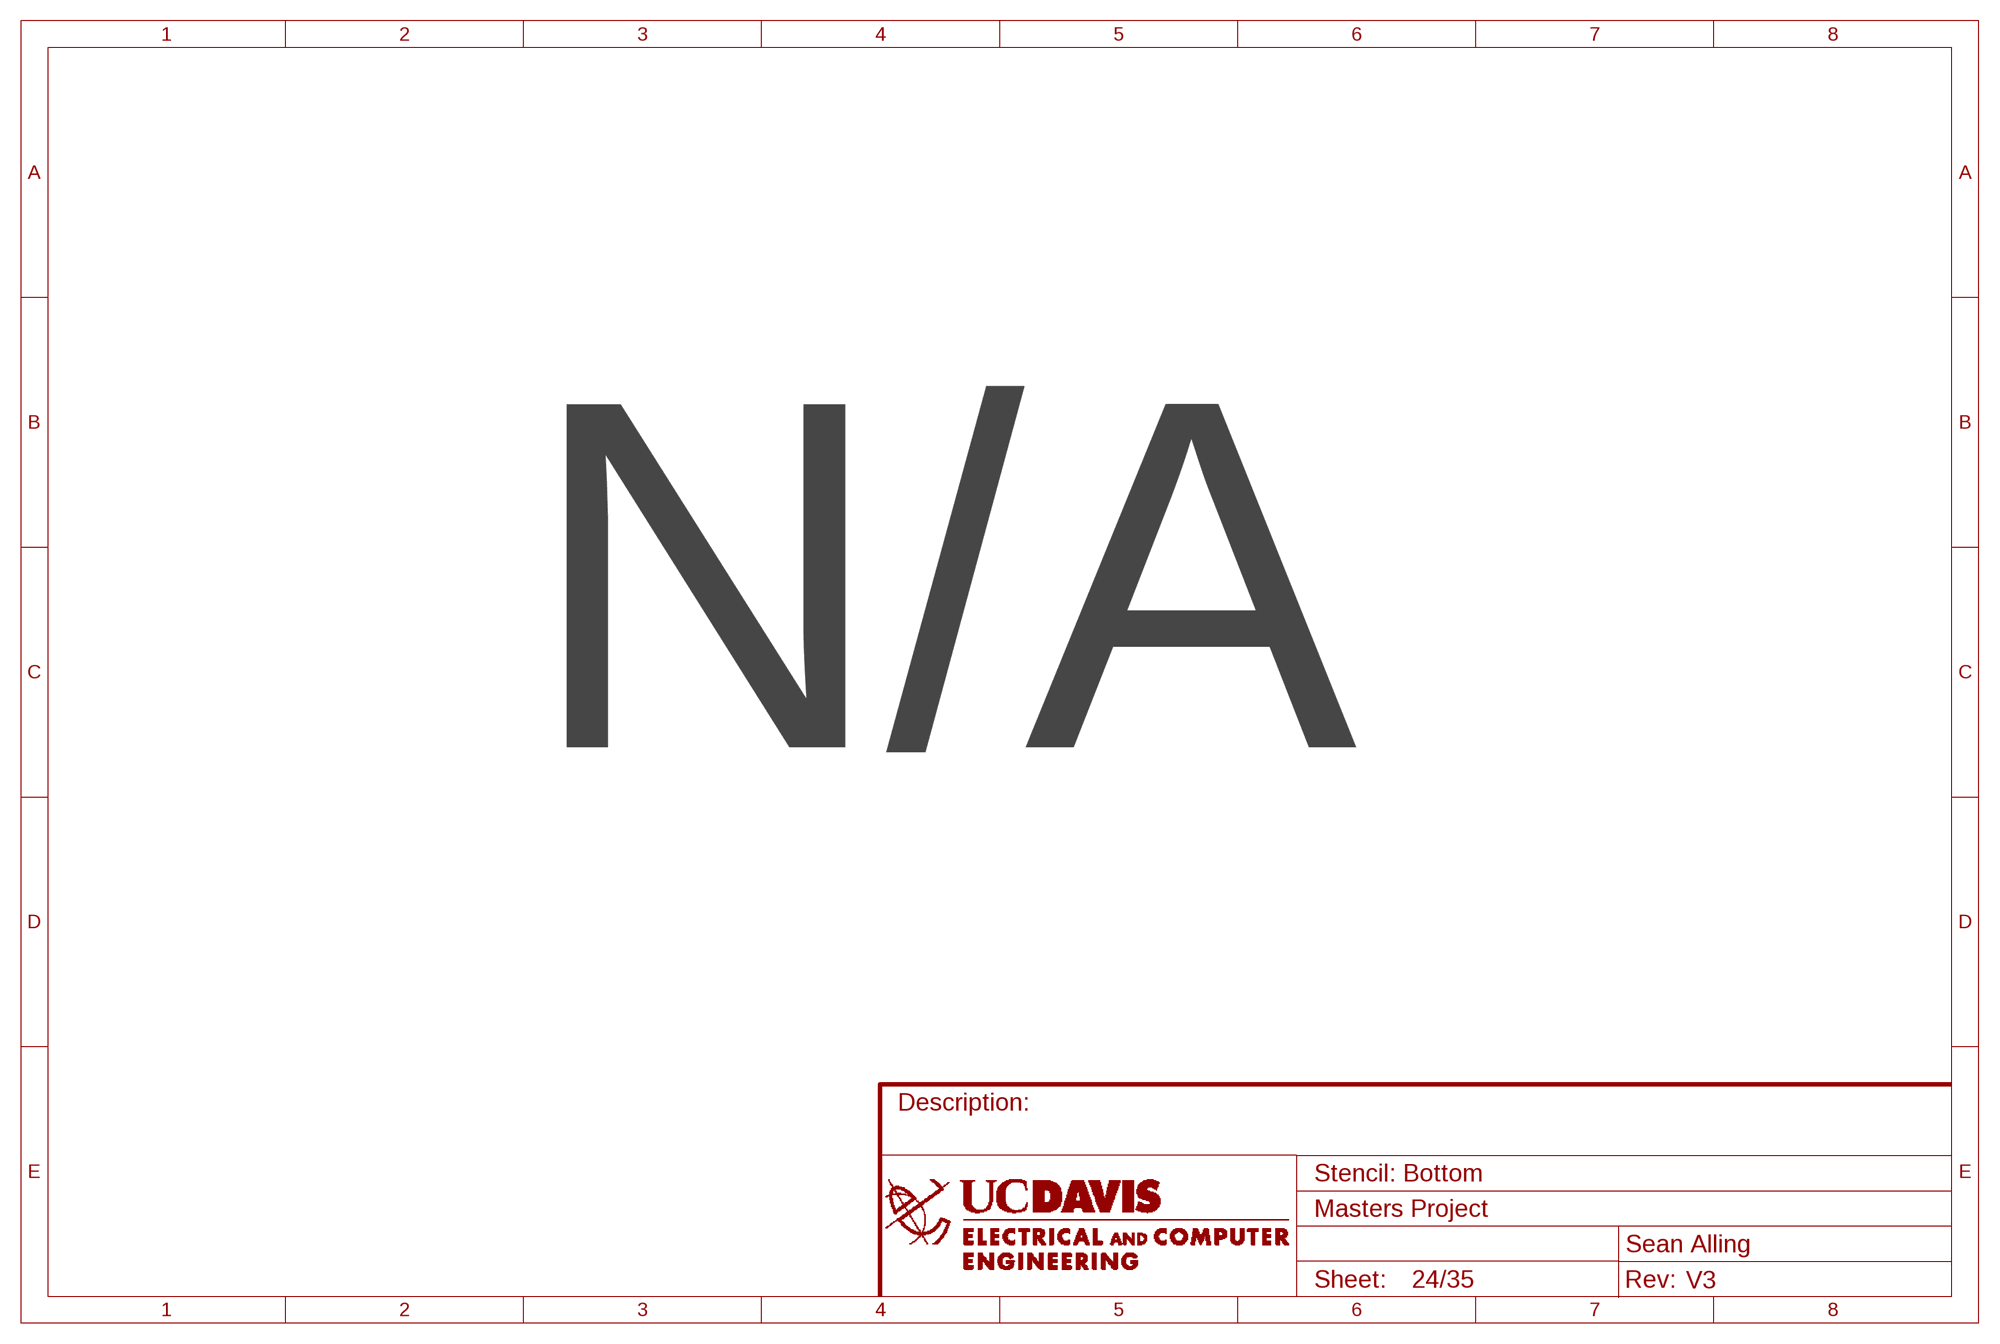
[diagram p23: schematic, sheet 24]
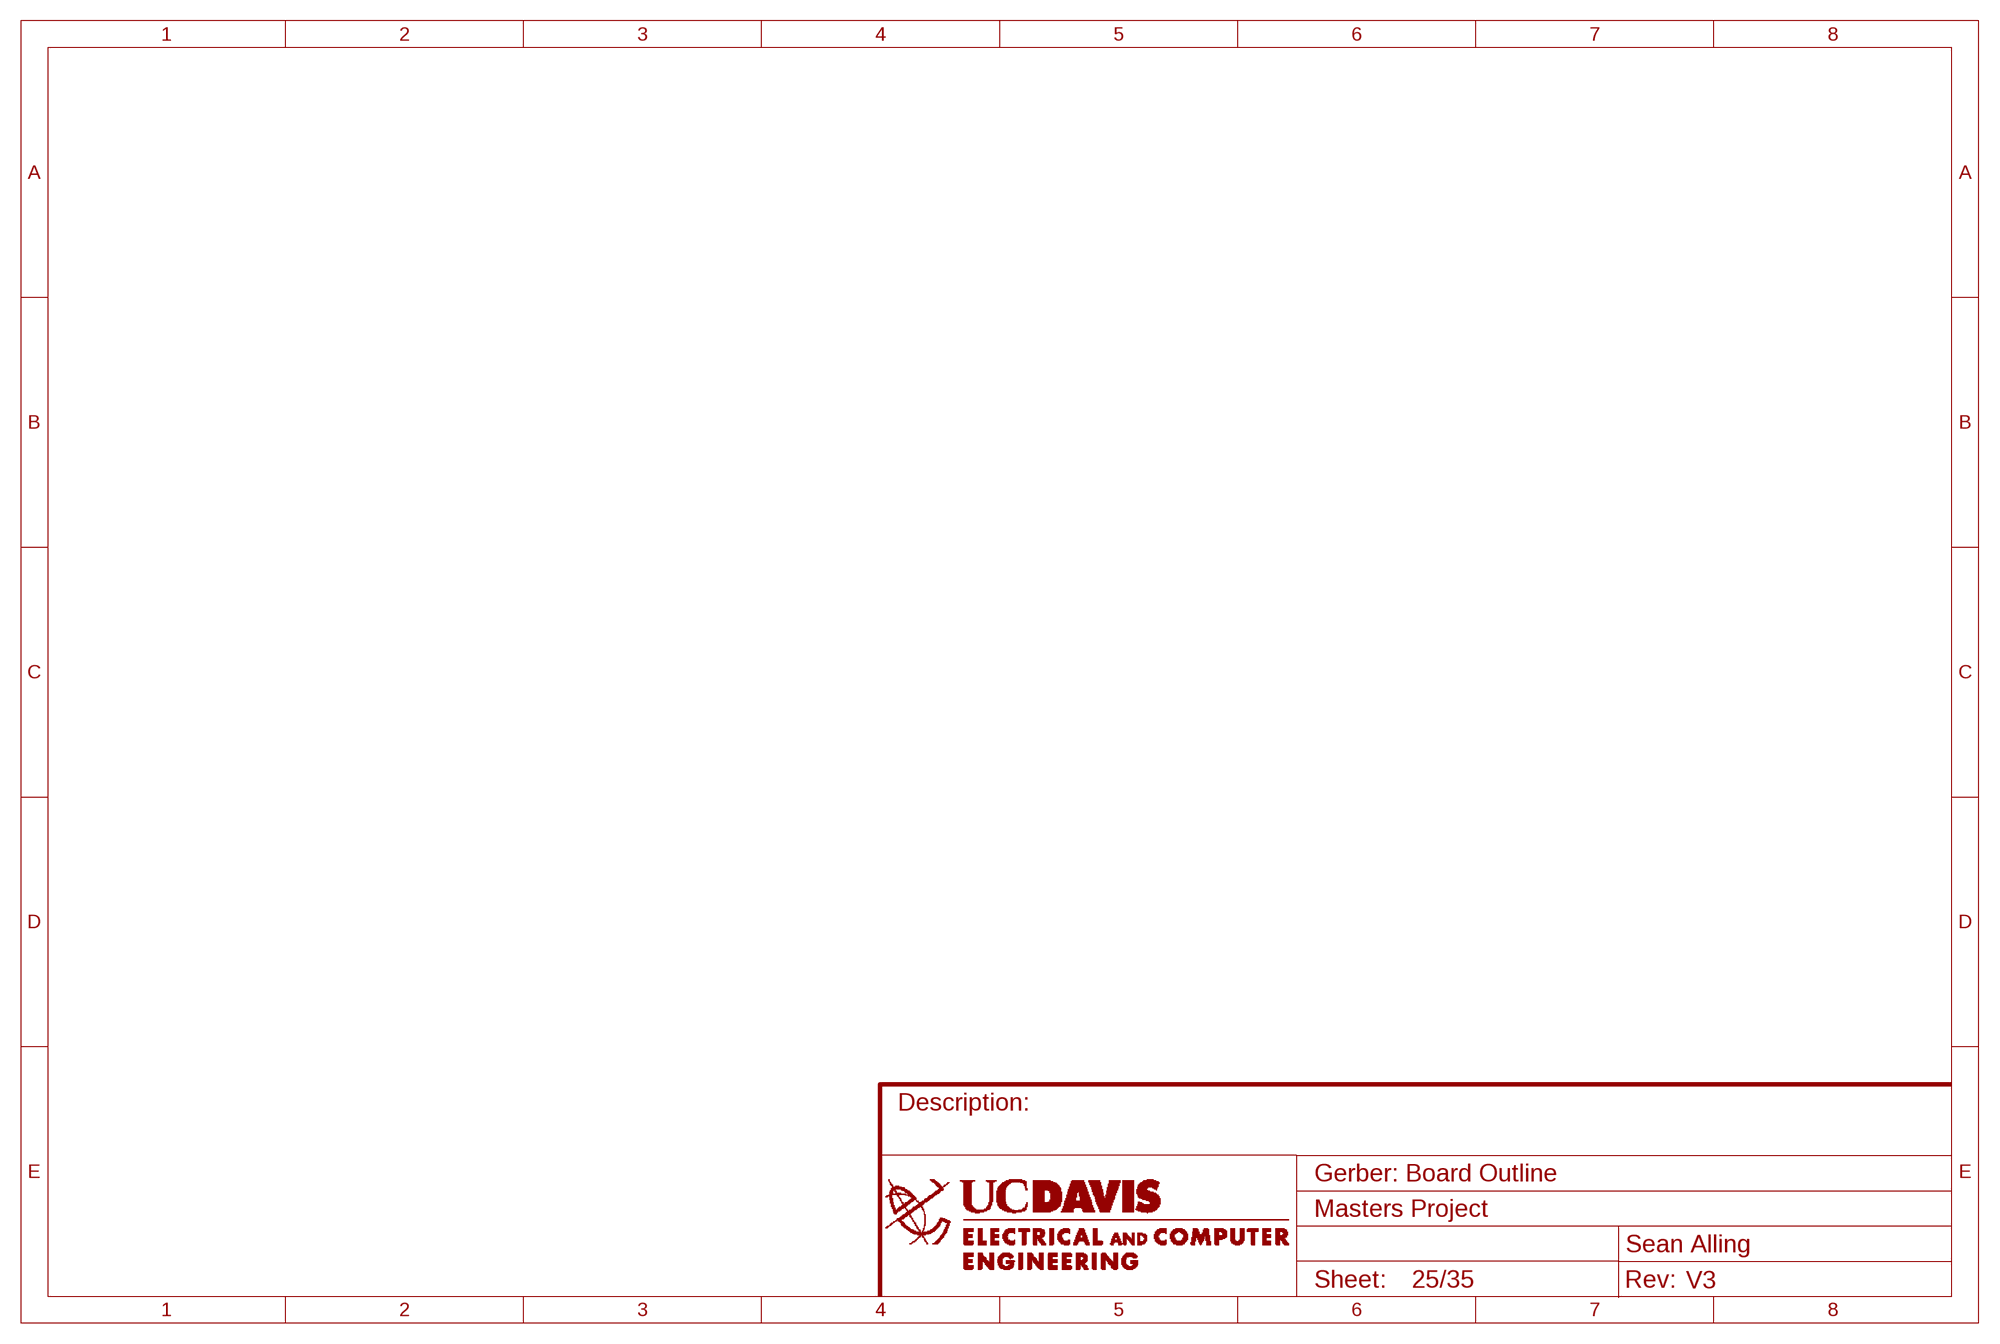
[diagram p24: schematic, sheet 25]
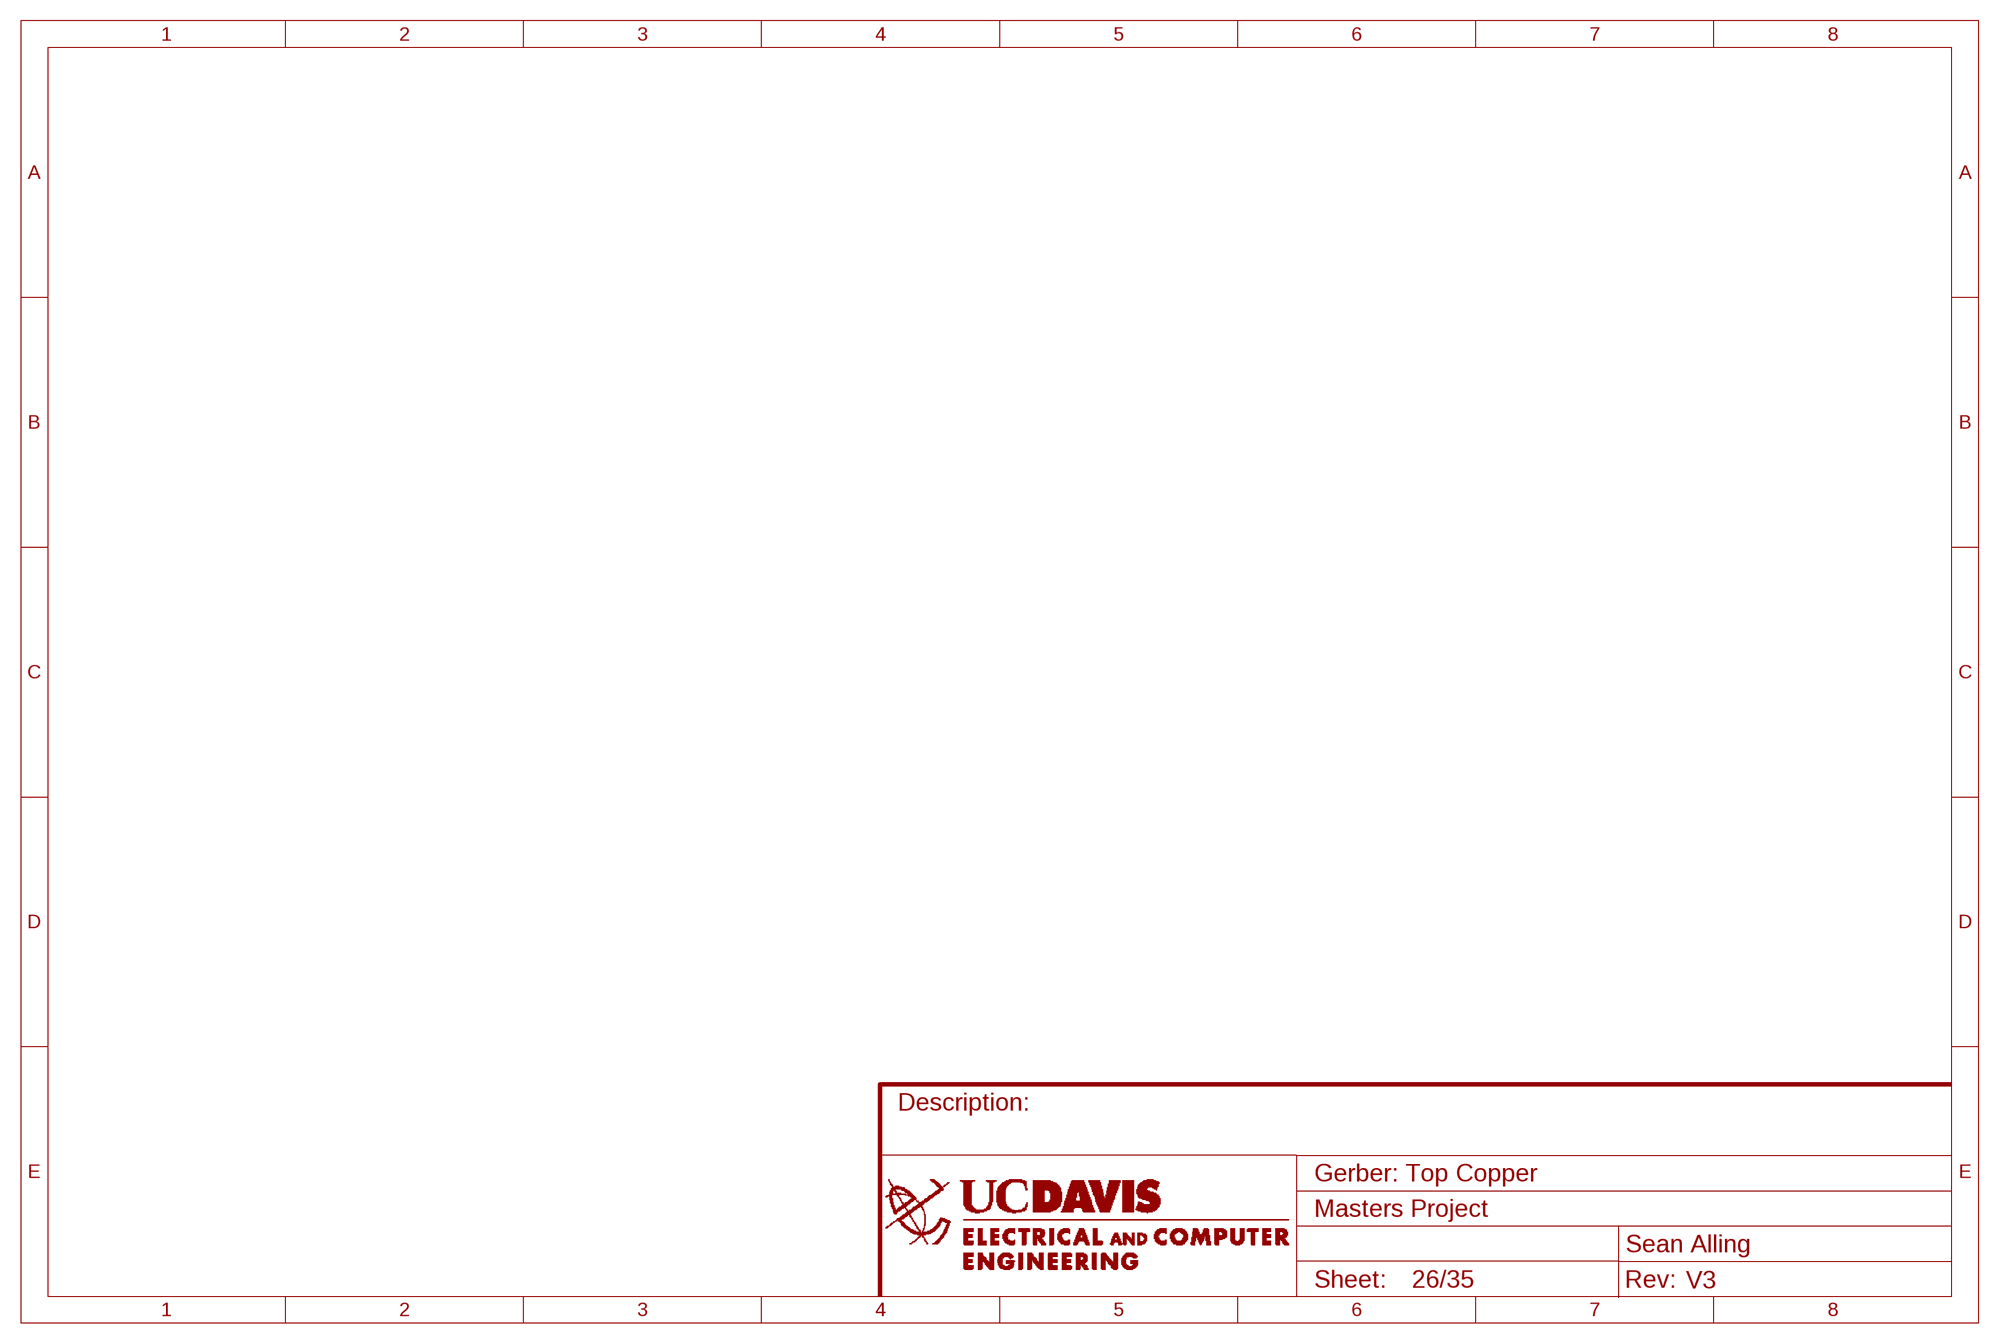
[diagram p25: schematic, sheet 26]
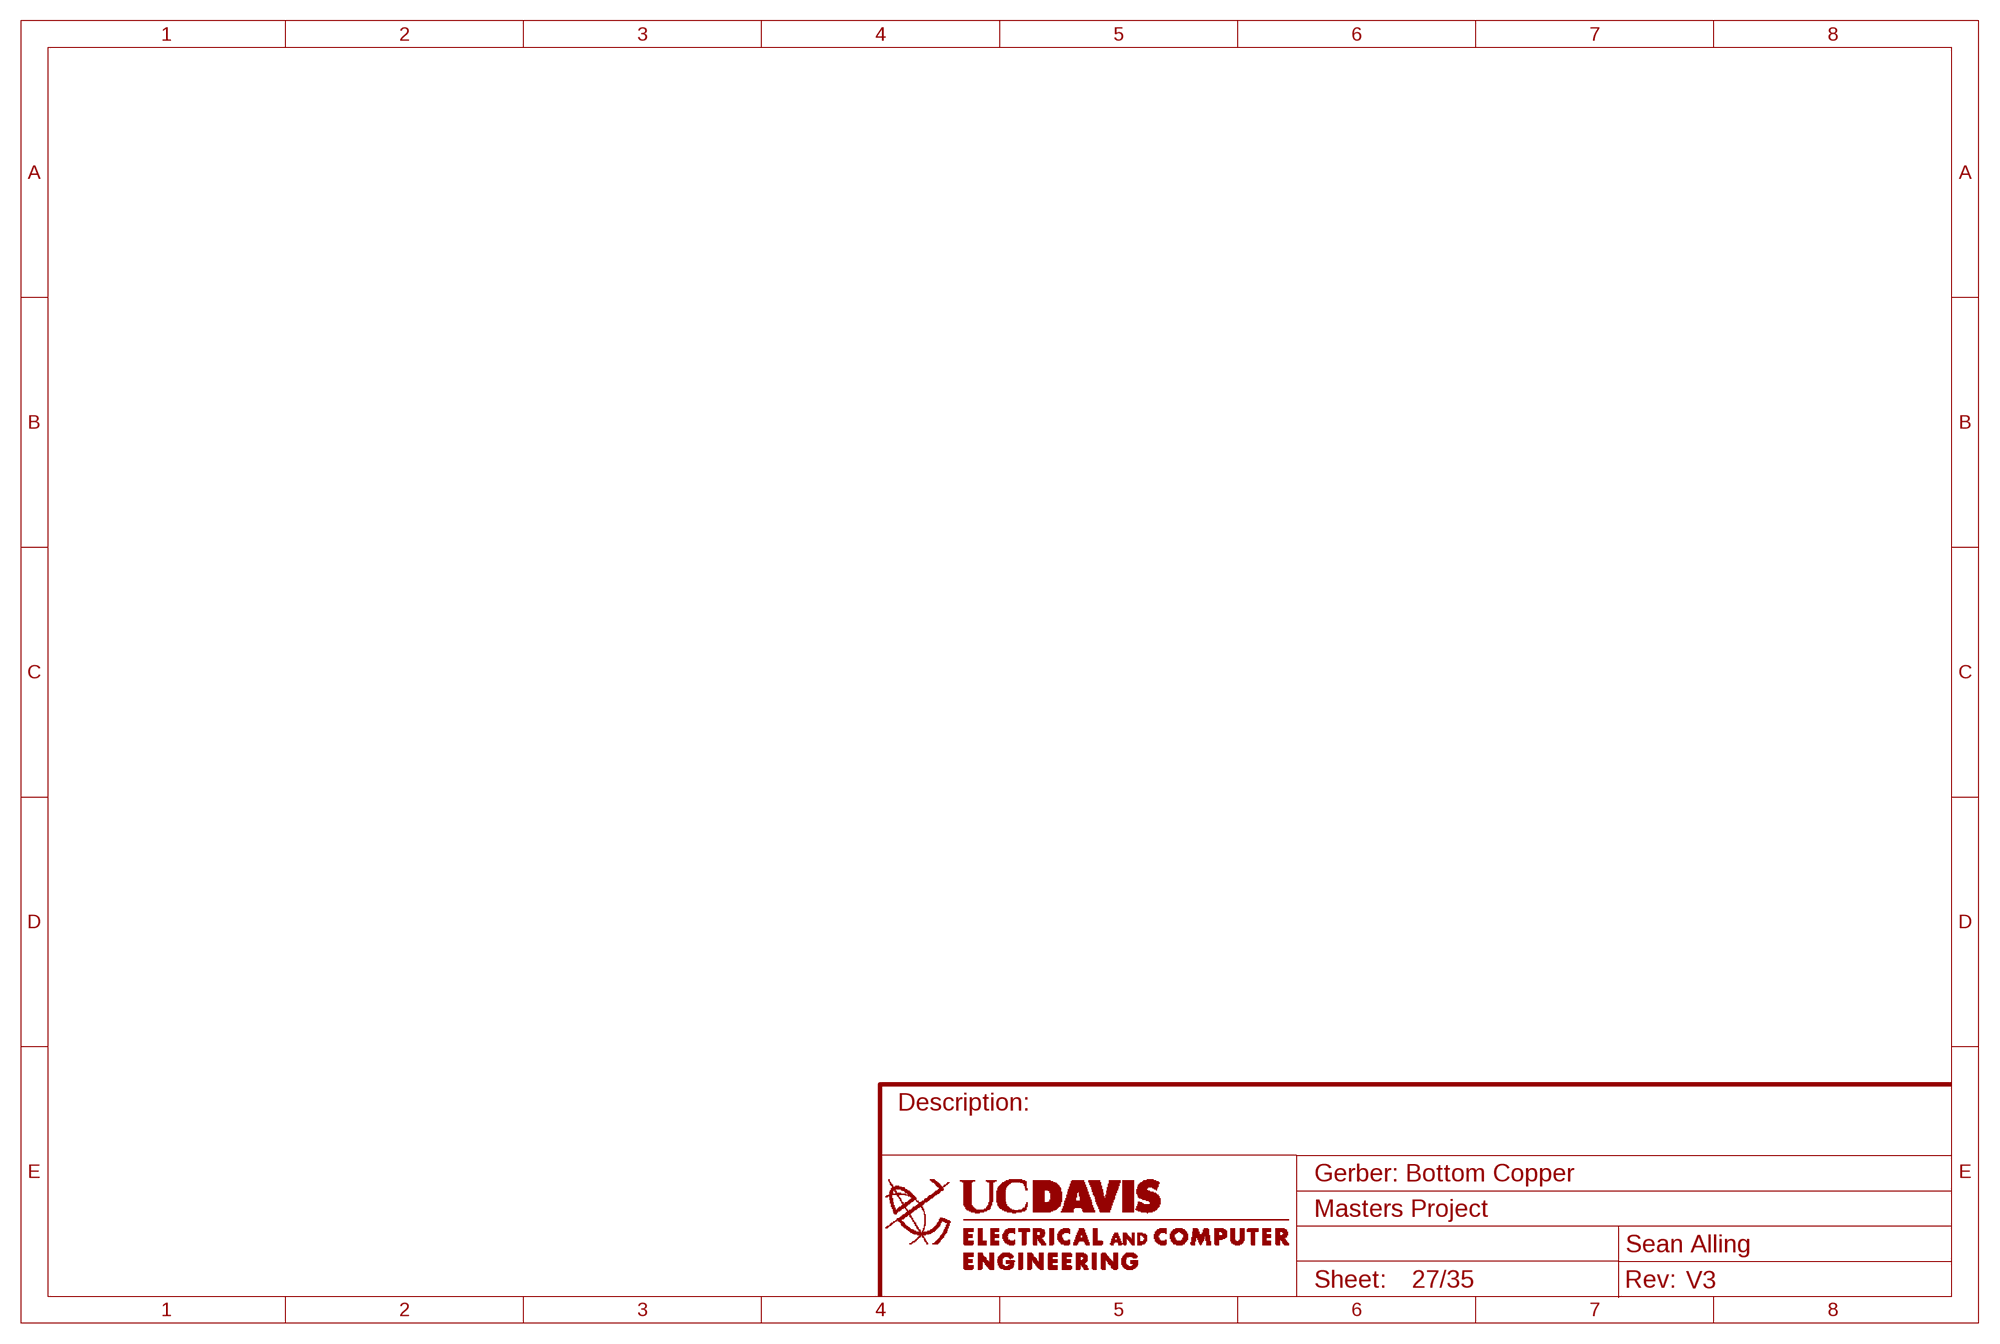
[diagram p26: schematic, sheet 27]
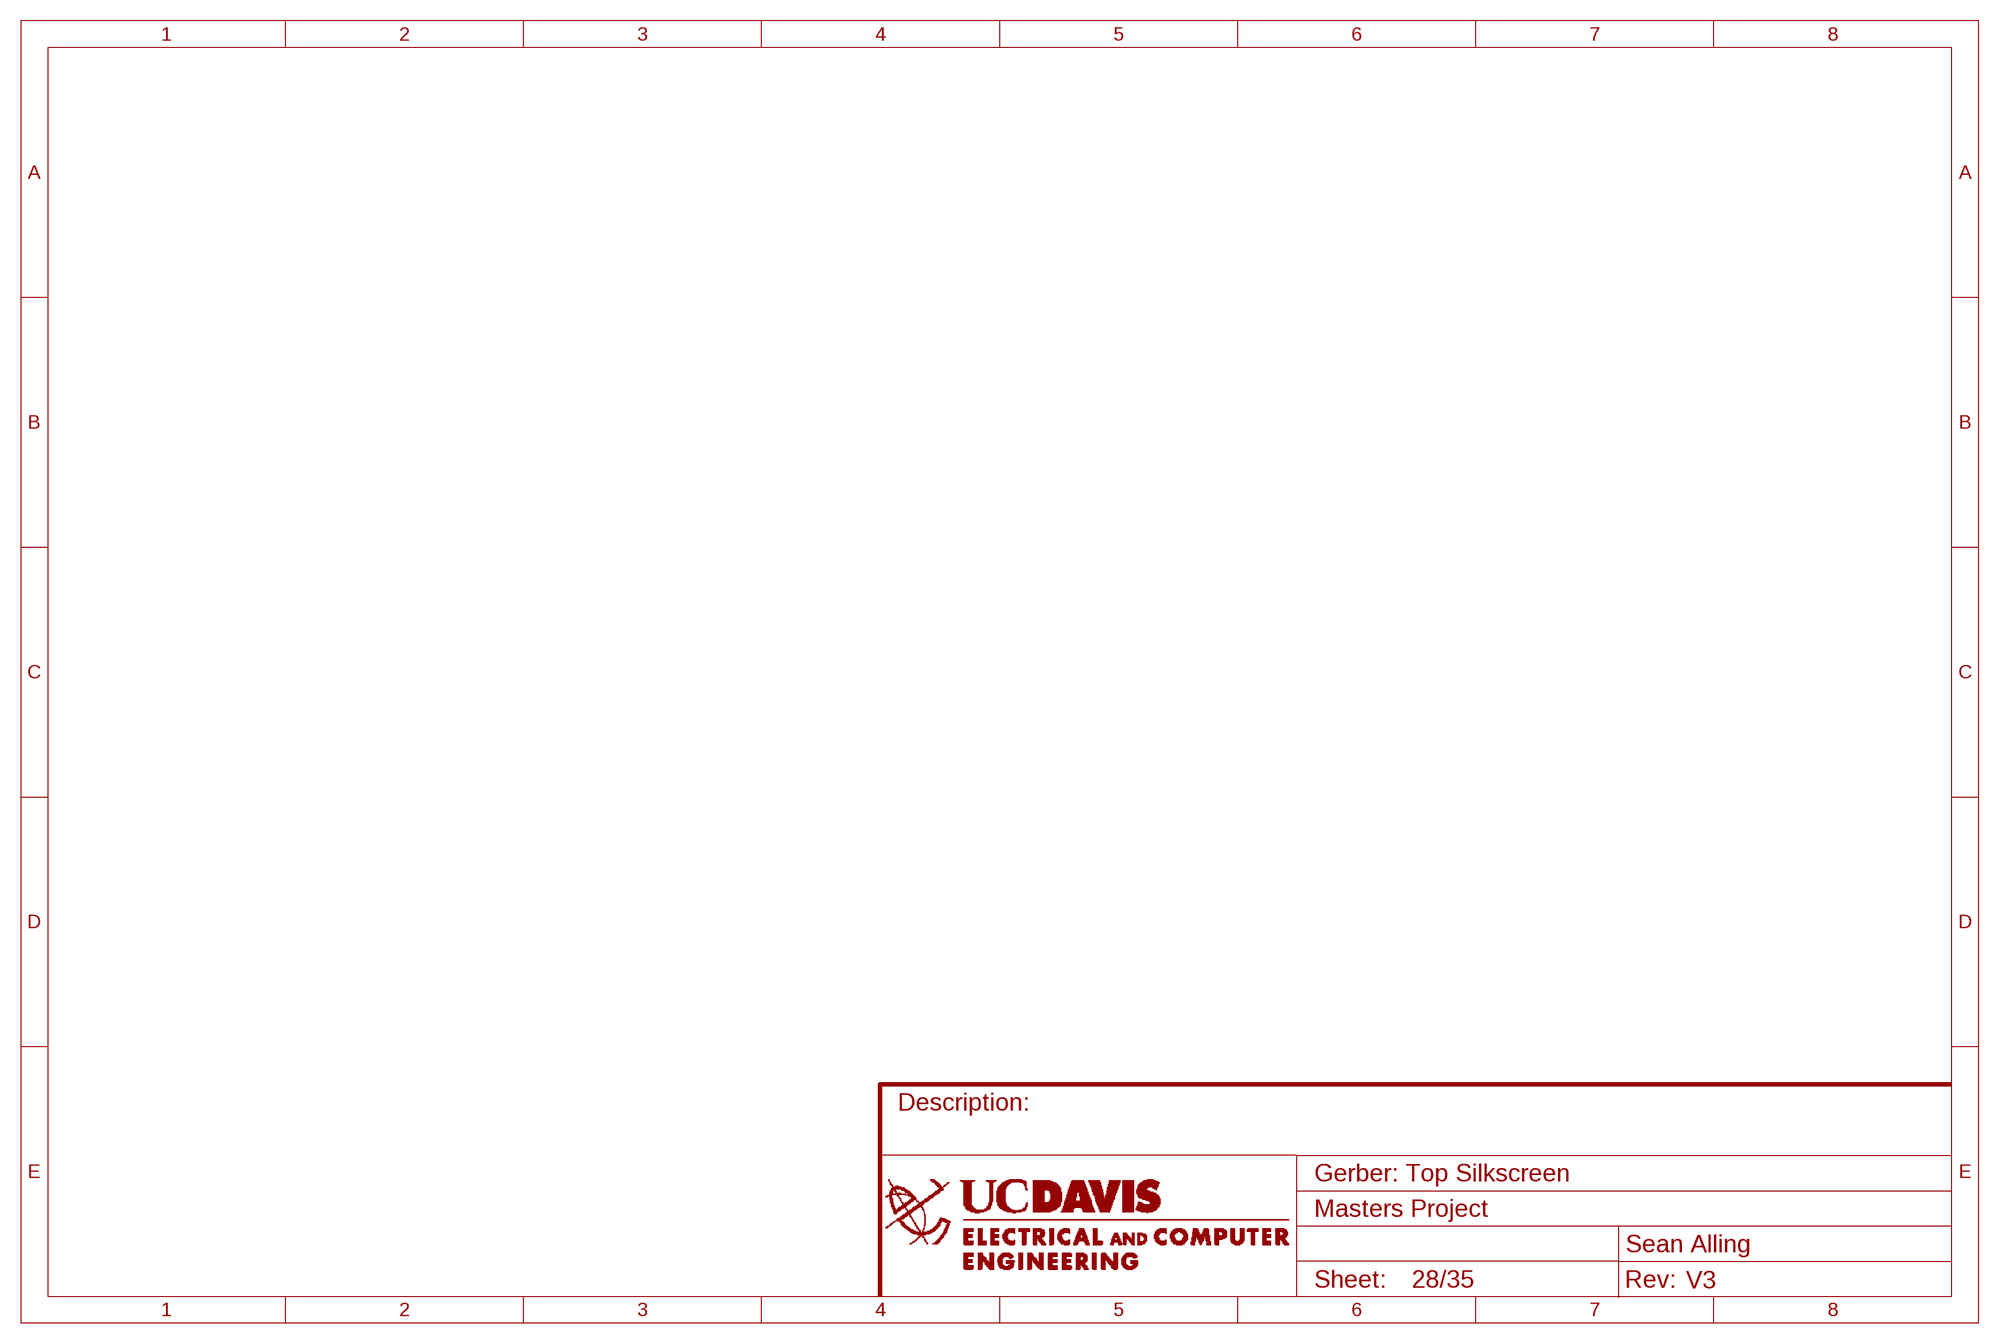
[diagram p27: schematic, sheet 28]
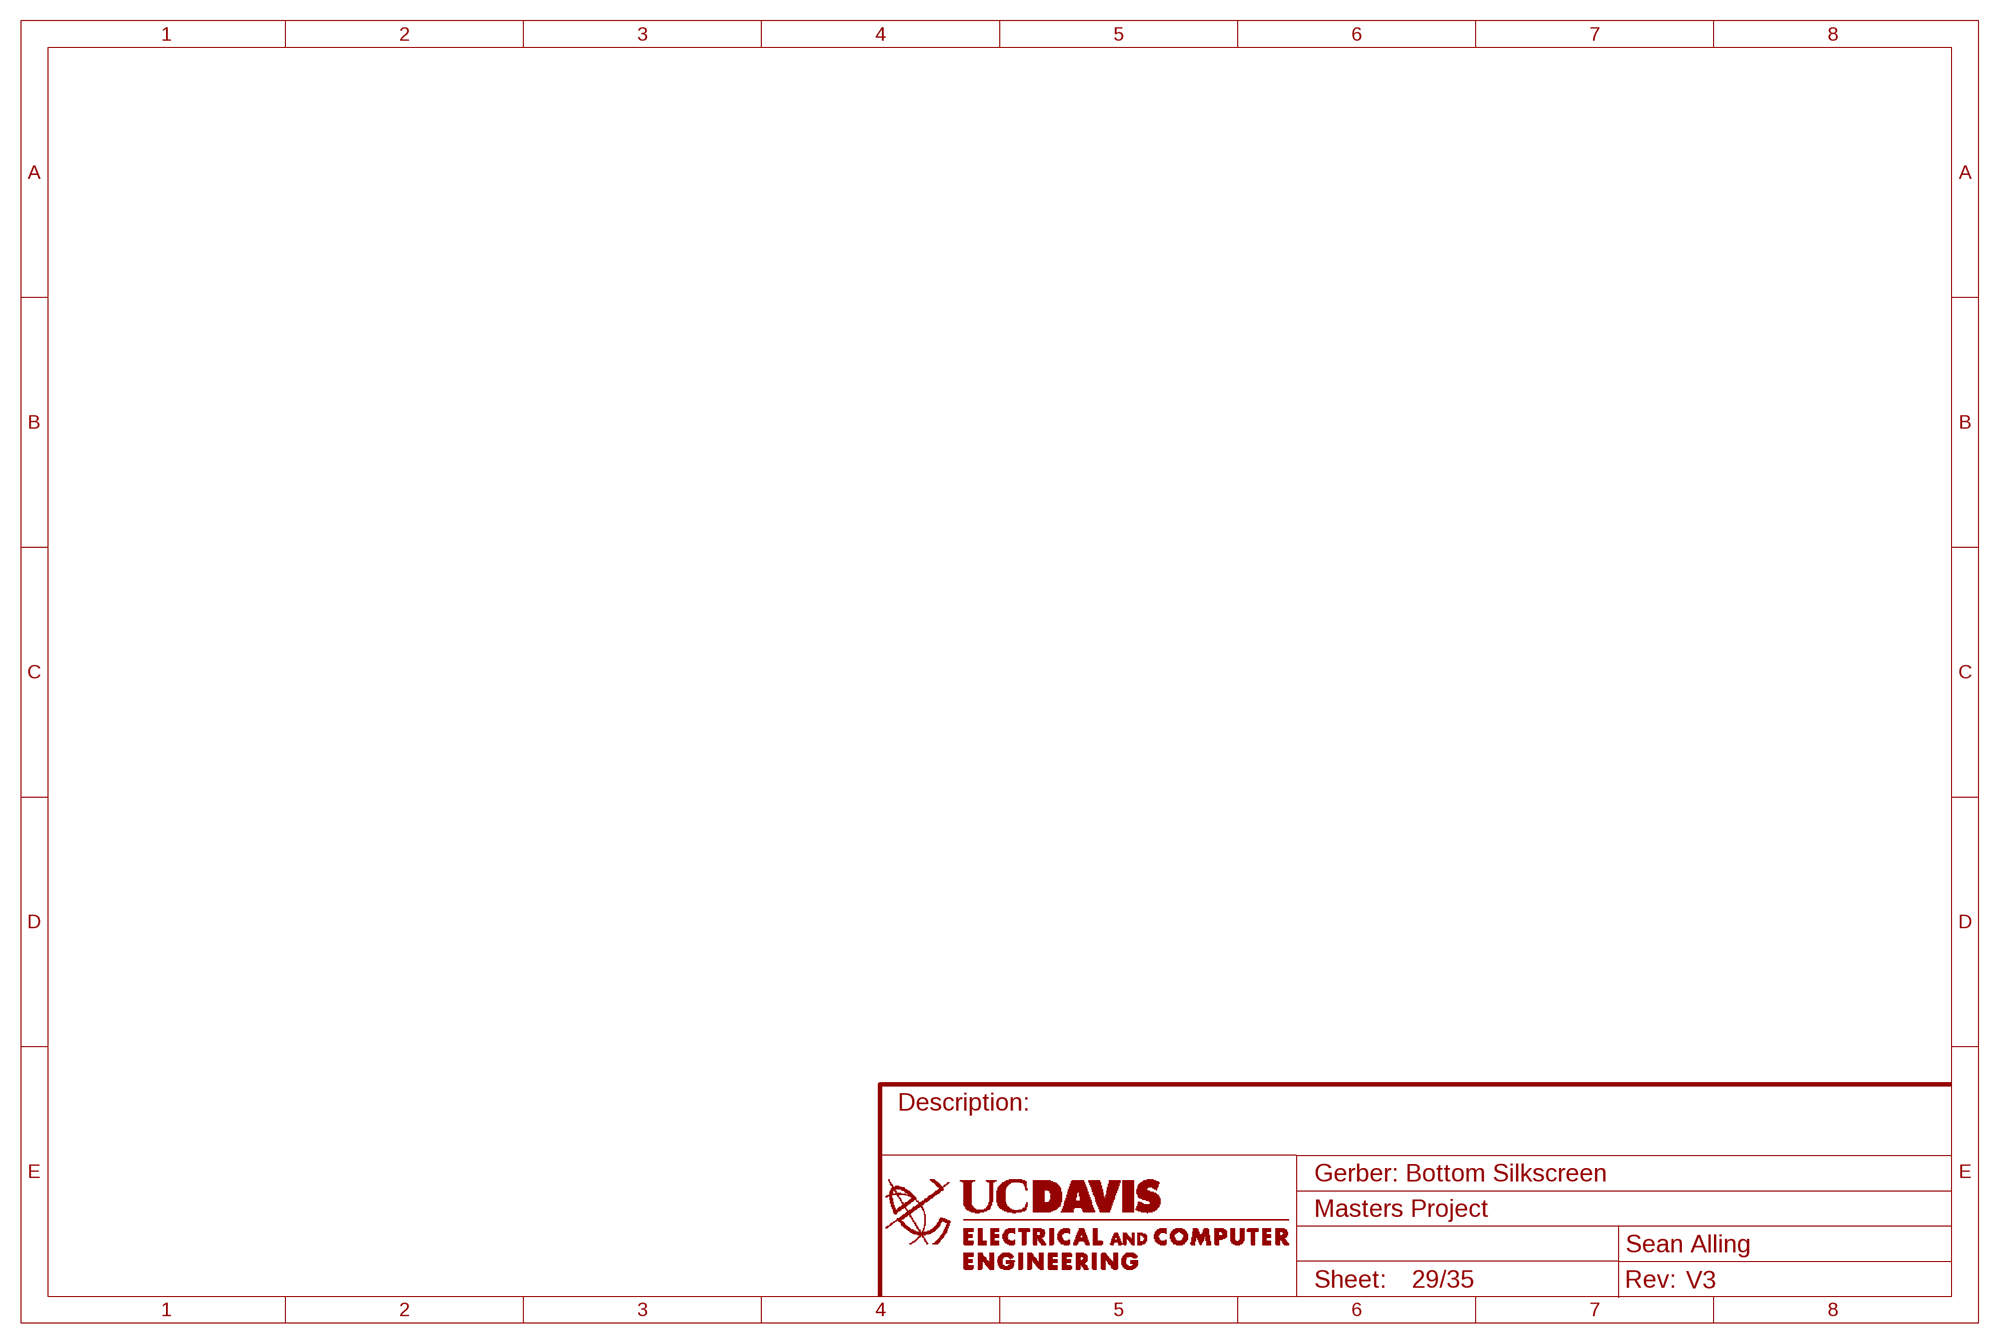
[diagram p28: schematic, sheet 29]
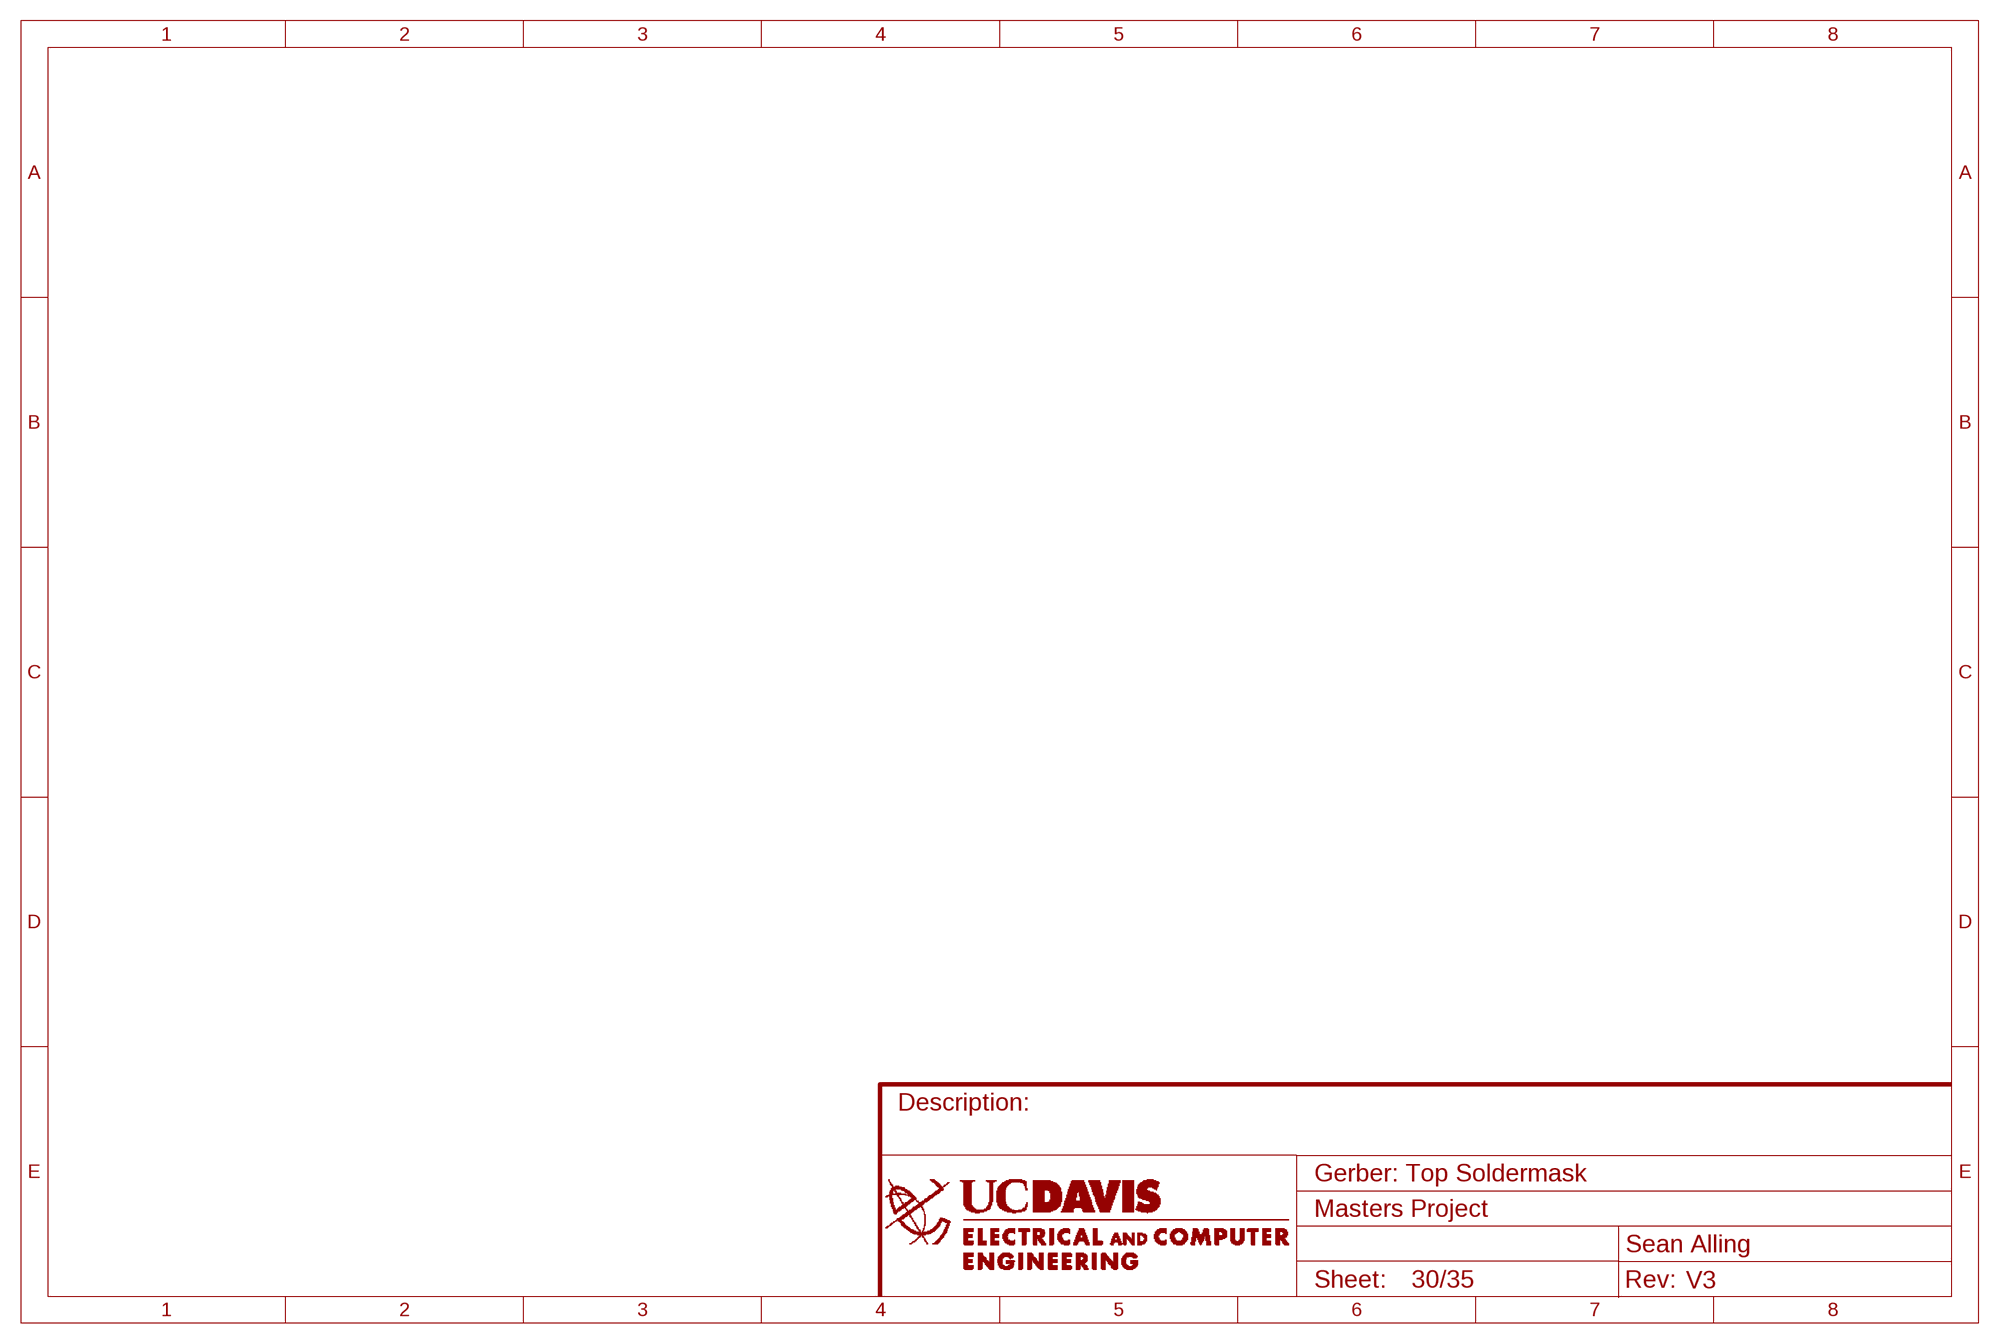
[diagram p29: schematic, sheet 30]
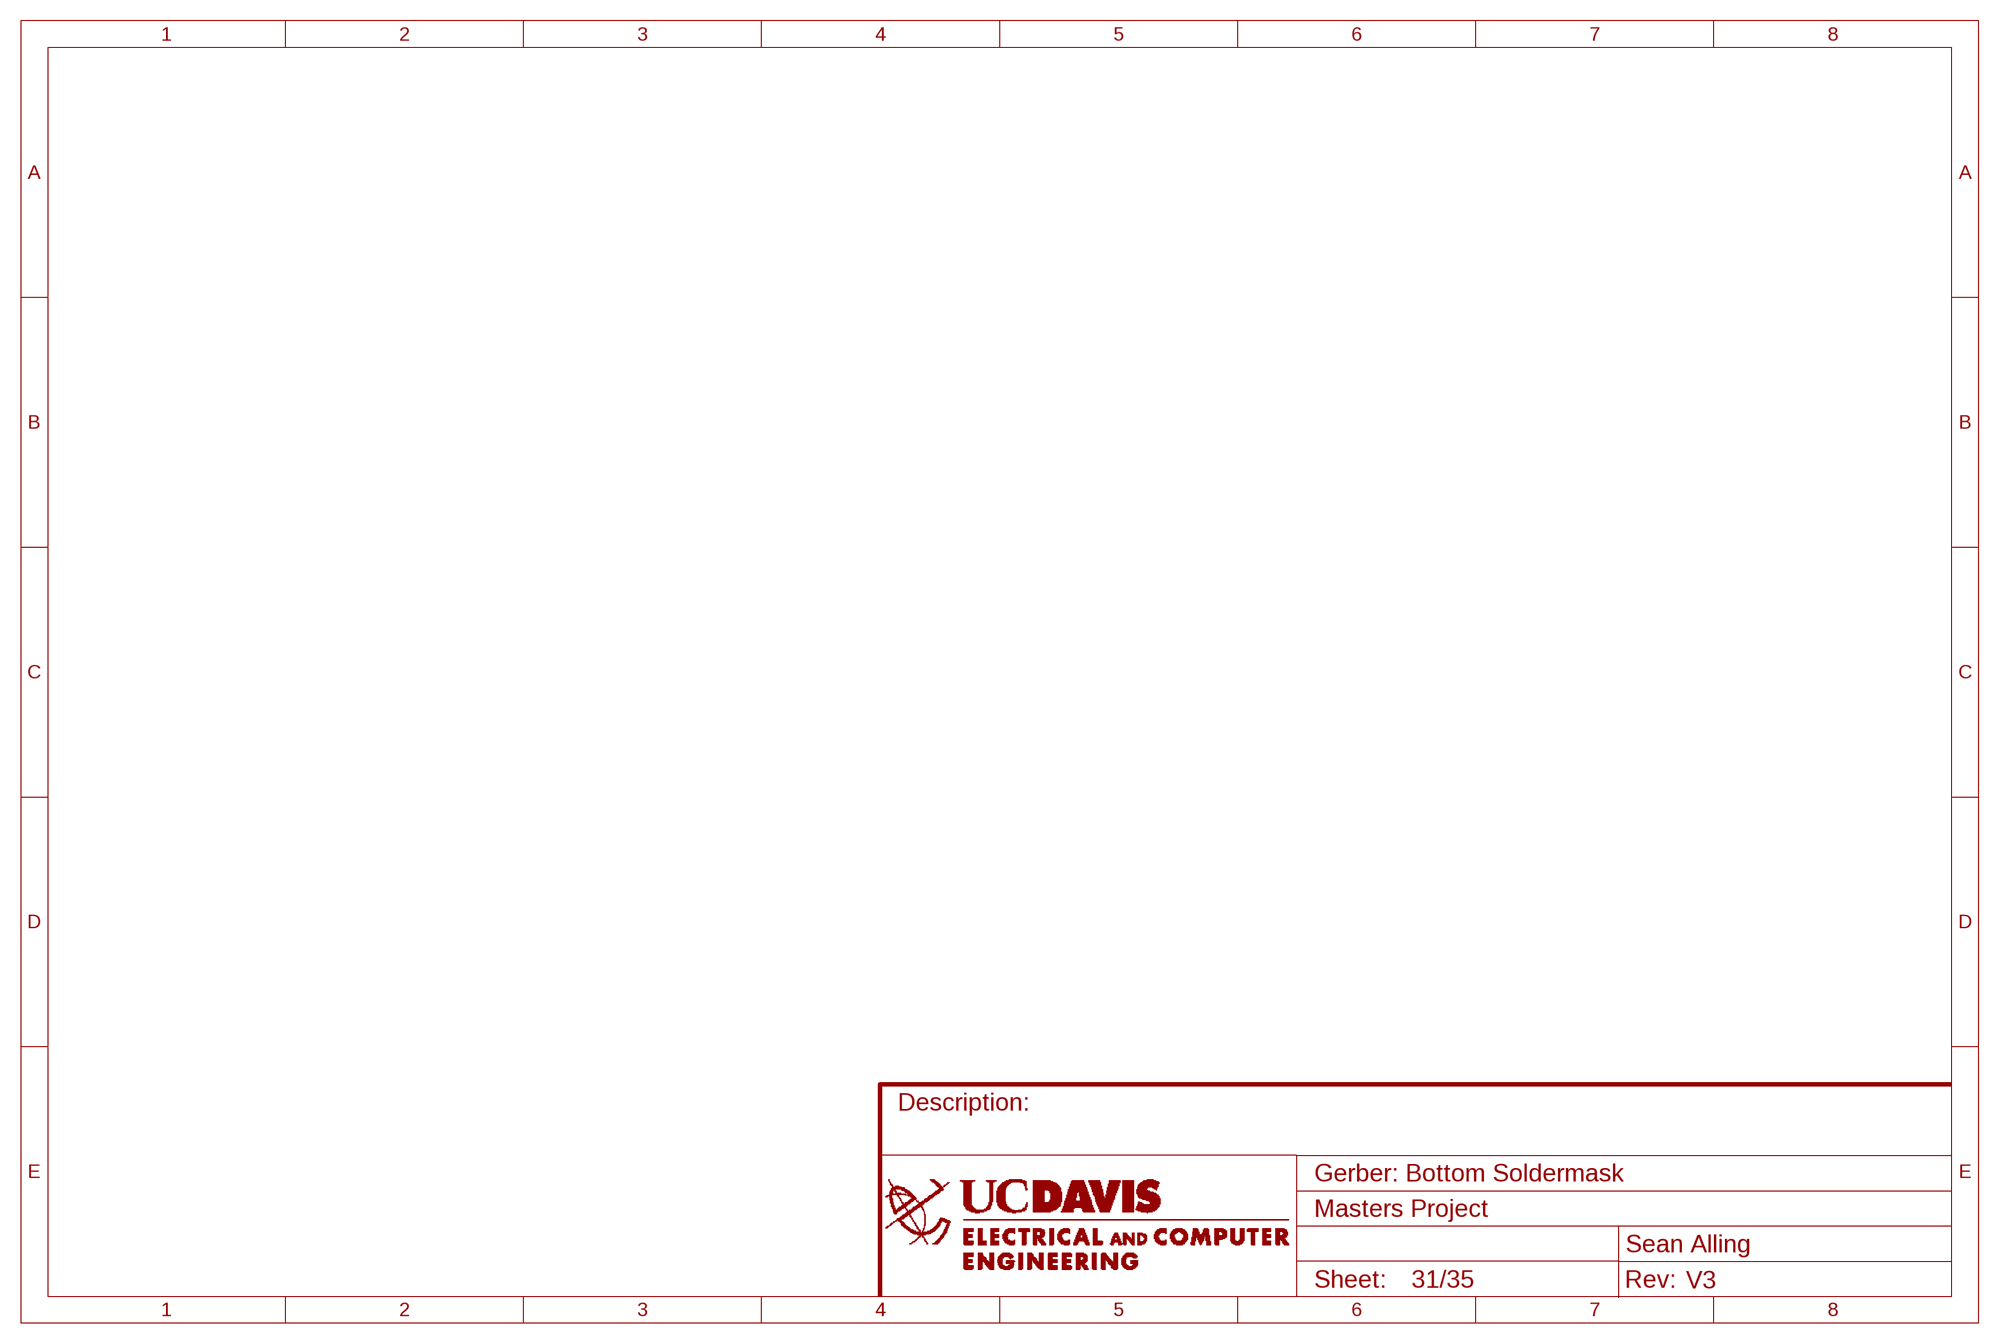
[diagram p30: schematic, sheet 31]
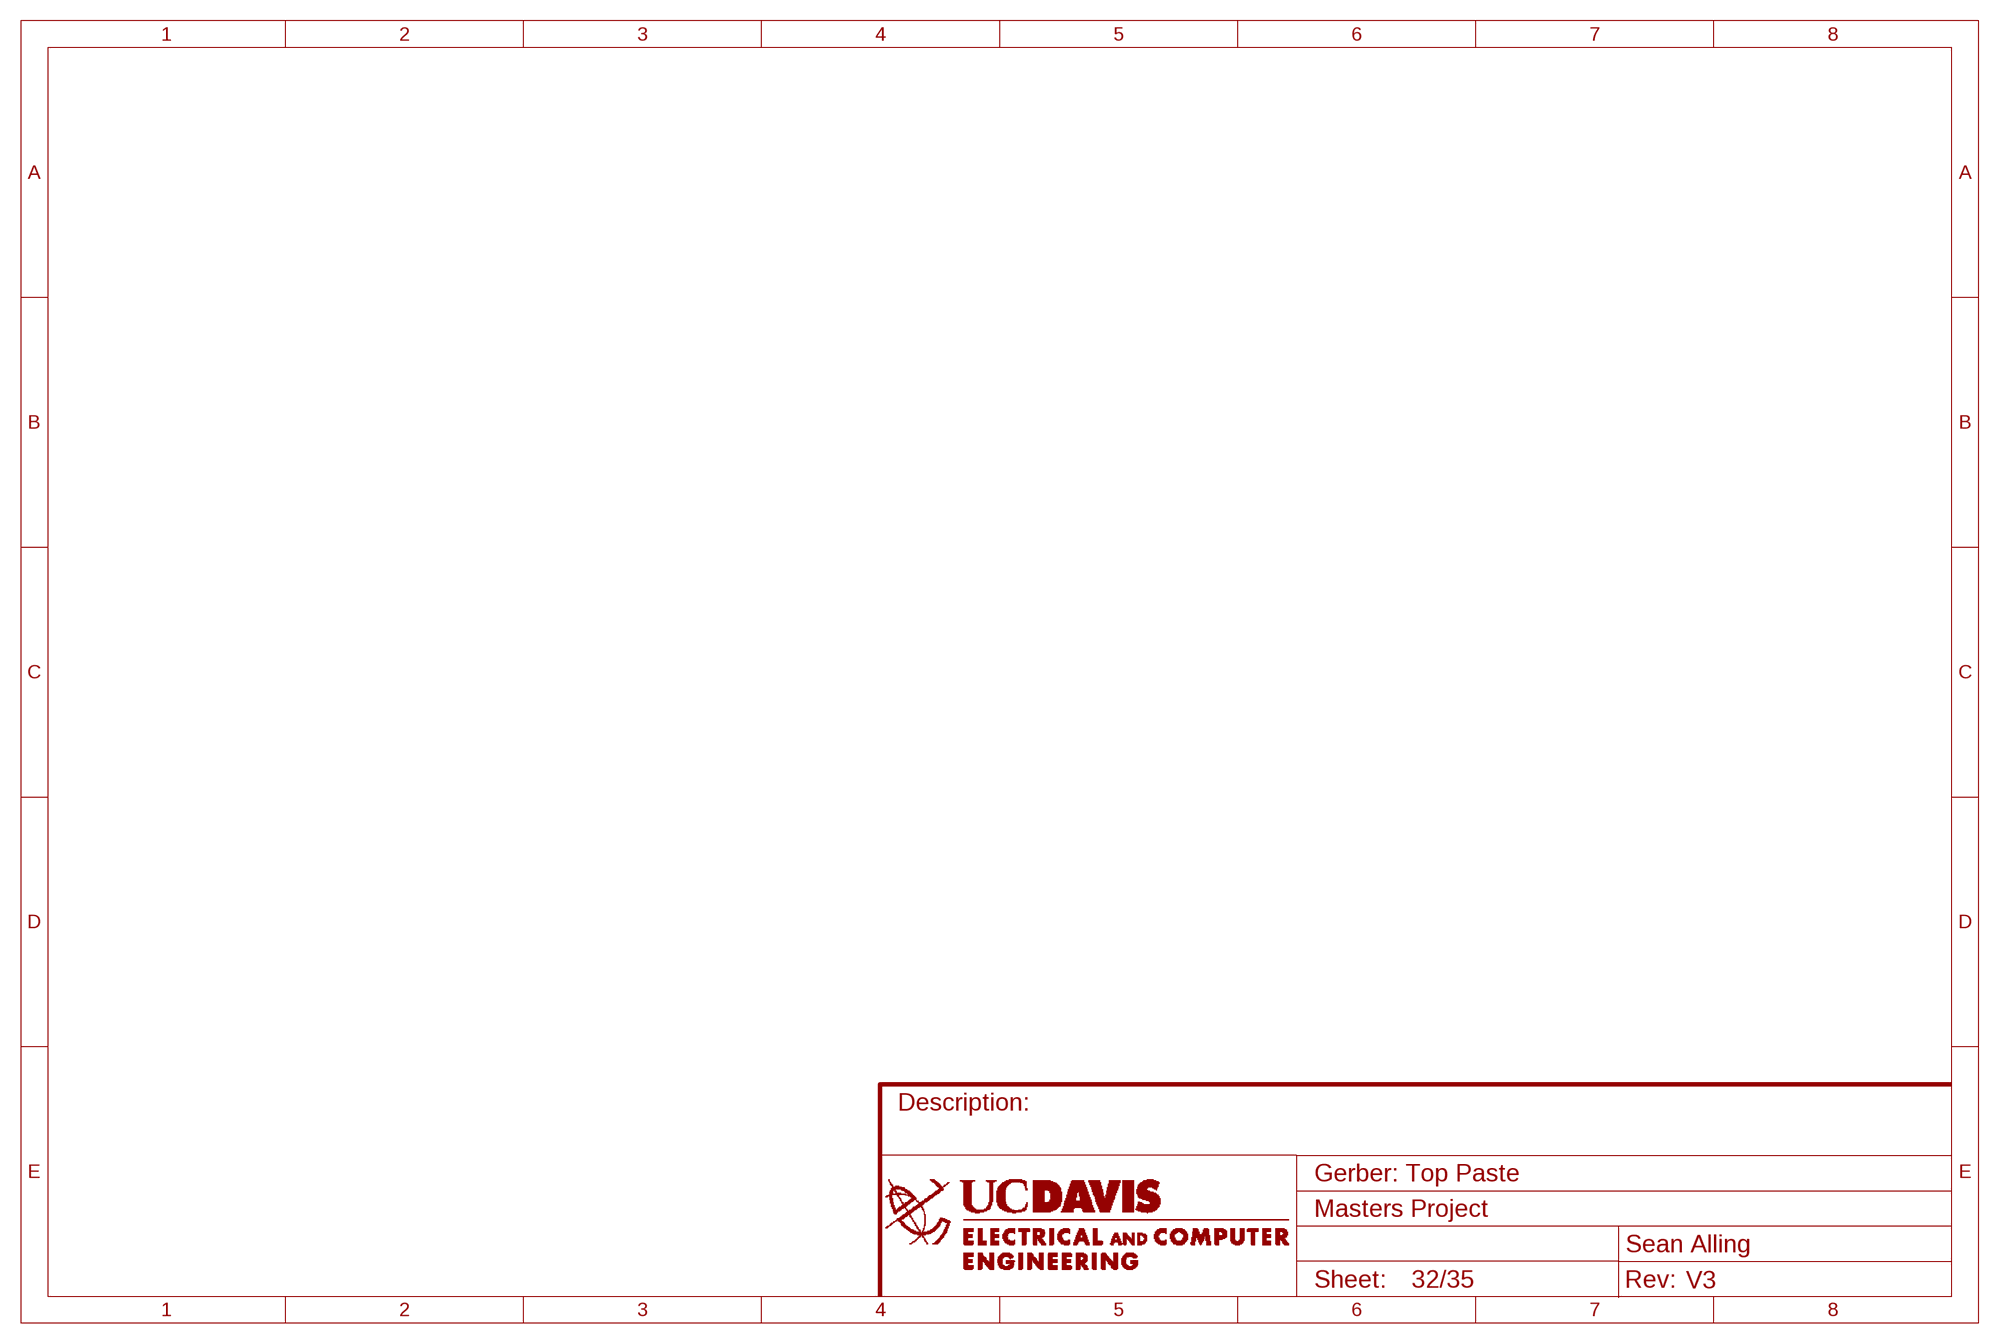
[diagram p31: schematic, sheet 32]
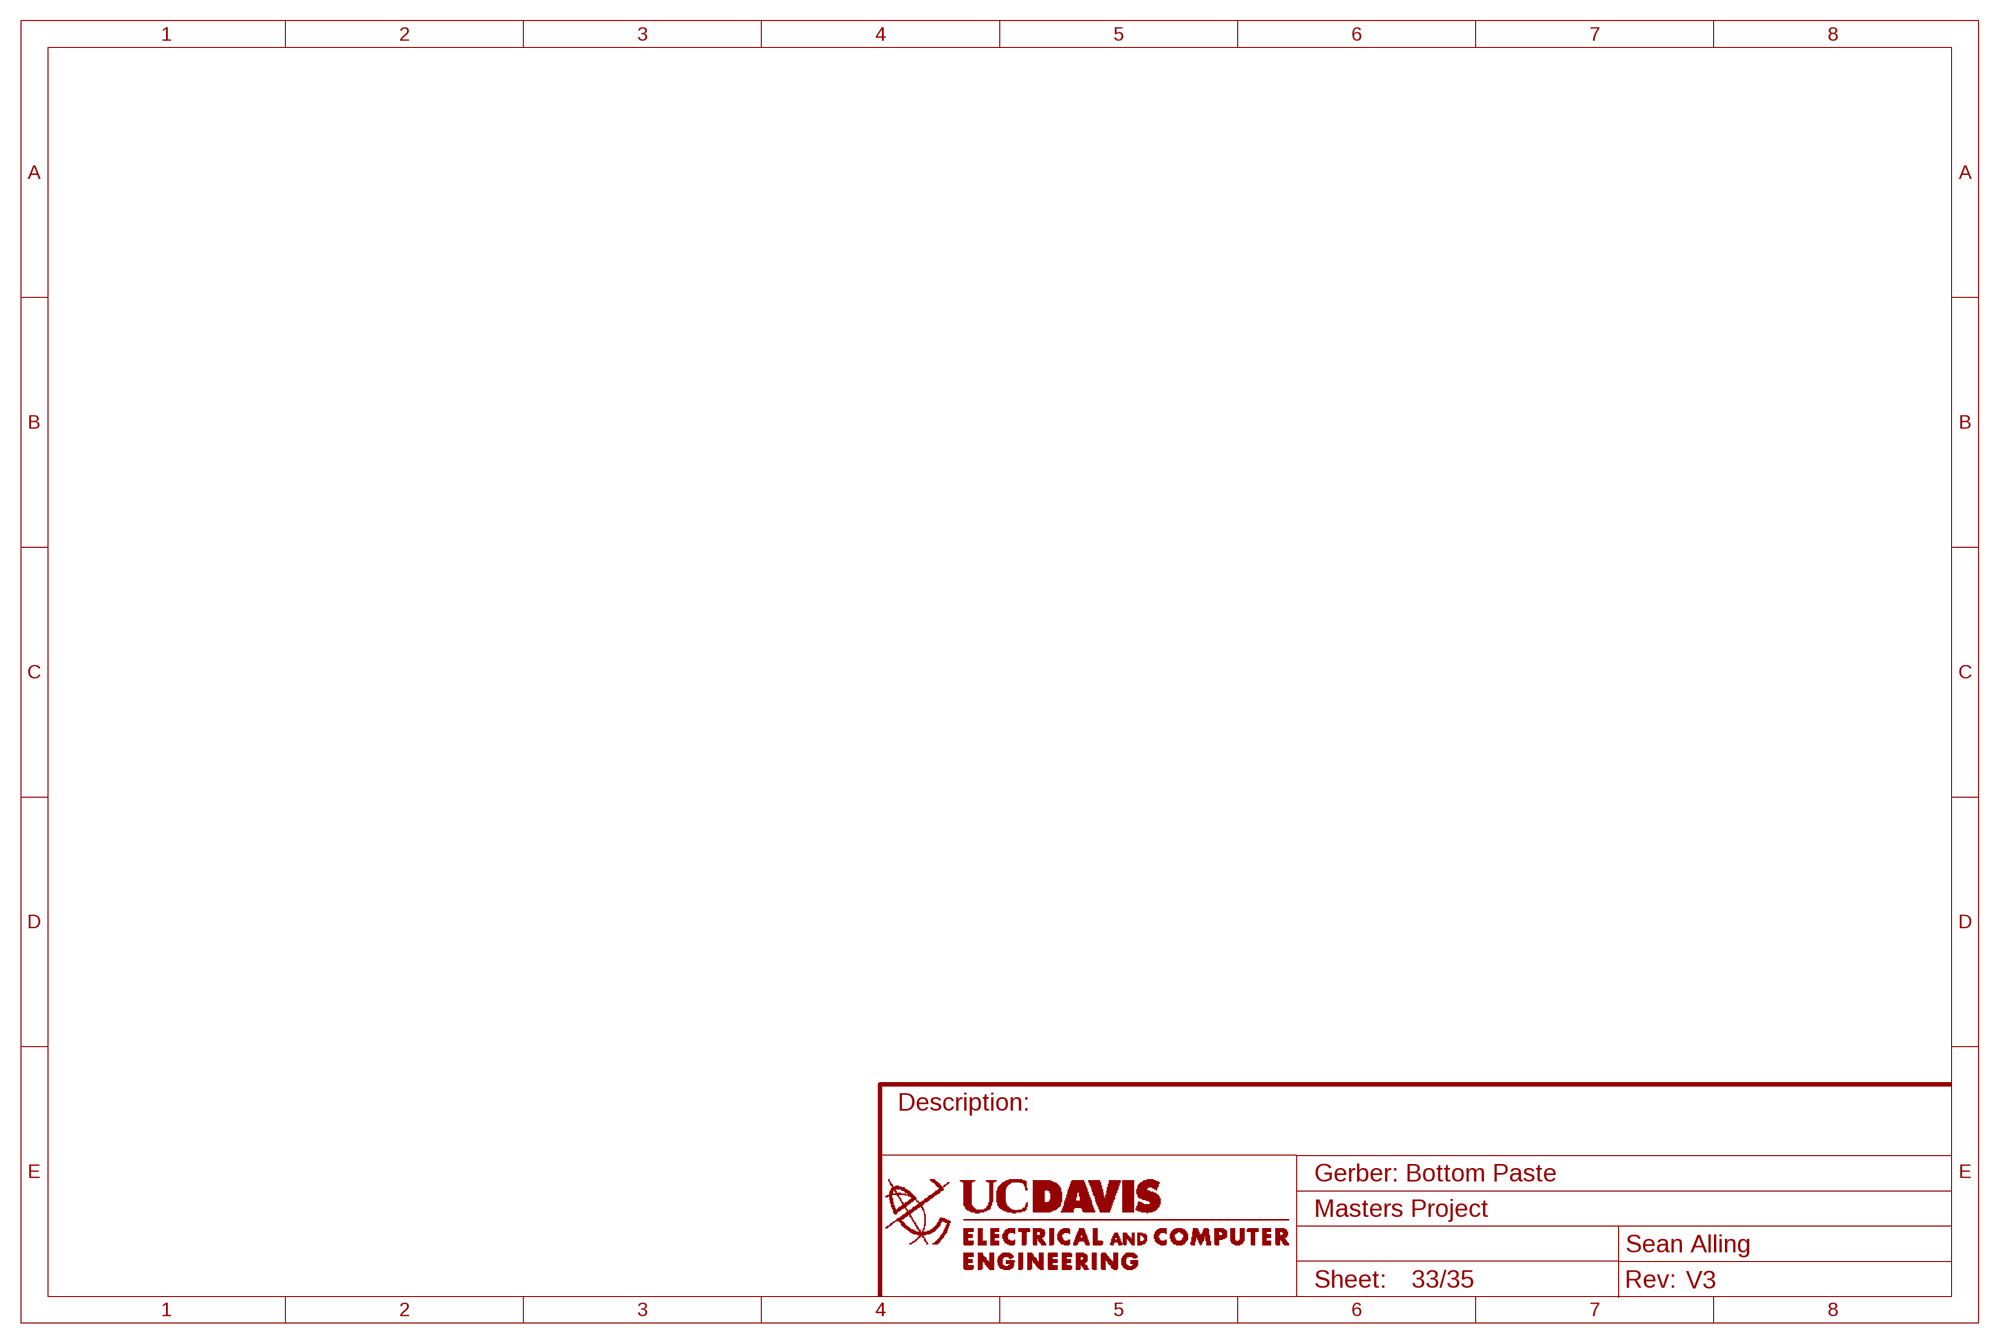
[diagram p32: schematic, sheet 33]
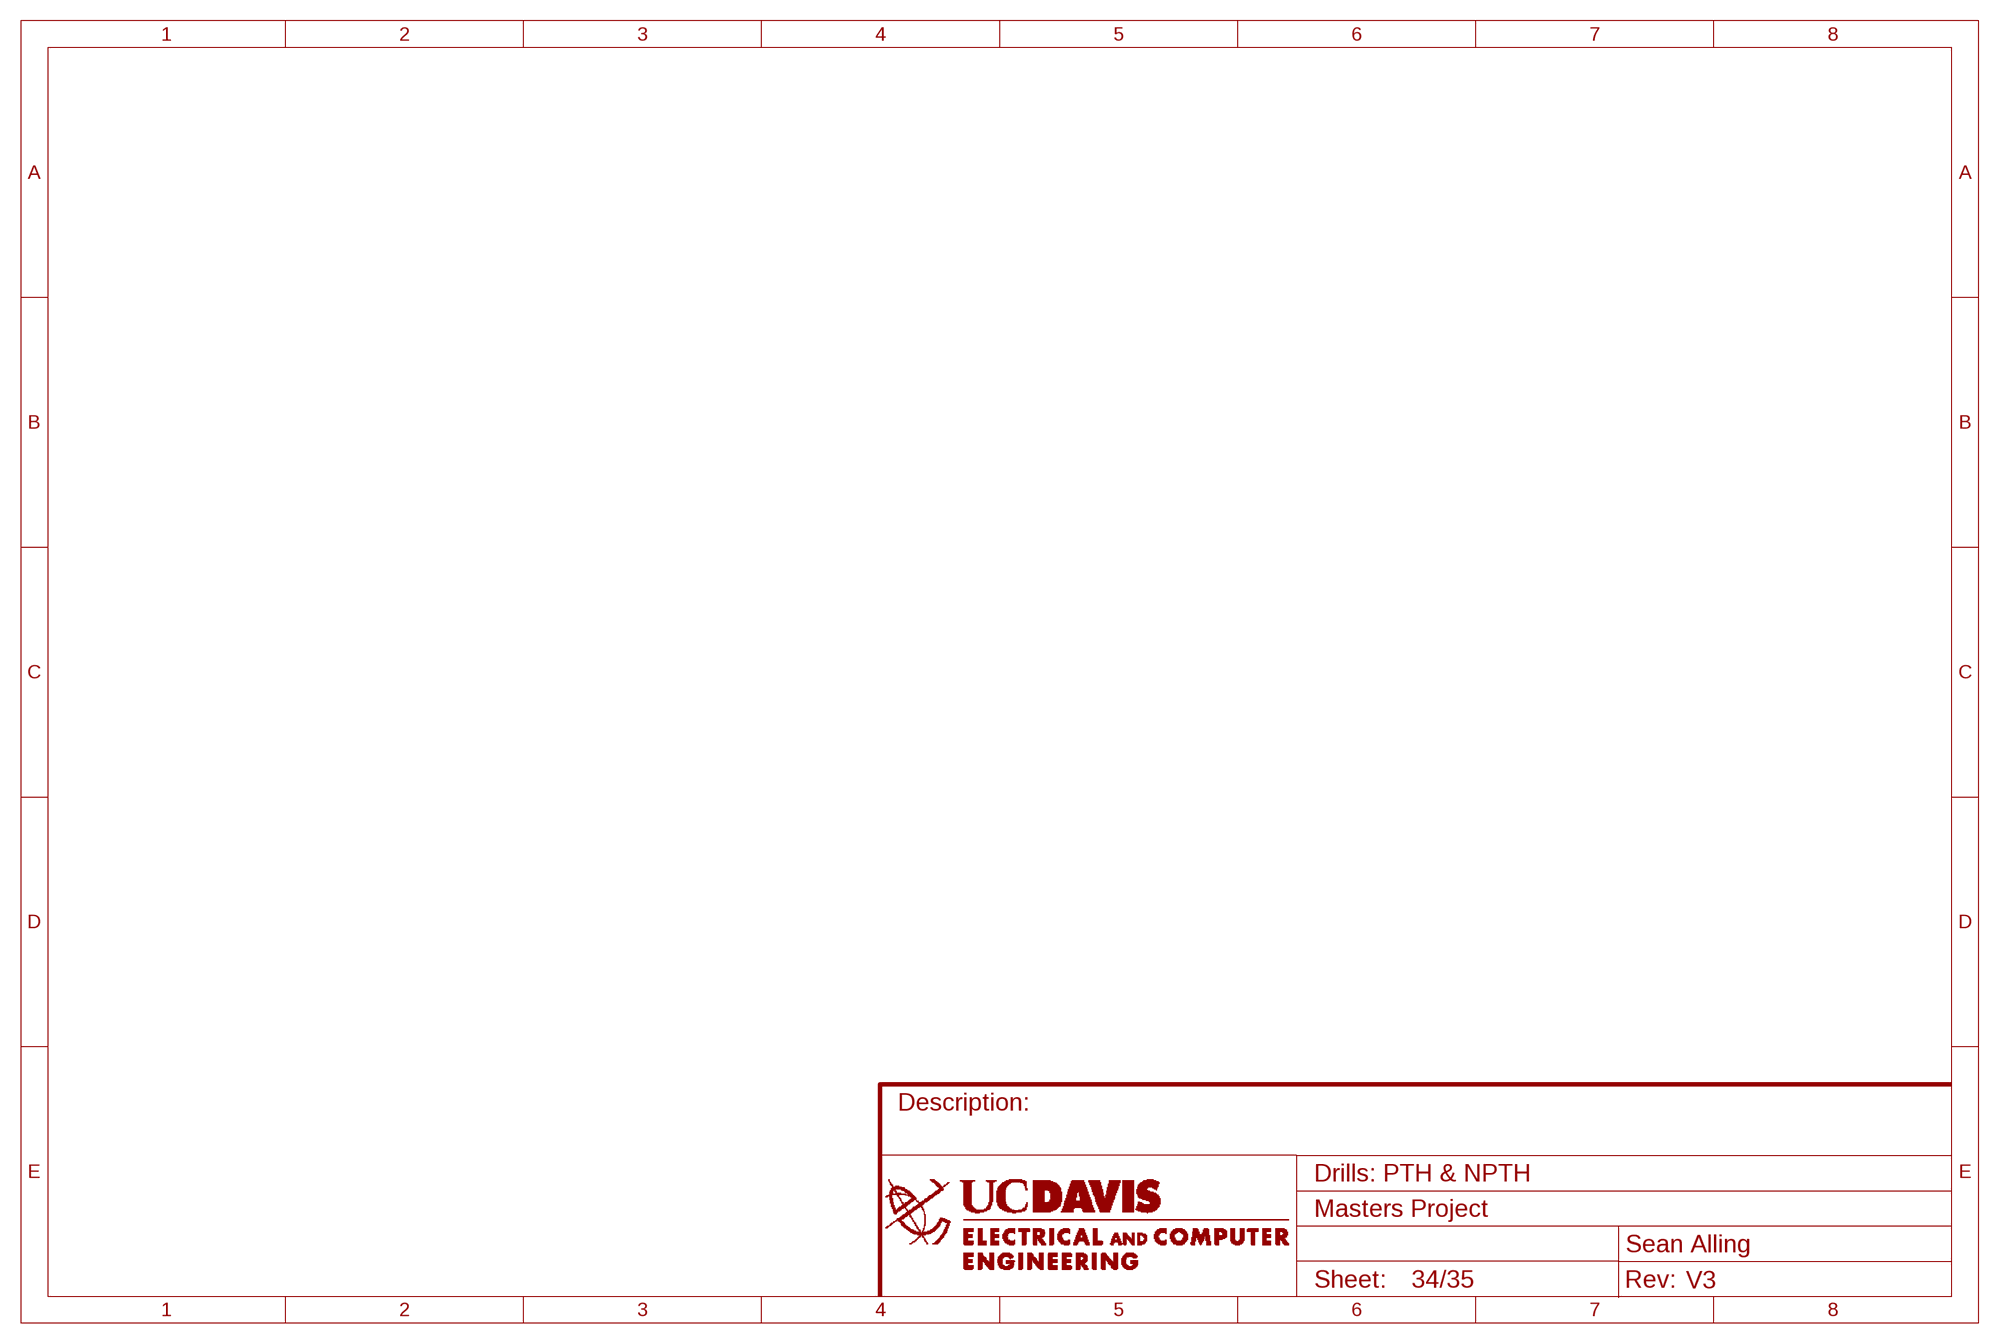
[diagram p33: schematic, sheet 34]
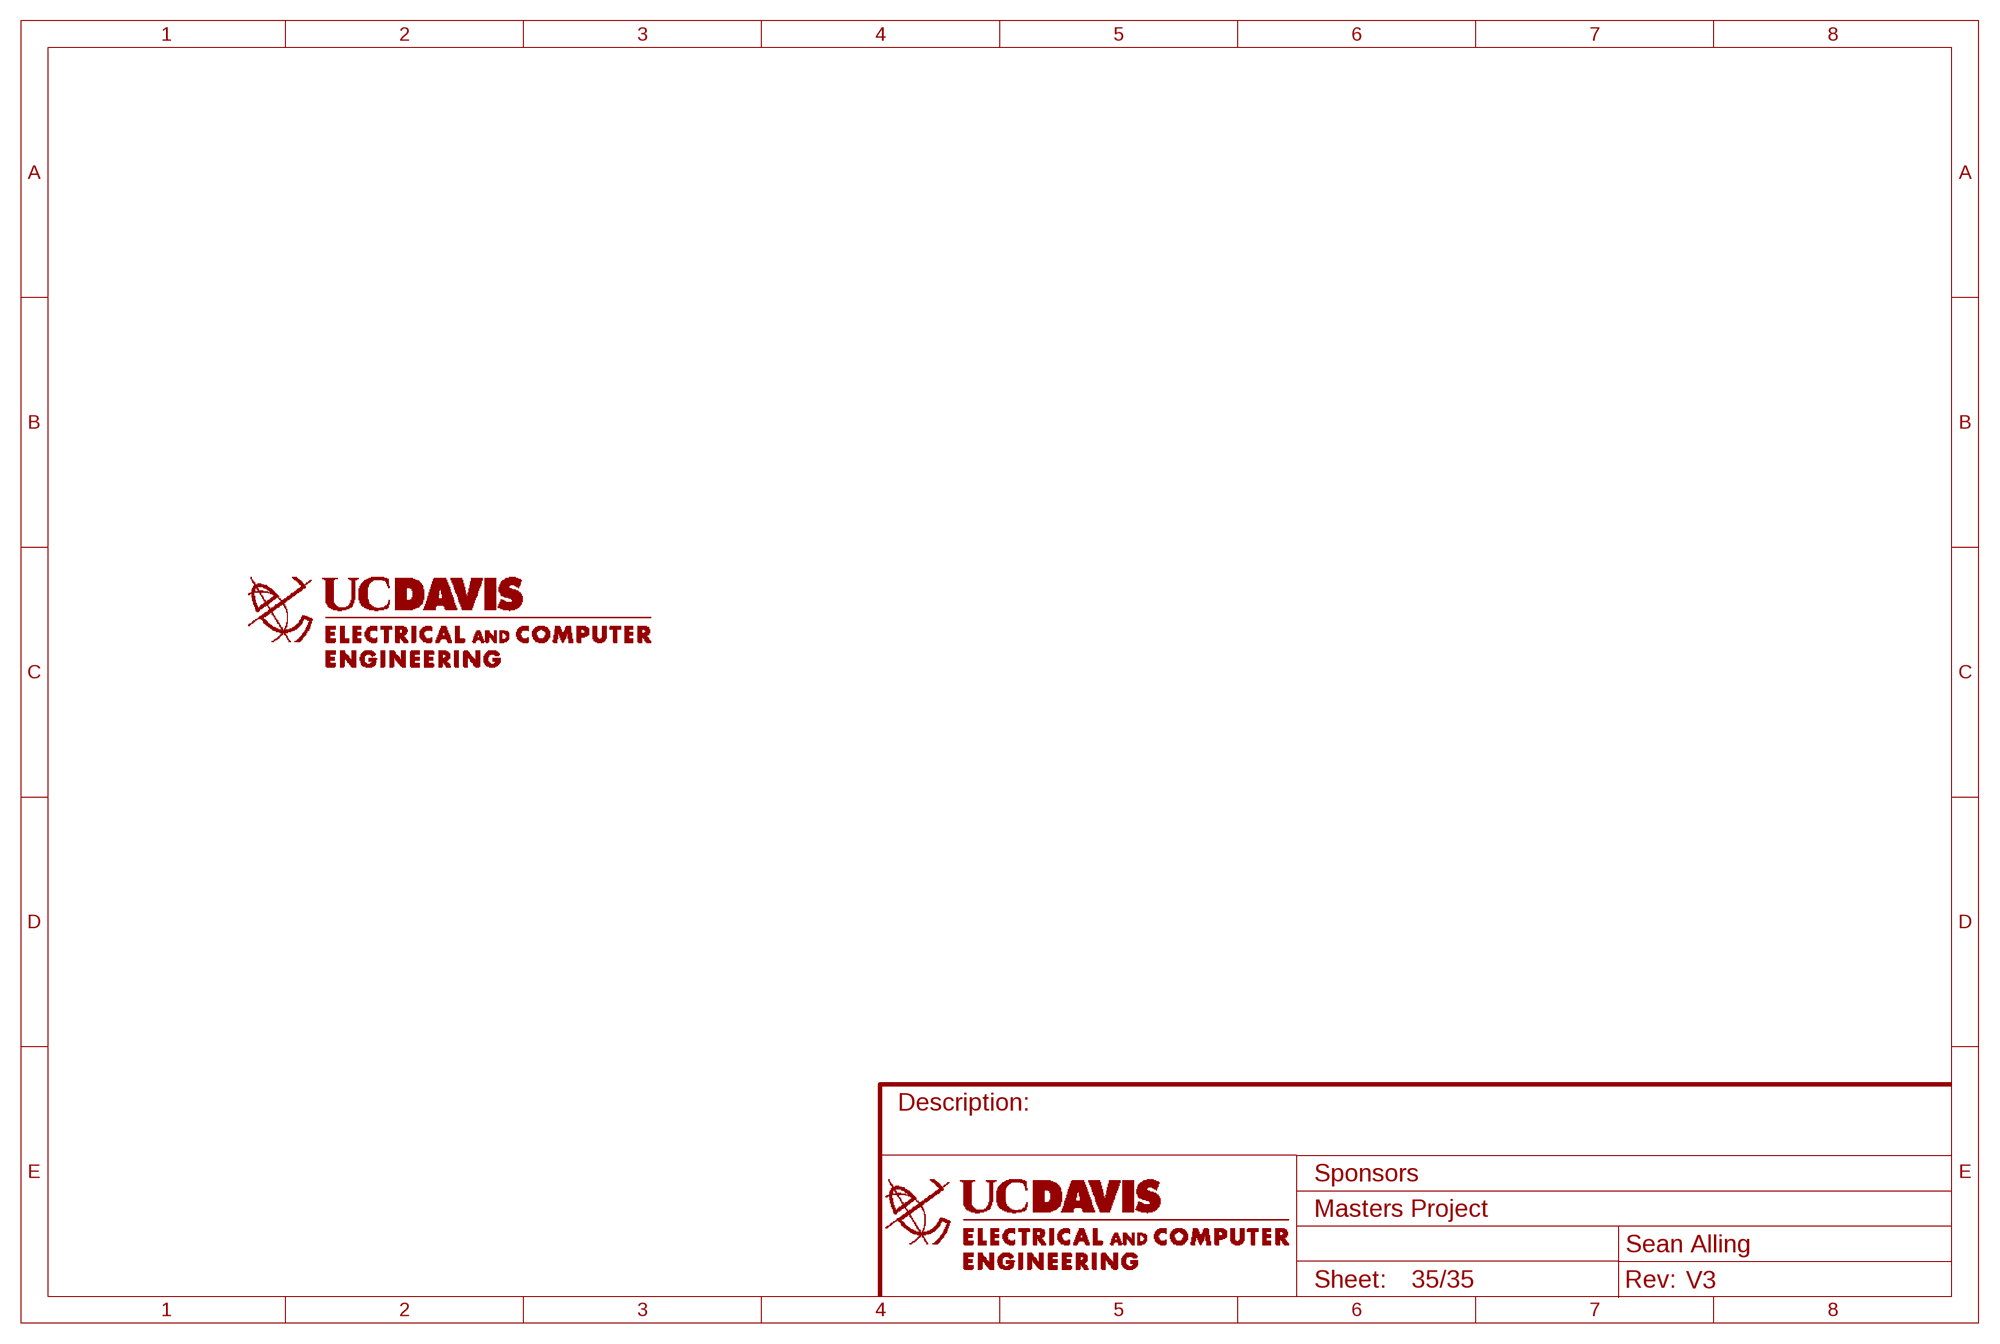
[diagram p34: schematic, sheet 35]

(export (version "E")
  (design (tool "Eeschema 10.0.6"))
  (components
    (comp (ref "C3")
      (value "4.7uF")
      (footprint "eagle-import:C0603")
      (fields (field (name "PARTNO") "CL21A475KBQNNNE"))
      (libsource (lib "eagle-import") (part "C-USC0603"))
    )
    (comp (ref "C4")
      (value "4.7uF")
      (footprint "eagle-import:C0603")
      (fields (field (name "PARTNO") "CL21A475KBQNNNE"))
      (libsource (lib "eagle-import") (part "C-USC0603"))
    )
    (comp (ref "D2")
      (value "250mA/100V")
      (footprint "eagle-import:SOD-323")
      (libsource (lib "eagle-import") (part "DIODE-BAS16J"))
    )
    (comp (ref "J1")
      (value "JST_2MM_MALE")
      (footprint "eagle-import:JST-2-SMD")
      (fields (field (name "PARTNO") "S2B-PH-SM4-TB(LF)(SN)"))
      (libsource (lib "eagle-import") (part "JST_2MM_MALE"))
    )
    (comp (ref "LED11")
      (value "RED")
      (footprint "eagle-import:CHIPLED_0603")
      (fields (field (name "PARTNO") "LG R971-KN-1"))
      (libsource (lib "eagle-import") (part "LEDCHIPLED_0603"))
    )
    (comp (ref "R16")
      (value "2K")
      (footprint "eagle-import:R0603")
      (fields (field (name "PARTNO") "RC0805FR-072KL"))
      (libsource (lib "eagle-import") (part "R-US_R0603"))
    )
    (comp (ref "R17")
      (value "330R")
      (footprint "eagle-import:R0603")
      (fields (field (name "PARTNO") "RMCF0805JT330R"))
      (libsource (lib "eagle-import") (part "R-US_R0603"))
    )
    (comp (ref "TP1")
      (value "TPB1,27")
      (footprint "eagle-import:B1,27")
      (fields (field (name "TP_SIGNAL_NAME") "+BAT"))
      (libsource (lib "eagle-import") (part "TPB1,27"))
    )
    (comp (ref "TP2")
      (value "TPB1,27")
      (footprint "eagle-import:B1,27")
      (fields (field (name "TP_SIGNAL_NAME") "GND"))
      (libsource (lib "eagle-import") (part "TPB1,27"))
    )
    (comp (ref "TP3")
      (value "TPB1,27")
      (footprint "eagle-import:B1,27")
      (fields (field (name "TP_SIGNAL_NAME") "VCC_USB"))
      (libsource (lib "eagle-import") (part "TPB1,27"))
    )
    (comp (ref "TP11")
      (value "TPB1,27")
      (footprint "eagle-import:B1,27")
      (fields (field (name "TP_SIGNAL_NAME") "GND"))
      (libsource (lib "eagle-import") (part "TPB1,27"))
    )
    (comp (ref "TP25")
      (value "TPB1,27")
      (footprint "eagle-import:B1,27")
      (fields (field (name "TP_SIGNAL_NAME") "CHARGE_STATUS"))
      (libsource (lib "eagle-import") (part "TPB1,27"))
    )
    (comp (ref "U2")
      (value "MCP73831")
      (footprint "eagle-import:SOT23-5L")
      (fields (field (name "PARTNO") "MCP73831T-2ATI/OT"))
      (libsource (lib "eagle-import") (part "MCP73831"))
    )
    (comp (ref "X1")
      (value "MINI-USB-32005-201")
      (footprint "eagle-import:32005-201")
      (fields (field (name "PARTNO") "10033526-N3212LF"))
      (libsource (lib "eagle-import") (part "MINI-USB-32005-201"))
    )
    (comp (ref "C37")
      (value "0.1uF")
      (footprint "eagle-import:C0603")
      (fields (field (name "PARTNO") "08055C104KAT2A"))
      (libsource (lib "eagle-import") (part "C-USC0603"))
    )
    (comp (ref "C38")
      (value "0.1uF")
      (footprint "eagle-import:C0603")
      (fields (field (name "PARTNO") "08055C104KAT2A"))
      (libsource (lib "eagle-import") (part "C-USC0603"))
    )
    (comp (ref "C42")
      (value "0.1uF")
      (footprint "eagle-import:C0603")
      (fields (field (name "PARTNO") "08055C104KAT2A"))
      (libsource (lib "eagle-import") (part "C-USC0603"))
    )
    (comp (ref "C43")
      (value "0.1uF")
      (footprint "eagle-import:C0603")
      (fields (field (name "PARTNO") "08055C104KAT2A"))
      (libsource (lib "eagle-import") (part "C-USC0603"))
    )
    (comp (ref "C46")
      (value "0.1uF")
      (footprint "eagle-import:C0603")
      (fields (field (name "PARTNO") "08055C104KAT2A"))
      (libsource (lib "eagle-import") (part "C-USC0603"))
    )
    (comp (ref "C47")
      (value "0.1uF")
      (footprint "eagle-import:C0603")
      (fields (field (name "PARTNO") "08055C104KAT2A"))
      (libsource (lib "eagle-import") (part "C-USC0603"))
    )
    (comp (ref "C50")
      (value "0.1uF")
      (footprint "eagle-import:C0603")
      (fields (field (name "PARTNO") "08055C104KAT2A"))
      (libsource (lib "eagle-import") (part "C-USC0603"))
    )
    (comp (ref "C51")
      (value "0.1uF")
      (footprint "eagle-import:C0603")
      (fields (field (name "PARTNO") "08055C104KAT2A"))
      (libsource (lib "eagle-import") (part "C-USC0603"))
    )
    (comp (ref "C54")
      (value "0.1uF")
      (footprint "eagle-import:C0603")
      (fields (field (name "PARTNO") "08055C104KAT2A"))
      (libsource (lib "eagle-import") (part "C-USC0603"))
    )
    (comp (ref "C55")
      (value "0.1uF")
      (footprint "eagle-import:C0603")
      (fields (field (name "PARTNO") "08055C104KAT2A"))
      (libsource (lib "eagle-import") (part "C-USC0603"))
    )
    (comp (ref "JP1")
      (value "2X5_HEADER1.27MM")
      (footprint "eagle-import:CORTEX_DEBUG_10PIN")
      (libsource (lib "eagle-import") (part "2X5_HEADER1.27MM"))
    )
    (comp (ref "JP4")
      (value "2X5_HEADER1.27MM")
      (footprint "eagle-import:CORTEX_DEBUG_10PIN")
      (libsource (lib "eagle-import") (part "2X5_HEADER1.27MM"))
    )
    (comp (ref "R30")
      (value "5k")
      (footprint "eagle-import:R0603")
      (fields (field (name "PARTNO") "RC0805FR-075K1L"))
      (libsource (lib "eagle-import") (part "R-US_R0603"))
    )
    (comp (ref "R31")
      (value "5k")
      (footprint "eagle-import:R0603")
      (fields (field (name "PARTNO") "RC0805FR-075K1L"))
      (libsource (lib "eagle-import") (part "R-US_R0603"))
    )
    (comp (ref "R32")
      (value "5k")
      (footprint "eagle-import:R0603")
      (fields (field (name "PARTNO") "RC0805FR-075K1L"))
      (libsource (lib "eagle-import") (part "R-US_R0603"))
    )
    (comp (ref "R35")
      (value "2k")
      (footprint "eagle-import:R0603")
      (fields (field (name "PARTNO") "RC0805FR-072KL"))
      (libsource (lib "eagle-import") (part "R-US_R0603"))
    )
    (comp (ref "U1")
      (value "LCMXO2-640HC-4TG100C-NEW")
      (footprint "eagle-import:QFP50P1600X1600X160-100N")
      (fields
        (field (name "MANUFACTURER") "Lattice Semiconductor")
        (field (name "MOUSER_PART_NUMBER") "842-XO2640HC4TG100C")
        (field (name "MPN") "LCMXO2-640HC-4TG100C")
      )
      (libsource (lib "eagle-import") (part "LCMXO2-640HC-4TG100C-NEW"))
    )
    (comp (ref "C68")
      (value "11mF")
      (footprint "eagle-import:C1210K")
      (fields (field (name "PACKAGE") "1210"))
      (libsource (lib "eagle-import") (part "rcl_334_C-USC1210K"))
    )
    (comp (ref "Q9")
      (value "ABS07-LR")
      (footprint "eagle-import:2-SMD")
      (libsource (lib "eagle-import") (part "ABS07-LR"))
    )
    (comp (ref "R3")
      (value "1K")
      (footprint "eagle-import:R0603")
      (libsource (lib "eagle-import") (part "rcl_334_R-US_R0603"))
    )
    (comp (ref "TP40")
      (value "TPB1,27")
      (footprint "eagle-import:B1,27")
      (fields (field (name "TP_SIGNAL_NAME") "!RTC_INT1"))
      (libsource (lib "eagle-import") (part "TPB1,27"))
    )
    (comp (ref "TP41")
      (value "TPB1,27")
      (footprint "eagle-import:B1,27")
      (fields (field (name "TP_SIGNAL_NAME") "RTC_CLKOUT"))
      (libsource (lib "eagle-import") (part "TPB1,27"))
    )
    (comp (ref "TP42")
      (value "TPB1,27")
      (footprint "eagle-import:B1,27")
      (fields (field (name "TP_SIGNAL_NAME") "!RTC_INT2"))
      (libsource (lib "eagle-import") (part "TPB1,27"))
    )
    (comp (ref "U16")
      (value "PCF8523")
      (footprint "eagle-import:TSSOP14")
      (libsource (lib "eagle-import") (part "PCF8523"))
    )
    (comp (ref "LED12")
      (value "GREEN")
      (footprint "eagle-import:CHIPLED_0603")
      (fields (field (name "PARTNO") "LG R971-KN-1"))
      (libsource (lib "eagle-import") (part "LEDCHIPLED_0603"))
    )
    (comp (ref "R24")
      (value "10K")
      (footprint "eagle-import:R0603")
      (fields (field (name "PARTNO") "RMCF0805JT10K0"))
      (libsource (lib "eagle-import") (part "R-US_R0603"))
    )
    (comp (ref "R25")
      (value "10K")
      (footprint "eagle-import:R0603")
      (fields (field (name "PARTNO") "RMCF0805JT10K0"))
      (libsource (lib "eagle-import") (part "R-US_R0603"))
    )
    (comp (ref "R27")
      (value "1K")
      (footprint "eagle-import:R0603")
      (fields (field (name "PARTNO") "RC0805JR-071KL"))
      (libsource (lib "eagle-import") (part "R-US_R0603"))
    )
    (comp (ref "TP22")
      (value "TPB1,27")
      (footprint "eagle-import:B1,27")
      (fields (field (name "TP_SIGNAL_NAME") "UART_TX_XBEE"))
      (libsource (lib "eagle-import") (part "TPB1,27"))
    )
    (comp (ref "TP23")
      (value "TPB1,27")
      (footprint "eagle-import:B1,27")
      (fields (field (name "TP_SIGNAL_NAME") "UART_RX_XBEE"))
      (libsource (lib "eagle-import") (part "TPB1,27"))
    )
    (comp (ref "TP24")
      (value "TPB1,27")
      (footprint "eagle-import:B1,27")
      (fields (field (name "TP_SIGNAL_NAME") "SPI_CLK"))
      (libsource (lib "eagle-import") (part "TPB1,27"))
    )
    (comp (ref "TP26")
      (value "TPB1,27")
      (footprint "eagle-import:B1,27")
      (fields (field (name "TP_SIGNAL_NAME") "SPI_MOSI"))
      (libsource (lib "eagle-import") (part "TPB1,27"))
    )
    (comp (ref "TP27")
      (value "TPB1,27")
      (footprint "eagle-import:B1,27")
      (fields (field (name "TP_SIGNAL_NAME") "DISPLAY_D/!C"))
      (libsource (lib "eagle-import") (part "TPB1,27"))
    )
    (comp (ref "TP28")
      (value "TPB1,27")
      (footprint "eagle-import:B1,27")
      (fields (field (name "TP_SIGNAL_NAME") "SPI_CS_DISPLAY"))
      (libsource (lib "eagle-import") (part "TPB1,27"))
    )
    (comp (ref "TP29")
      (value "TPB1,27")
      (footprint "eagle-import:B1,27")
      (fields (field (name "TP_SIGNAL_NAME") "MCU_SCL"))
      (libsource (lib "eagle-import") (part "TPB1,27"))
    )
    (comp (ref "TP30")
      (value "TPB1,27")
      (footprint "eagle-import:B1,27")
      (fields (field (name "TP_SIGNAL_NAME") "MCU_SDA"))
      (libsource (lib "eagle-import") (part "TPB1,27"))
    )
    (comp (ref "U12")
      (value "MSP432P401R")
      (footprint "eagle-import:LQFP100")
      (fields (field (name "PARTNO") "MSP432P401RIPZR"))
      (libsource (lib "eagle-import") (part "MSP432P401R"))
    )
    (comp (ref "C57")
      (value "47uF")
      (footprint "eagle-import:C0603")
      (fields (field (name "PARTNO") "GRM21BR61A476ME15L"))
      (libsource (lib "eagle-import") (part "C-USC0603"))
    )
    (comp (ref "JP2")
      (value "1X3_HEADER")
      (footprint "eagle-import:1X3_FEMALE_HEADER_THROUGH_HOLE")
      (fields (field (name "PARTNO") "PRPC040SAAN-RC"))
      (libsource (lib "eagle-import") (part "1X3_HEADER"))
    )
    (comp (ref "JP26")
      (value "XBEE-1B1")
      (footprint "eagle-import:XBEE-1")
      (fields (field (name "PARTNO") "NPPN101BFCN-RC"))
      (libsource (lib "eagle-import") (part "XBEE-1B1"))
    )
    (comp (ref "LED14")
      (value "GREEN")
      (footprint "eagle-import:CHIPLED_0603")
      (fields (field (name "PARTNO") "LG R971-KN-1"))
      (libsource (lib "eagle-import") (part "LEDCHIPLED_0603"))
    )
    (comp (ref "LED15")
      (value "GREEN")
      (footprint "eagle-import:CHIPLED_0603")
      (fields (field (name "PARTNO") "LG R971-KN-1"))
      (libsource (lib "eagle-import") (part "LEDCHIPLED_0603"))
    )
    (comp (ref "LED16")
      (value "GREEN")
      (footprint "eagle-import:SML0805")
      (fields (field (name "PARTNO") "LG R971-KN-1"))
      (libsource (lib "eagle-import") (part "LEDSML0805"))
    )
    (comp (ref "LED17")
      (value "GREEN")
      (footprint "eagle-import:SML0805")
      (fields (field (name "PARTNO") "LG R971-KN-1"))
      (libsource (lib "eagle-import") (part "LEDSML0805"))
    )
    (comp (ref "LED18")
      (value "GREEN")
      (footprint "eagle-import:CHIPLED_0603")
      (fields (field (name "PARTNO") "LG R971-KN-1"))
      (libsource (lib "eagle-import") (part "LEDCHIPLED_0603"))
    )
    (comp (ref "R37")
      (value "1K")
      (footprint "eagle-import:R0603")
      (fields (field (name "PARTNO") "RC0805JR-071KL"))
      (libsource (lib "eagle-import") (part "R-US_R0603"))
    )
    (comp (ref "R38")
      (value "1K")
      (footprint "eagle-import:R0603")
      (fields (field (name "PARTNO") "RC0805JR-071KL"))
      (libsource (lib "eagle-import") (part "R-US_R0603"))
    )
    (comp (ref "R39")
      (value "1K")
      (footprint "eagle-import:R0603")
      (fields (field (name "PARTNO") "RC0805JR-071KL"))
      (libsource (lib "eagle-import") (part "R-US_R0603"))
    )
    (comp (ref "R40")
      (value "1K")
      (footprint "eagle-import:R0603")
      (fields (field (name "PARTNO") "RC0805JR-071KL"))
      (libsource (lib "eagle-import") (part "R-US_R0603"))
    )
    (comp (ref "R41")
      (value "1K")
      (footprint "eagle-import:R0603")
      (fields (field (name "PARTNO") "RC0805JR-071KL"))
      (libsource (lib "eagle-import") (part "R-US_R0603"))
    )
    (comp (ref "C20")
      (value "100nF")
      (footprint "eagle-import:C0603")
      (fields (field (name "PARTNO") "CC0603ZRY5V9BB104"))
      (libsource (lib "eagle-import") (part "rcl_334_C-USC0603"))
    )
    (comp (ref "U11")
      (value "OPT3001")
      (footprint "eagle-import:USON-6")
      (fields (field (name "PARTNO") "OPT3001DNPT"))
      (libsource (lib "eagle-import") (part "OPT3001"))
    )
    (comp (ref "FD1")
      (value "FIDUCIAL1X2")
      (footprint "eagle-import:FIDUCIAL-1X2")
      (libsource (lib "eagle-import") (part "FIDUCIAL1X2"))
    )
    (comp (ref "FD2")
      (value "FIDUCIAL1X2")
      (footprint "eagle-import:FIDUCIAL-1X2")
      (libsource (lib "eagle-import") (part "FIDUCIAL1X2"))
    )
    (comp (ref "FD3")
      (value "FIDUCIAL1X2")
      (footprint "eagle-import:FIDUCIAL-1X2")
      (libsource (lib "eagle-import") (part "FIDUCIAL1X2"))
    )
    (comp (ref "FD4")
      (value "FIDUCIAL1X2")
      (footprint "eagle-import:FIDUCIAL-1X2")
      (libsource (lib "eagle-import") (part "FIDUCIAL1X2"))
    )
    (comp (ref "FD5")
      (value "FIDUCIAL1X2")
      (footprint "eagle-import:FIDUCIAL-1X2")
      (libsource (lib "eagle-import") (part "FIDUCIAL1X2"))
    )
    (comp (ref "FD6")
      (value "FIDUCIAL1X2")
      (footprint "eagle-import:FIDUCIAL-1X2")
      (libsource (lib "eagle-import") (part "FIDUCIAL1X2"))
    )
    (comp (ref "FD7")
      (value "FIDUCIAL1X2")
      (footprint "eagle-import:FIDUCIAL-1X2")
      (libsource (lib "eagle-import") (part "FIDUCIAL1X2"))
    )
    (comp (ref "FD8")
      (value "FIDUCIAL1X2")
      (footprint "eagle-import:FIDUCIAL-1X2")
      (libsource (lib "eagle-import") (part "FIDUCIAL1X2"))
    )
    (comp (ref "H1")
      (value "STAND-OFF")
      (footprint "eagle-import:STAND-OFF")
      (libsource (lib "eagle-import") (part "STAND-OFF"))
    )
    (comp (ref "H2")
      (value "STAND-OFF")
      (footprint "eagle-import:STAND-OFF")
      (libsource (lib "eagle-import") (part "STAND-OFF"))
    )
    (comp (ref "H3")
      (value "STAND-OFF")
      (footprint "eagle-import:STAND-OFF")
      (libsource (lib "eagle-import") (part "STAND-OFF"))
    )
    (comp (ref "H4")
      (value "STAND-OFF")
      (footprint "eagle-import:STAND-OFF")
      (libsource (lib "eagle-import") (part "STAND-OFF"))
    )
    (comp (ref "JP3")
      (value "2X5_HEADER1.27MM")
      (footprint "eagle-import:CORTEX_DEBUG_10PIN")
      (libsource (lib "eagle-import") (part "2X5_HEADER1.27MM"))
    )
    (comp (ref "TP31")
      (value "TPB1,27")
      (footprint "eagle-import:B1,27")
      (fields (field (name "TP_SIGNAL_NAME") "EINK_!RST"))
      (libsource (lib "eagle-import") (part "TPB1,27"))
    )
    (comp (ref "TP32")
      (value "TPB1,27")
      (footprint "eagle-import:B1,27")
      (fields (field (name "TP_SIGNAL_NAME") "EINK_BUSY"))
      (libsource (lib "eagle-import") (part "TPB1,27"))
    )
    (comp (ref "C5")
      (value "1uF")
      (footprint "eagle-import:C0603")
      (fields (field (name "PARTNO") "CC0805ZKY5V9BB105"))
      (libsource (lib "eagle-import") (part "C-USC0603"))
    )
    (comp (ref "C6")
      (value "1uF")
      (footprint "eagle-import:C0603")
      (fields (field (name "PARTNO") "CC0805ZKY5V9BB105"))
      (libsource (lib "eagle-import") (part "C-USC0603"))
    )
    (comp (ref "C7")
      (value "1uF")
      (footprint "eagle-import:C0603")
      (fields (field (name "PARTNO") "CC0805ZKY5V9BB105"))
      (libsource (lib "eagle-import") (part "C-USC0603"))
    )
    (comp (ref "C8")
      (value "1uF")
      (footprint "eagle-import:C0603")
      (fields (field (name "PARTNO") "CC0805ZKY5V9BB105"))
      (libsource (lib "eagle-import") (part "C-USC0603"))
    )
    (comp (ref "C9")
      (value "1uF")
      (footprint "eagle-import:C0603")
      (fields (field (name "PARTNO") "CC0805ZKY5V9BB105"))
      (libsource (lib "eagle-import") (part "C-USC0603"))
    )
    (comp (ref "C10")
      (value "1uF")
      (footprint "eagle-import:C0603")
      (fields (field (name "PARTNO") "CC0805ZKY5V9BB105"))
      (libsource (lib "eagle-import") (part "C-USC0603"))
    )
    (comp (ref "C11")
      (value "1uF")
      (footprint "eagle-import:C0603")
      (fields (field (name "PARTNO") "CC0805ZKY5V9BB105"))
      (libsource (lib "eagle-import") (part "C-USC0603"))
    )
    (comp (ref "C12")
      (value "1uF")
      (footprint "eagle-import:C0603")
      (fields (field (name "PARTNO") "CC0805ZKY5V9BB105"))
      (libsource (lib "eagle-import") (part "C-USC0603"))
    )
    (comp (ref "C13")
      (value "1uF")
      (footprint "eagle-import:C0603")
      (fields (field (name "PARTNO") "CC0805ZKY5V9BB105"))
      (libsource (lib "eagle-import") (part "C-USC0603"))
    )
    (comp (ref "C14")
      (value "1uF")
      (footprint "eagle-import:C0603")
      (fields (field (name "PARTNO") "CC0805ZKY5V9BB105"))
      (libsource (lib "eagle-import") (part "C-USC0603"))
    )
    (comp (ref "C15")
      (value "1uF")
      (footprint "eagle-import:C0603")
      (fields (field (name "PARTNO") "CC0805ZKY5V9BB105"))
      (libsource (lib "eagle-import") (part "C-USC0603"))
    )
    (comp (ref "C16")
      (value "1uF")
      (footprint "eagle-import:C0603")
      (fields (field (name "PARTNO") "CC0805ZKY5V9BB105"))
      (libsource (lib "eagle-import") (part "C-USC0603"))
    )
    (comp (ref "C17")
      (value "1uF")
      (footprint "eagle-import:C0603")
      (fields (field (name "PARTNO") "CC0805ZKY5V9BB105"))
      (libsource (lib "eagle-import") (part "C-USC0603"))
    )
    (comp (ref "C18")
      (value "1uF")
      (footprint "eagle-import:C0603")
      (fields (field (name "PARTNO") "CC0805ZKY5V9BB105"))
      (libsource (lib "eagle-import") (part "C-USC0603"))
    )
    (comp (ref "TP4")
      (value "TPB1,27")
      (footprint "eagle-import:B1,27")
      (fields (field (name "TP_SIGNAL_NAME") "VCC_HDC1080"))
      (libsource (lib "eagle-import") (part "TPB1,27"))
    )
    (comp (ref "TP5")
      (value "TPB1,27")
      (footprint "eagle-import:B1,27")
      (fields (field (name "TP_SIGNAL_NAME") "VCC_OPT3001"))
      (libsource (lib "eagle-import") (part "TPB1,27"))
    )
    (comp (ref "TP6")
      (value "TPB1,27")
      (footprint "eagle-import:B1,27")
      (fields (field (name "TP_SIGNAL_NAME") "VCC_FPGA"))
      (libsource (lib "eagle-import") (part "TPB1,27"))
    )
    (comp (ref "TP7")
      (value "TPB1,27")
      (footprint "eagle-import:B1,27")
      (fields (field (name "TP_SIGNAL_NAME") "VCC_XBEE"))
      (libsource (lib "eagle-import") (part "TPB1,27"))
    )
    (comp (ref "TP8")
      (value "TPB1,27")
      (footprint "eagle-import:B1,27")
      (fields (field (name "TP_SIGNAL_NAME") "VCC_MEMORY"))
      (libsource (lib "eagle-import") (part "TPB1,27"))
    )
    (comp (ref "TP9")
      (value "TPB1,27")
      (footprint "eagle-import:B1,27")
      (fields (field (name "TP_SIGNAL_NAME") "VCC_DISPLAY"))
      (libsource (lib "eagle-import") (part "TPB1,27"))
    )
    (comp (ref "TP10")
      (value "TPB1,27")
      (footprint "eagle-import:B1,27")
      (fields (field (name "TP_SIGNAL_NAME") "VCC_MCU"))
      (libsource (lib "eagle-import") (part "TPB1,27"))
    )
    (comp (ref "TP12")
      (value "TPB1,27")
      (footprint "eagle-import:B1,27")
      (fields (field (name "TP_SIGNAL_NAME") "GND"))
      (libsource (lib "eagle-import") (part "TPB1,27"))
    )
    (comp (ref "TP13")
      (value "TPB1,27")
      (footprint "eagle-import:B1,27")
      (fields (field (name "TP_SIGNAL_NAME") "GND"))
      (libsource (lib "eagle-import") (part "TPB1,27"))
    )
    (comp (ref "TP14")
      (value "TPB1,27")
      (footprint "eagle-import:B1,27")
      (fields (field (name "TP_SIGNAL_NAME") "GND"))
      (libsource (lib "eagle-import") (part "TPB1,27"))
    )
    (comp (ref "TP15")
      (value "TPB1,27")
      (footprint "eagle-import:B1,27")
      (fields (field (name "TP_SIGNAL_NAME") "GND"))
      (libsource (lib "eagle-import") (part "TPB1,27"))
    )
    (comp (ref "TP16")
      (value "TPB1,27")
      (footprint "eagle-import:B1,27")
      (fields (field (name "TP_SIGNAL_NAME") "GND"))
      (libsource (lib "eagle-import") (part "TPB1,27"))
    )
    (comp (ref "TP17")
      (value "TPB1,27")
      (footprint "eagle-import:B1,27")
      (fields (field (name "TP_SIGNAL_NAME") "GND"))
      (libsource (lib "eagle-import") (part "TPB1,27"))
    )
    (comp (ref "TP18")
      (value "TPB1,27")
      (footprint "eagle-import:B1,27")
      (fields (field (name "TP_SIGNAL_NAME") "GND"))
      (libsource (lib "eagle-import") (part "TPB1,27"))
    )
    (comp (ref "U3")
      (value "STLQ015M33R")
      (footprint "eagle-import:SOT23-5L")
      (libsource (lib "eagle-import") (part "STLQ015M33R"))
    )
    (comp (ref "U4")
      (value "STLQ015M33R")
      (footprint "eagle-import:SOT23-5L")
      (fields (field (name "PARTNO") "STLQ015M12R"))
      (libsource (lib "eagle-import") (part "STLQ015M33R"))
    )
    (comp (ref "U5")
      (value "STLQ015M33R")
      (footprint "eagle-import:SOT23-5L")
      (libsource (lib "eagle-import") (part "STLQ015M33R"))
    )
    (comp (ref "U6")
      (value "STLQ015M33R")
      (footprint "eagle-import:SOT23-5L")
      (libsource (lib "eagle-import") (part "STLQ015M33R"))
    )
    (comp (ref "U7")
      (value "STLQ015M12R")
      (footprint "eagle-import:SOT23-5L")
      (libsource (lib "eagle-import") (part "STLQ015M12R"))
    )
    (comp (ref "U8")
      (value "STLQ015M33R")
      (footprint "eagle-import:SOT23-5L")
      (libsource (lib "eagle-import") (part "STLQ015M33R"))
    )
    (comp (ref "U9")
      (value "STLQ015M33R")
      (footprint "eagle-import:SOT23-5L")
      (libsource (lib "eagle-import") (part "STLQ015M33R"))
    )
    (comp (ref "C53")
      (value "1uF")
      (footprint "eagle-import:C0603")
      (fields (field (name "PARTNO") "C0805C220J5GACTU"))
      (libsource (lib "eagle-import") (part "C-USC0603"))
    )
    (comp (ref "TP33")
      (value "TPB1,27")
      (footprint "eagle-import:B1,27")
      (fields (field (name "TP_SIGNAL_NAME") "!FLASH_WP"))
      (libsource (lib "eagle-import") (part "TPB1,27"))
    )
    (comp (ref "TP35")
      (value "TPB1,27")
      (footprint "eagle-import:B1,27")
      (fields (field (name "TP_SIGNAL_NAME") "!FLASH_HOLD"))
      (libsource (lib "eagle-import") (part "TPB1,27"))
    )
    (comp (ref "TP36")
      (value "TPB1,27")
      (footprint "eagle-import:B1,27")
      (fields (field (name "TP_SIGNAL_NAME") "MCU_SPI_MISO"))
      (libsource (lib "eagle-import") (part "TPB1,27"))
    )
    (comp (ref "TP37")
      (value "TPB1,27")
      (footprint "eagle-import:B1,27")
      (fields (field (name "TP_SIGNAL_NAME") "MCU_SPI_CS"))
      (libsource (lib "eagle-import") (part "TPB1,27"))
    )
    (comp (ref "TP38")
      (value "TPB1,27")
      (footprint "eagle-import:B1,27")
      (fields (field (name "TP_SIGNAL_NAME") "MCU_SPI_CLK"))
      (libsource (lib "eagle-import") (part "TPB1,27"))
    )
    (comp (ref "TP39")
      (value "TPB1,27")
      (footprint "eagle-import:B1,27")
      (fields (field (name "TP_SIGNAL_NAME") "MCU_SPI_MOSI"))
      (libsource (lib "eagle-import") (part "TPB1,27"))
    )
    (comp (ref "U13")
      (value "AT25SL128A")
      (footprint "eagle-import:SON127P600X500X60-8N")
      (libsource (lib "eagle-import") (part "AT25SL128A"))
    )
    (comp (ref "C19")
      (value "0.1uF")
      (footprint "eagle-import:C0603")
      (fields (field (name "PARTNO") "08055C104KAT2A"))
      (libsource (lib "eagle-import") (part "rcl_334_C-USC0603"))
    )
    (comp (ref "U10")
      (value "HDC1080")
      (footprint "eagle-import:WSON-6")
      (fields (field (name "PARTNO") "HDC1080DMBT"))
      (libsource (lib "eagle-import") (part "HDC1080"))
    )
    (comp (ref "DISPLAY")
      (value "GREEN")
      (footprint "eagle-import:CHIPLED_0603")
      (fields (field (name "PARTNO") "LG R971-KN-1"))
      (libsource (lib "eagle-import") (part "LEDCHIPLED_0603"))
    )
    (comp (ref "FPGA")
      (value "GREEN")
      (footprint "eagle-import:CHIPLED_0603")
      (fields (field (name "PARTNO") "LG R971-KN-1"))
      (libsource (lib "eagle-import") (part "LEDCHIPLED_0603"))
    )
    (comp (ref "HDC1080")
      (value "GREEN")
      (footprint "eagle-import:CHIPLED_0603")
      (fields (field (name "PARTNO") "LG R971-KN-1"))
      (libsource (lib "eagle-import") (part "LEDCHIPLED_0603"))
    )
    (comp (ref "LED1")
      (value "GREEN")
      (footprint "eagle-import:CHIPLED_0603")
      (fields (field (name "PARTNO") "LG R971-KN-1"))
      (libsource (lib "eagle-import") (part "LEDCHIPLED_0603"))
    )
    (comp (ref "LED2")
      (value "GREEN")
      (footprint "eagle-import:CHIPLED_0603")
      (fields (field (name "PARTNO") "LG R971-KN-1"))
      (libsource (lib "eagle-import") (part "LEDCHIPLED_0603"))
    )
    (comp (ref "MCU")
      (value "GREEN")
      (footprint "eagle-import:CHIPLED_0603")
      (fields (field (name "PARTNO") "LG R971-KN-1"))
      (libsource (lib "eagle-import") (part "LEDCHIPLED_0603"))
    )
    (comp (ref "MEMORY")
      (value "GREEN")
      (footprint "eagle-import:CHIPLED_0603")
      (fields (field (name "PARTNO") "LG R971-KN-1"))
      (libsource (lib "eagle-import") (part "LEDCHIPLED_0603"))
    )
    (comp (ref "OPT3001")
      (value "GREEN")
      (footprint "eagle-import:CHIPLED_0603")
      (fields (field (name "PARTNO") "LG R971-KN-1"))
      (libsource (lib "eagle-import") (part "LEDCHIPLED_0603"))
    )
    (comp (ref "R6")
      (value "330")
      (footprint "eagle-import:R0603")
      (fields (field (name "PARTNO") "RMCF0805JT330R"))
      (libsource (lib "eagle-import") (part "R-US_R0603"))
    )
    (comp (ref "R7")
      (value "330")
      (footprint "eagle-import:R0603")
      (fields (field (name "PARTNO") "RMCF0805JT330R"))
      (libsource (lib "eagle-import") (part "R-US_R0603"))
    )
    (comp (ref "R8")
      (value "330")
      (footprint "eagle-import:R0603")
      (fields (field (name "PARTNO") "RMCF0805JT330R"))
      (libsource (lib "eagle-import") (part "R-US_R0603"))
    )
    (comp (ref "R9")
      (value "330")
      (footprint "eagle-import:R0603")
      (fields (field (name "PARTNO") "RMCF0805JT330R"))
      (libsource (lib "eagle-import") (part "R-US_R0603"))
    )
    (comp (ref "R10")
      (value "330")
      (footprint "eagle-import:R0603")
      (fields (field (name "PARTNO") "RMCF0805JT330R"))
      (libsource (lib "eagle-import") (part "R-US_R0603"))
    )
    (comp (ref "R11")
      (value "330")
      (footprint "eagle-import:R0603")
      (fields (field (name "PARTNO") "RMCF0805JT330R"))
      (libsource (lib "eagle-import") (part "R-US_R0603"))
    )
    (comp (ref "R12")
      (value "330")
      (footprint "eagle-import:R0603")
      (fields (field (name "PARTNO") "RMCF0805JT330R"))
      (libsource (lib "eagle-import") (part "R-US_R0603"))
    )
    (comp (ref "R13")
      (value "330")
      (footprint "eagle-import:R0603")
      (fields (field (name "PARTNO") "RMCF0805JT330R"))
      (libsource (lib "eagle-import") (part "R-US_R0603"))
    )
    (comp (ref "R14")
      (value "330")
      (footprint "eagle-import:R0603")
      (fields (field (name "PARTNO") "RMCF0805JT330R"))
      (libsource (lib "eagle-import") (part "R-US_R0603"))
    )
    (comp (ref "XBEE")
      (value "GREEN")
      (footprint "eagle-import:CHIPLED_0603")
      (fields (field (name "PARTNO") "LG R971-KN-1"))
      (libsource (lib "eagle-import") (part "LEDCHIPLED_0603"))
    )
    (comp (ref "TP34")
      (value "TPB1,27")
      (footprint "eagle-import:B1,27")
      (fields (field (name "TP_SIGNAL_NAME") "FRAM_WP"))
      (libsource (lib "eagle-import") (part "TPB1,27"))
    )
    (comp (ref "U17")
      (value "FM24CL16B")
      (footprint "eagle-import:FM24CL16B")
      (libsource (lib "eagle-import") (part "FM24CL16B"))
    )
    (comp (ref "C21")
      (value "1nF")
      (footprint "eagle-import:C0603")
      (fields (field (name "PARTNO") "08053F102K4T2A"))
      (libsource (lib "eagle-import") (part "C-USC0603"))
    )
    (comp (ref "C22")
      (value "22pF")
      (footprint "eagle-import:C0603")
      (fields (field (name "PARTNO") "C0805C220J5GACTU"))
      (libsource (lib "eagle-import") (part "C-USC0603"))
    )
    (comp (ref "C23")
      (value "22pF")
      (footprint "eagle-import:C0603")
      (fields (field (name "PARTNO") "C0805C220J5GACTU"))
      (libsource (lib "eagle-import") (part "C-USC0603"))
    )
    (comp (ref "C24")
      (value "22pF")
      (footprint "eagle-import:C0603")
      (fields (field (name "PARTNO") "C0805C220J5GACTU"))
      (libsource (lib "eagle-import") (part "C-USC0603"))
    )
    (comp (ref "C25")
      (value "22pF")
      (footprint "eagle-import:C0603")
      (fields (field (name "PARTNO") "C0805C220J5GACTU"))
      (libsource (lib "eagle-import") (part "C-USC0603"))
    )
    (comp (ref "C26")
      (value "100nF")
      (footprint "eagle-import:C0603")
      (fields (field (name "PARTNO") "CC0603ZRY5V9BB104"))
      (libsource (lib "eagle-import") (part "C-USC0603"))
    )
    (comp (ref "C27")
      (value "4uF")
      (footprint "eagle-import:C0603")
      (fields (field (name "PARTNO") "C0805C395K8PACTU"))
      (libsource (lib "eagle-import") (part "C-USC0603"))
    )
    (comp (ref "C28")
      (value "4.7uF")
      (footprint "eagle-import:C0603")
      (fields (field (name "PARTNO") "CL21A475KBQNNNE"))
      (libsource (lib "eagle-import") (part "C-USC0603"))
    )
    (comp (ref "C29")
      (value "100nF")
      (footprint "eagle-import:C0603")
      (fields (field (name "PARTNO") "CC0603ZRY5V9BB104"))
      (libsource (lib "eagle-import") (part "C-USC0603"))
    )
    (comp (ref "C30")
      (value "4.7uF")
      (footprint "eagle-import:C0603")
      (fields (field (name "PARTNO") "CL21A475KBQNNNE"))
      (libsource (lib "eagle-import") (part "C-USC0603"))
    )
    (comp (ref "C31")
      (value "100nF")
      (footprint "eagle-import:C0603")
      (fields (field (name "PARTNO") "CC0603ZRY5V9BB104"))
      (libsource (lib "eagle-import") (part "C-USC0603"))
    )
    (comp (ref "C32")
      (value "4.7uF")
      (footprint "eagle-import:C0603")
      (fields (field (name "PARTNO") "CL21A475KBQNNNE"))
      (libsource (lib "eagle-import") (part "C-USC0603"))
    )
    (comp (ref "C33")
      (value "100nF")
      (footprint "eagle-import:C0603")
      (fields (field (name "PARTNO") "CC0603ZRY5V9BB104"))
      (libsource (lib "eagle-import") (part "C-USC0603"))
    )
    (comp (ref "C34")
      (value "4.7uF")
      (footprint "eagle-import:C0603")
      (fields (field (name "PARTNO") "CL21A475KBQNNNE"))
      (libsource (lib "eagle-import") (part "C-USC0603"))
    )
    (comp (ref "C35")
      (value "100nF")
      (footprint "eagle-import:C0603")
      (fields (field (name "PARTNO") "CC0603ZRY5V9BB104"))
      (libsource (lib "eagle-import") (part "C-USC0603"))
    )
    (comp (ref "JP12")
      (value "CORTEX_DEBUG_10PIN")
      (footprint "eagle-import:CORTEX_DEBUG_10PIN")
      (fields (field (name "PARTNO") "3220-10-0100-00"))
      (libsource (lib "eagle-import") (part "CORTEX_DEBUG_10PIN"))
    )
    (comp (ref "L1")
      (value "4.7uH")
      (footprint "eagle-import:L-USL0805")
      (fields (field (name "PARTNO") "BRC2012T4R7MD"))
      (libsource (lib "eagle-import") (part "L-US"))
    )
    (comp (ref "Q1")
      (value "CPFBZ-A2C4-32.768KD6")
      (footprint "eagle-import:CPFBZ-A2C4-32.768KD6")
      (libsource (lib "eagle-import") (part "CPFBZ-A2C4-32.768KD6"))
    )
    (comp (ref "Q2")
      (value "ABM8-48.000MHZ-B2-T")
      (footprint "eagle-import:CRYSTAL_4-SMD")
      (libsource (lib "eagle-import") (part "ABM8-48.000MHZ-B2-T"))
    )
    (comp (ref "R18")
      (value "1K")
      (footprint "eagle-import:R0603")
      (fields (field (name "PARTNO") "RC0805JR-071KL"))
      (libsource (lib "eagle-import") (part "R-US_R0603"))
    )
    (comp (ref "R20")
      (value "1K")
      (footprint "eagle-import:R0603")
      (fields (field (name "PARTNO") "RC0805JR-071KL"))
      (libsource (lib "eagle-import") (part "R-US_R0603"))
    )
    (comp (ref "R26")
      (value "91k")
      (footprint "eagle-import:R0603")
      (fields (field (name "PARTNO") "RC0805JR-0791KL"))
      (libsource (lib "eagle-import") (part "R-US_R0603"))
    )
    (comp (ref "SW1")
      (value "TACTILE-SWITCH-SMT")
      (footprint "eagle-import:7914G")
      (fields (field (name "PARTNO") "7914G-1-000E"))
      (libsource (lib "eagle-import") (part "TACTILE-SWITCH-SMT"))
    )
    (comp (ref "TP19")
      (value "TPB1,27")
      (footprint "eagle-import:B1,27")
      (fields (field (name "TP_SIGNAL_NAME") "!RST"))
      (libsource (lib "eagle-import") (part "TPB1,27"))
    )
    (comp (ref "TP20")
      (value "TPB1,27")
      (footprint "eagle-import:B1,27")
      (fields (field (name "TP_SIGNAL_NAME") "FREQ_HF"))
      (libsource (lib "eagle-import") (part "TPB1,27"))
    )
    (comp (ref "TP21")
      (value "TPB1,27")
      (footprint "eagle-import:B1,27")
      (fields (field (name "TP_SIGNAL_NAME") "FREQ_LF"))
      (libsource (lib "eagle-import") (part "TPB1,27"))
    )
    (comp (ref "C1")
      (value "1uF")
      (footprint "eagle-import:C0603")
      (libsource (lib "eagle-import") (part "rcl_334_C-USC0603"))
    )
    (comp (ref "C2")
      (value "1uF")
      (footprint "eagle-import:C0603")
      (libsource (lib "eagle-import") (part "rcl_334_C-USC0603"))
    )
    (comp (ref "C36")
      (value "1uF")
      (footprint "eagle-import:C0603")
      (libsource (lib "eagle-import") (part "rcl_334_C-USC0603"))
    )
    (comp (ref "C39")
      (value "1uF")
      (footprint "eagle-import:C0603")
      (libsource (lib "eagle-import") (part "rcl_334_C-USC0603"))
    )
    (comp (ref "C40")
      (value "1uF")
      (footprint "eagle-import:C0603")
      (libsource (lib "eagle-import") (part "rcl_334_C-USC0603"))
    )
    (comp (ref "C41")
      (value "1uF")
      (footprint "eagle-import:C0603")
      (libsource (lib "eagle-import") (part "rcl_334_C-USC0603"))
    )
    (comp (ref "C44")
      (value "1uF")
      (footprint "eagle-import:C0603")
      (libsource (lib "eagle-import") (part "rcl_334_C-USC0603"))
    )
    (comp (ref "C45")
      (value "1uF")
      (footprint "eagle-import:C0603")
      (libsource (lib "eagle-import") (part "rcl_334_C-USC0603"))
    )
    (comp (ref "C48")
      (value "1uF")
      (footprint "eagle-import:C0603")
      (libsource (lib "eagle-import") (part "rcl_334_C-USC0603"))
    )
    (comp (ref "C49")
      (value "1uF")
      (footprint "eagle-import:C0603")
      (libsource (lib "eagle-import") (part "rcl_334_C-USC0603"))
    )
    (comp (ref "C52")
      (value "1uF")
      (footprint "eagle-import:C0603")
      (libsource (lib "eagle-import") (part "rcl_334_C-USC0603"))
    )
    (comp (ref "D1")
      (value "SCHOTTKY")
      (footprint "eagle-import:SOD3716X128")
      (fields (field (name "MPN") "MBR0530 "))
      (libsource (lib "eagle-import") (part "SCHOTTKY"))
    )
    (comp (ref "D3")
      (value "SCHOTTKY")
      (footprint "eagle-import:SOD3716X128")
      (fields (field (name "MPN") "MBR0530 "))
      (libsource (lib "eagle-import") (part "SCHOTTKY"))
    )
    (comp (ref "D4")
      (value "SCHOTTKY")
      (footprint "eagle-import:SOD3716X128")
      (fields (field (name "MPN") "MBR0530 "))
      (libsource (lib "eagle-import") (part "SCHOTTKY"))
    )
    (comp (ref "L2")
      (value "100uH")
      (footprint "eagle-import:LPS3015")
      (libsource (lib "eagle-import") (part "L_US3015"))
    )
    (comp (ref "Q3")
      (value "MOSFET-NCH")
      (footprint "eagle-import:SOT95P237X112-3")
      (fields (field (name "MPN") "IRLML6346TRPBF "))
      (libsource (lib "eagle-import") (part "MOSFET-NCH"))
    )
    (comp (ref "R1")
      (value "0.47")
      (footprint "eagle-import:R0603")
      (libsource (lib "eagle-import") (part "rcl_334_R-US_R0603"))
    )
    (comp (ref "R2")
      (value "100k")
      (footprint "eagle-import:R0603")
      (libsource (lib "eagle-import") (part "rcl_334_R-US_R0603"))
    )
    (comp (ref "U18")
      (value "4.2-E-INK-DISPLAY")
      (footprint "eagle-import:FPC-24PIN-0.5MM")
      (libsource (lib "eagle-import") (part "4.2-E-INK-DISPLAY"))
    )
  )
  (nets
    (net (code "1") (name "+BAT") (class "Default")
      (node (ref "C10") (pin "1") (pinfunction "1_1") (pintype "passive"))
      (node (ref "C13") (pin "1") (pinfunction "1_1") (pintype "passive"))
      (node (ref "C14") (pin "1") (pinfunction "1_1") (pintype "passive"))
      (node (ref "C17") (pin "1") (pinfunction "1_1") (pintype "passive"))
      (node (ref "C4") (pin "1") (pinfunction "1_1") (pintype "passive"))
      (node (ref "C5") (pin "1") (pinfunction "1_1") (pintype "passive"))
      (node (ref "C6") (pin "1") (pinfunction "1_1") (pintype "passive"))
      (node (ref "C9") (pin "1") (pinfunction "1_1") (pintype "passive"))
      (node (ref "D2") (pin "C") (pinfunction "C_C") (pintype "passive"))
      (node (ref "J1") (pin "2") (pinfunction "+_2") (pintype "bidirectional"))
      (node (ref "R3") (pin "2") (pinfunction "2_2") (pintype "passive"))
      (node (ref "R6") (pin "2") (pinfunction "2_2") (pintype "passive"))
      (node (ref "TP1") (pin "TP") (pinfunction "TP_TP") (pintype "input"))
      (node (ref "U16") (pin "14") (pinfunction "VDD_14") (pintype "bidirectional"))
      (node (ref "U16") (pin "4") (pinfunction "VBAT_4") (pintype "bidirectional"))
      (node (ref "U2") (pin "3") (pinfunction "VBAT_3") (pintype "bidirectional"))
      (node (ref "U3") (pin "1") (pinfunction "VIN_1") (pintype "bidirectional"))
      (node (ref "U4") (pin "1") (pinfunction "VIN_1") (pintype "bidirectional"))
      (node (ref "U5") (pin "1") (pinfunction "VIN_1") (pintype "bidirectional"))
      (node (ref "U6") (pin "1") (pinfunction "VIN_1") (pintype "bidirectional"))
      (node (ref "U7") (pin "1") (pinfunction "VIN_1") (pintype "bidirectional"))
      (node (ref "U8") (pin "1") (pinfunction "VIN_1") (pintype "bidirectional"))
      (node (ref "U8") (pin "3") (pinfunction "EN_3") (pintype "bidirectional"))
      (node (ref "U9") (pin "1") (pinfunction "VIN_1") (pintype "bidirectional"))
    )
    (net (code "2") (name "ASSOCIATE_LED") (class "Default")
      (node (ref "JP26") (pin "15") (pinfunction "DIO5_15") (pintype "bidirectional"))
      (node (ref "R39") (pin "1") (pinfunction "1_1") (pintype "passive"))
    )
    (net (code "3") (name "CHARGE_STATUS") (class "Default")
      (node (ref "LED11") (pin "C") (pinfunction "C_C") (pintype "passive"))
      (node (ref "R17") (pin "1") (pinfunction "1_1") (pintype "passive"))
      (node (ref "TP25") (pin "TP") (pinfunction "TP_TP") (pintype "input"))
      (node (ref "U12") (pin "32") (pinfunction "P3.0/PM_UCA2STE_32") (pintype "bidirectional"))
    )
    (net (code "4") (name "DISPLAY_D{slash}~{C}") (class "Default")
      (node (ref "TP27") (pin "TP") (pinfunction "TP_TP") (pintype "input"))
      (node (ref "U12") (pin "36") (pinfunction "P3.4/PM_UCB2STE_36") (pintype "bidirectional"))
      (node (ref "U18") (pin "11") (pinfunction "D/~{C}_11") (pintype "bidirectional"))
    )
    (net (code "5") (name "EINK_BUSY") (class "Default")
      (node (ref "TP32") (pin "TP") (pinfunction "TP_TP") (pintype "input"))
      (node (ref "U12") (pin "47") (pinfunction "P8.3/TA3CLK/A22_47") (pintype "bidirectional"))
      (node (ref "U18") (pin "9") (pinfunction "BUSY_9") (pintype "bidirectional"))
    )
    (net (code "6") (name "EINK_~{RST}") (class "Default")
      (node (ref "TP31") (pin "TP") (pinfunction "TP_TP") (pintype "input"))
      (node (ref "U12") (pin "46") (pinfunction "P8.2/TA3.2/A23_46") (pintype "bidirectional"))
      (node (ref "U18") (pin "10") (pinfunction "~{RST}_10") (pintype "bidirectional"))
    )
    (net (code "7") (name "FPGA_DONE") (class "Default")
      (node (ref "U1") (pin "76") (pinfunction "PT11D/DONE_76") (pintype "bidirectional"))
      (node (ref "U12") (pin "23") (pinfunction "P2.7/PM_TA0.4_23") (pintype "bidirectional"))
    )
    (net (code "8") (name "FRAM_WP") (class "Default")
      (node (ref "TP34") (pin "TP") (pinfunction "TP_TP") (pintype "input"))
      (node (ref "U12") (pin "4") (pinfunction "P1.0/UCA0STE_4") (pintype "bidirectional"))
      (node (ref "U17") (pin "7") (pinfunction "WP_7") (pintype "bidirectional"))
    )
    (net (code "9") (name "FREQ_HF") (class "Default")
      (node (ref "C24") (pin "1") (pinfunction "1_1") (pintype "passive"))
      (node (ref "Q2") (pin "P$1") (pinfunction "1_P$1") (pintype "passive"))
      (node (ref "TP20") (pin "TP") (pinfunction "TP_TP") (pintype "input"))
      (node (ref "U12") (pin "85") (pinfunction "PJ.2/HFXOUT_85") (pintype "bidirectional"))
    )
    (net (code "10") (name "FREQ_LF") (class "Default")
      (node (ref "C22") (pin "1") (pinfunction "1_1") (pintype "passive"))
      (node (ref "Q1") (pin "P$1") (pinfunction "1_P$1") (pintype "passive"))
      (node (ref "TP21") (pin "TP") (pinfunction "TP_TP") (pintype "input"))
      (node (ref "U12") (pin "41") (pinfunction "PJ.0/LFXIN_41") (pintype "bidirectional"))
    )
    (net (code "11") (name "GDR") (class "Default")
      (node (ref "Q3") (pin "1") (pinfunction "G_1") (pintype "bidirectional"))
      (node (ref "R2") (pin "2") (pinfunction "2_2") (pintype "passive"))
      (node (ref "U18") (pin "2") (pinfunction "GDR_2") (pintype "bidirectional"))
    )
    (net (code "12") (name "GND") (class "Default")
      (node (ref "C1") (pin "2") (pinfunction "2_2") (pintype "passive"))
      (node (ref "C10") (pin "2") (pinfunction "2_2") (pintype "passive"))
      (node (ref "C11") (pin "2") (pinfunction "2_2") (pintype "passive"))
      (node (ref "C12") (pin "2") (pinfunction "2_2") (pintype "passive"))
      (node (ref "C13") (pin "2") (pinfunction "2_2") (pintype "passive"))
      (node (ref "C14") (pin "2") (pinfunction "2_2") (pintype "passive"))
      (node (ref "C15") (pin "2") (pinfunction "2_2") (pintype "passive"))
      (node (ref "C16") (pin "2") (pinfunction "2_2") (pintype "passive"))
      (node (ref "C17") (pin "2") (pinfunction "2_2") (pintype "passive"))
      (node (ref "C18") (pin "2") (pinfunction "2_2") (pintype "passive"))
      (node (ref "C19") (pin "2") (pinfunction "2_2") (pintype "passive"))
      (node (ref "C2") (pin "2") (pinfunction "2_2") (pintype "passive"))
      (node (ref "C20") (pin "2") (pinfunction "2_2") (pintype "passive"))
      (node (ref "C21") (pin "2") (pinfunction "2_2") (pintype "passive"))
      (node (ref "C22") (pin "2") (pinfunction "2_2") (pintype "passive"))
      (node (ref "C23") (pin "2") (pinfunction "2_2") (pintype "passive"))
      (node (ref "C24") (pin "2") (pinfunction "2_2") (pintype "passive"))
      (node (ref "C25") (pin "2") (pinfunction "2_2") (pintype "passive"))
      (node (ref "C26") (pin "2") (pinfunction "2_2") (pintype "passive"))
      (node (ref "C27") (pin "2") (pinfunction "2_2") (pintype "passive"))
      (node (ref "C28") (pin "2") (pinfunction "2_2") (pintype "passive"))
      (node (ref "C29") (pin "2") (pinfunction "2_2") (pintype "passive"))
      (node (ref "C3") (pin "2") (pinfunction "2_2") (pintype "passive"))
      (node (ref "C30") (pin "2") (pinfunction "2_2") (pintype "passive"))
      (node (ref "C31") (pin "2") (pinfunction "2_2") (pintype "passive"))
      (node (ref "C32") (pin "2") (pinfunction "2_2") (pintype "passive"))
      (node (ref "C33") (pin "2") (pinfunction "2_2") (pintype "passive"))
      (node (ref "C34") (pin "2") (pinfunction "2_2") (pintype "passive"))
      (node (ref "C35") (pin "2") (pinfunction "2_2") (pintype "passive"))
      (node (ref "C36") (pin "2") (pinfunction "2_2") (pintype "passive"))
      (node (ref "C37") (pin "2") (pinfunction "2_2") (pintype "passive"))
      (node (ref "C38") (pin "2") (pinfunction "2_2") (pintype "passive"))
      (node (ref "C39") (pin "2") (pinfunction "2_2") (pintype "passive"))
      (node (ref "C4") (pin "2") (pinfunction "2_2") (pintype "passive"))
      (node (ref "C40") (pin "2") (pinfunction "2_2") (pintype "passive"))
      (node (ref "C41") (pin "2") (pinfunction "2_2") (pintype "passive"))
      (node (ref "C42") (pin "2") (pinfunction "2_2") (pintype "passive"))
      (node (ref "C43") (pin "2") (pinfunction "2_2") (pintype "passive"))
      (node (ref "C44") (pin "2") (pinfunction "2_2") (pintype "passive"))
      (node (ref "C45") (pin "2") (pinfunction "2_2") (pintype "passive"))
      (node (ref "C46") (pin "2") (pinfunction "2_2") (pintype "passive"))
      (node (ref "C47") (pin "2") (pinfunction "2_2") (pintype "passive"))
      (node (ref "C48") (pin "2") (pinfunction "2_2") (pintype "passive"))
      (node (ref "C49") (pin "2") (pinfunction "2_2") (pintype "passive"))
      (node (ref "C5") (pin "2") (pinfunction "2_2") (pintype "passive"))
      (node (ref "C50") (pin "2") (pinfunction "2_2") (pintype "passive"))
      (node (ref "C51") (pin "2") (pinfunction "2_2") (pintype "passive"))
      (node (ref "C53") (pin "2") (pinfunction "2_2") (pintype "passive"))
      (node (ref "C54") (pin "2") (pinfunction "2_2") (pintype "passive"))
      (node (ref "C55") (pin "2") (pinfunction "2_2") (pintype "passive"))
      (node (ref "C57") (pin "2") (pinfunction "2_2") (pintype "passive"))
      (node (ref "C6") (pin "2") (pinfunction "2_2") (pintype "passive"))
      (node (ref "C68") (pin "2") (pinfunction "2_2") (pintype "passive"))
      (node (ref "C7") (pin "2") (pinfunction "2_2") (pintype "passive"))
      (node (ref "C8") (pin "2") (pinfunction "2_2") (pintype "passive"))
      (node (ref "C9") (pin "2") (pinfunction "2_2") (pintype "passive"))
      (node (ref "D2") (pin "A") (pinfunction "A_A") (pintype "passive"))
      (node (ref "D4") (pin "2") (pinfunction "C_2") (pintype "passive"))
      (node (ref "DISPLAY") (pin "C") (pinfunction "C_C") (pintype "passive"))
      (node (ref "FPGA") (pin "C") (pinfunction "C_C") (pintype "passive"))
      (node (ref "HDC1080") (pin "C") (pinfunction "C_C") (pintype "passive"))
      (node (ref "J1") (pin "1") (pinfunction "-_1") (pintype "bidirectional"))
      (node (ref "JP1") (pin "10") (pinfunction "10_10") (pintype "bidirectional"))
      (node (ref "JP12") (pin "3") (pinfunction "GND_3") (pintype "bidirectional"))
      (node (ref "JP12") (pin "5") (pinfunction "GND_5") (pintype "bidirectional"))
      (node (ref "JP12") (pin "9") (pinfunction "GNDDTCT_9") (pintype "bidirectional"))
      (node (ref "JP26") (pin "10") (pinfunction "GND_10") (pintype "power_in"))
      (node (ref "JP3") (pin "2") (pinfunction "2_2") (pintype "bidirectional"))
      (node (ref "JP3") (pin "4") (pinfunction "4_4") (pintype "bidirectional"))
      (node (ref "JP4") (pin "8") (pinfunction "8_8") (pintype "bidirectional"))
      (node (ref "LED1") (pin "C") (pinfunction "C_C") (pintype "passive"))
      (node (ref "LED16") (pin "C") (pinfunction "C_C") (pintype "passive"))
      (node (ref "LED17") (pin "C") (pinfunction "C_C") (pintype "passive"))
      (node (ref "LED18") (pin "C") (pinfunction "C_C") (pintype "passive"))
      (node (ref "LED2") (pin "C") (pinfunction "C_C") (pintype "passive"))
      (node (ref "MCU") (pin "C") (pinfunction "C_C") (pintype "passive"))
      (node (ref "MEMORY") (pin "C") (pinfunction "C_C") (pintype "passive"))
      (node (ref "OPT3001") (pin "C") (pinfunction "C_C") (pintype "passive"))
      (node (ref "R1") (pin "1") (pinfunction "1_1") (pintype "passive"))
      (node (ref "R16") (pin "2") (pinfunction "2_2") (pintype "passive"))
      (node (ref "R2") (pin "1") (pinfunction "1_1") (pintype "passive"))
      (node (ref "R26") (pin "1") (pinfunction "1_1") (pintype "passive"))
      (node (ref "R35") (pin "1") (pinfunction "1_1") (pintype "passive"))
      (node (ref "SW1") (pin "3") (pinfunction "3_3") (pintype "passive"))
      (node (ref "SW1") (pin "4") (pinfunction "4_4") (pintype "passive"))
      (node (ref "TP11") (pin "TP") (pinfunction "TP_TP") (pintype "input"))
      (node (ref "TP12") (pin "TP") (pinfunction "TP_TP") (pintype "input"))
      (node (ref "TP13") (pin "TP") (pinfunction "TP_TP") (pintype "input"))
      (node (ref "TP14") (pin "TP") (pinfunction "TP_TP") (pintype "input"))
      (node (ref "TP15") (pin "TP") (pinfunction "TP_TP") (pintype "input"))
      (node (ref "TP16") (pin "TP") (pinfunction "TP_TP") (pintype "input"))
      (node (ref "TP17") (pin "TP") (pinfunction "TP_TP") (pintype "input"))
      (node (ref "TP18") (pin "TP") (pinfunction "TP_TP") (pintype "input"))
      (node (ref "TP2") (pin "TP") (pinfunction "TP_TP") (pintype "input"))
      (node (ref "U1") (pin "22") (pinfunction "GND_22") (pintype "bidirectional"))
      (node (ref "U1") (pin "33") (pinfunction "GND_33") (pintype "bidirectional"))
      (node (ref "U1") (pin "44") (pinfunction "GND_44") (pintype "bidirectional"))
      (node (ref "U1") (pin "56") (pinfunction "GND_56") (pintype "bidirectional"))
      (node (ref "U1") (pin "6") (pinfunction "GND_6") (pintype "bidirectional"))
      (node (ref "U1") (pin "72") (pinfunction "GND_72") (pintype "bidirectional"))
      (node (ref "U1") (pin "79") (pinfunction "GND_79") (pintype "bidirectional"))
      (node (ref "U1") (pin "92") (pinfunction "GND_92") (pintype "bidirectional"))
      (node (ref "U10") (pin "2") (pinfunction "GND_2") (pintype "bidirectional"))
      (node (ref "U11") (pin "3") (pinfunction "GND_3") (pintype "bidirectional"))
      (node (ref "U11") (pin "7") (pinfunction "GND_PAD_7") (pintype "bidirectional"))
      (node (ref "U12") (pin "15") (pinfunction "DVSS1_15") (pintype "bidirectional"))
      (node (ref "U12") (pin "40") (pinfunction "AVSS3_40") (pintype "bidirectional"))
      (node (ref "U12") (pin "43") (pinfunction "AVSS1_43") (pintype "bidirectional"))
      (node (ref "U12") (pin "72") (pinfunction "DVSS2_72") (pintype "bidirectional"))
      (node (ref "U12") (pin "82") (pinfunction "DVSS3_82") (pintype "bidirectional"))
      (node (ref "U12") (pin "84") (pinfunction "AVSS2_84") (pintype "bidirectional"))
      (node (ref "U13") (pin "4") (pinfunction "GND_4") (pintype "bidirectional"))
      (node (ref "U16") (pin "5") (pinfunction "VSS_5") (pintype "bidirectional"))
      (node (ref "U17") (pin "4") (pinfunction "VSS_4") (pintype "bidirectional"))
      (node (ref "U18") (pin "17") (pinfunction "VSS_17") (pintype "bidirectional"))
      (node (ref "U18") (pin "8") (pinfunction "BS1_8") (pintype "bidirectional"))
      (node (ref "U2") (pin "2") (pinfunction "VSS_2") (pintype "bidirectional"))
      (node (ref "U3") (pin "2") (pinfunction "GND_2") (pintype "bidirectional"))
      (node (ref "U4") (pin "2") (pinfunction "GND_2") (pintype "bidirectional"))
      (node (ref "U5") (pin "2") (pinfunction "GND_2") (pintype "bidirectional"))
      (node (ref "U6") (pin "2") (pinfunction "GND_2") (pintype "bidirectional"))
      (node (ref "U7") (pin "2") (pinfunction "GND_2") (pintype "bidirectional"))
      (node (ref "U8") (pin "2") (pinfunction "GND_2") (pintype "bidirectional"))
      (node (ref "U9") (pin "2") (pinfunction "GND_2") (pintype "bidirectional"))
      (node (ref "X1") (pin "5") (pinfunction "5_5") (pintype "passive"))
      (node (ref "XBEE") (pin "C") (pinfunction "C_C") (pintype "passive"))
    )
    (net (code "13") (name "INTERRUPT_OPT3001") (class "Default")
      (node (ref "U11") (pin "5") (pinfunction "INT_5") (pintype "bidirectional"))
      (node (ref "U12") (pin "5") (pinfunction "P1.1/UCA0CLK_5") (pintype "bidirectional"))
    )
    (net (code "14") (name "MCU_EN_CTL3") (class "Default")
      (node (ref "U12") (pin "19") (pinfunction "P2.3/PM_UCA1TXD/PM_UCA1SIMO_19") (pintype "bidirectional"))
      (node (ref "U7") (pin "3") (pinfunction "EN_3") (pintype "bidirectional"))
    )
    (net (code "15") (name "MCU_EN_CTL4") (class "Default")
      (node (ref "U12") (pin "18") (pinfunction "P2.2/PM_UCA1RXD/PM_UCA1SOMI_18") (pintype "bidirectional"))
      (node (ref "U9") (pin "3") (pinfunction "EN_3") (pintype "bidirectional"))
    )
    (net (code "16") (name "MCU_EN_CTL5") (class "Default")
      (node (ref "U12") (pin "39") (pinfunction "P3.7/PM_UCB2SOMI/PM_UCB2SCL_39") (pintype "bidirectional"))
      (node (ref "U4") (pin "3") (pinfunction "EN_3") (pintype "bidirectional"))
    )
    (net (code "17") (name "MCU_EN_CTL6") (class "Default")
      (node (ref "U12") (pin "20") (pinfunction "P2.4/PM_TA0.1_20") (pintype "bidirectional"))
      (node (ref "U6") (pin "3") (pinfunction "EN_3") (pintype "bidirectional"))
    )
    (net (code "18") (name "MCU_FPGA_1") (class "Default")
      (node (ref "U1") (pin "28") (pinfunction "PB4B_28") (pintype "bidirectional"))
      (node (ref "U12") (pin "74") (pinfunction "P9.2/TA3.3_74") (pintype "bidirectional"))
    )
    (net (code "19") (name "MCU_FPGA_2") (class "Default")
      (node (ref "U1") (pin "29") (pinfunction "PB4C_29") (pintype "bidirectional"))
      (node (ref "U12") (pin "71") (pinfunction "P5.7/TA2.2/VREF-/VEREF-/C1.6_71") (pintype "bidirectional"))
    )
    (net (code "20") (name "MCU_FPGA_3") (class "Default")
      (node (ref "U1") (pin "30") (pinfunction "PB4D_30") (pintype "bidirectional"))
      (node (ref "U12") (pin "70") (pinfunction "P5.6/TA2.1/VREF+/VEREF+/C1.7_70") (pintype "bidirectional"))
    )
    (net (code "21") (name "MCU_FPGA_4") (class "Default")
      (node (ref "U1") (pin "31") (pinfunction "PB6A/MCLK/CCLK_31") (pintype "bidirectional"))
      (node (ref "U12") (pin "69") (pinfunction "P5.5/A0_69") (pintype "bidirectional"))
    )
    (net (code "22") (name "MCU_FPGA_5") (class "Default")
      (node (ref "U1") (pin "32") (pinfunction "PB6B/SO/SPISO_32") (pintype "bidirectional"))
      (node (ref "U12") (pin "68") (pinfunction "P5.4/A1_68") (pintype "bidirectional"))
    )
    (net (code "23") (name "MCU_FPGA_6") (class "Default")
      (node (ref "U1") (pin "34") (pinfunction "PB6C/PCLKT2_0_34") (pintype "bidirectional"))
      (node (ref "U12") (pin "67") (pinfunction "P5.3/A2_67") (pintype "bidirectional"))
    )
    (net (code "24") (name "MCU_FPGA_7") (class "Default")
      (node (ref "U1") (pin "35") (pinfunction "PB6D/PCLKC2_0_35") (pintype "bidirectional"))
      (node (ref "U12") (pin "66") (pinfunction "P5.2/A3_66") (pintype "bidirectional"))
    )
    (net (code "25") (name "MCU_FPGA_8") (class "Default")
      (node (ref "U1") (pin "36") (pinfunction "PB10A_36") (pintype "bidirectional"))
      (node (ref "U12") (pin "65") (pinfunction "P5.1/A4_65") (pintype "bidirectional"))
    )
    (net (code "26") (name "MCU_FPGA_9") (class "Default")
      (node (ref "U1") (pin "37") (pinfunction "PB10B_37") (pintype "bidirectional"))
      (node (ref "U12") (pin "64") (pinfunction "P5.0/A5_64") (pintype "bidirectional"))
    )
    (net (code "27") (name "MCU_FPGA_10") (class "Default")
      (node (ref "U1") (pin "38") (pinfunction "PB10C/PCLKT2_1_38") (pintype "bidirectional"))
      (node (ref "U12") (pin "63") (pinfunction "P4.7/A6_63") (pintype "bidirectional"))
    )
    (net (code "28") (name "MCU_FPGA_11") (class "Default")
      (node (ref "U1") (pin "39") (pinfunction "PB10D/PCLKC2_1_39") (pintype "bidirectional"))
      (node (ref "U12") (pin "62") (pinfunction "P4.6/A7_62") (pintype "bidirectional"))
    )
    (net (code "29") (name "MCU_FPGA_12") (class "Default")
      (node (ref "U1") (pin "40") (pinfunction "PB12A_40") (pintype "bidirectional"))
      (node (ref "U12") (pin "61") (pinfunction "P4.5/A8_61") (pintype "bidirectional"))
    )
    (net (code "30") (name "MCU_FPGA_13") (class "Default")
      (node (ref "U1") (pin "41") (pinfunction "PB12B_41") (pintype "bidirectional"))
      (node (ref "U12") (pin "60") (pinfunction "P4.4/HSMCLK/SVMHOUT/A9_60") (pintype "bidirectional"))
    )
    (net (code "31") (name "MCU_FPGA_14") (class "Default")
      (node (ref "U1") (pin "42") (pinfunction "PB12C_42") (pintype "bidirectional"))
      (node (ref "U12") (pin "59") (pinfunction "P4.3/MCLK/RTCCLK/A10_59") (pintype "bidirectional"))
    )
    (net (code "32") (name "MCU_FPGA_15") (class "Default")
      (node (ref "U1") (pin "43") (pinfunction "PB12D_43") (pintype "bidirectional"))
      (node (ref "U12") (pin "58") (pinfunction "P4.2/ACLK/TA2CLK/A11_58") (pintype "bidirectional"))
    )
    (net (code "33") (name "MCU_SCL") (class "Default")
      (node (ref "R25") (pin "1") (pinfunction "1_1") (pintype "passive"))
      (node (ref "TP29") (pin "TP") (pinfunction "TP_TP") (pintype "input"))
      (node (ref "U10") (pin "6") (pinfunction "SCL_6") (pintype "bidirectional"))
      (node (ref "U11") (pin "4") (pinfunction "SCL_4") (pintype "bidirectional"))
      (node (ref "U12") (pin "11") (pinfunction "P1.7/UCB0SOMI/UCB0SCL_11") (pintype "bidirectional"))
      (node (ref "U16") (pin "11") (pinfunction "SCL_11") (pintype "bidirectional"))
      (node (ref "U17") (pin "6") (pinfunction "SCL_6") (pintype "bidirectional"))
    )
    (net (code "34") (name "MCU_SDA") (class "Default")
      (node (ref "R24") (pin "1") (pinfunction "1_1") (pintype "passive"))
      (node (ref "TP30") (pin "TP") (pinfunction "TP_TP") (pintype "input"))
      (node (ref "U10") (pin "1") (pinfunction "SDA_1") (pintype "bidirectional"))
      (node (ref "U11") (pin "6") (pinfunction "SDA_6") (pintype "bidirectional"))
      (node (ref "U12") (pin "10") (pinfunction "P1.6/UCB0SIMO/UCB0SDA_10") (pintype "bidirectional"))
      (node (ref "U16") (pin "10") (pinfunction "SDA_10") (pintype "bidirectional"))
      (node (ref "U17") (pin "5") (pinfunction "SDA_5") (pintype "bidirectional"))
    )
    (net (code "35") (name "MCU_SD_HDC1080") (class "Default")
      (node (ref "U12") (pin "17") (pinfunction "P2.1/PM_UCA1CLK_17") (pintype "bidirectional"))
      (node (ref "U3") (pin "3") (pinfunction "EN_3") (pintype "bidirectional"))
    )
    (net (code "36") (name "MCU_SD_OPT3001") (class "Default")
      (node (ref "U12") (pin "16") (pinfunction "P2.0/PM_UCA1STE_16") (pintype "bidirectional"))
      (node (ref "U5") (pin "3") (pinfunction "EN_3") (pintype "bidirectional"))
    )
    (net (code "37") (name "MCU_SPI_CLK") (class "Default")
      (node (ref "TP38") (pin "TP") (pinfunction "TP_TP") (pintype "input"))
      (node (ref "U12") (pin "77") (pinfunction "P6.3/UCB1CLK/C1.4_77") (pintype "bidirectional"))
      (node (ref "U13") (pin "6") (pinfunction "SCK_6") (pintype "bidirectional"))
    )
    (net (code "38") (name "MCU_SPI_CS") (class "Default")
      (node (ref "TP37") (pin "TP") (pinfunction "TP_TP") (pintype "input"))
      (node (ref "U12") (pin "76") (pinfunction "P6.2/UCB1STE/C1.5_76") (pintype "bidirectional"))
      (node (ref "U13") (pin "1") (pinfunction "~{CS}_1") (pintype "bidirectional"))
    )
    (net (code "39") (name "MCU_SPI_MISO") (class "Default")
      (node (ref "TP36") (pin "TP") (pinfunction "TP_TP") (pintype "input"))
      (node (ref "U12") (pin "79") (pinfunction "P6.5/UCB1SOMI/UCB1SCL/C1.2_79") (pintype "bidirectional"))
      (node (ref "U13") (pin "2") (pinfunction "SO(IO1)_2") (pintype "bidirectional"))
    )
    (net (code "40") (name "MCU_SPI_MOSI") (class "Default")
      (node (ref "TP39") (pin "TP") (pinfunction "TP_TP") (pintype "input"))
      (node (ref "U12") (pin "78") (pinfunction "P6.4/UCB1SIMO/UCB1SDA/C1.3_78") (pintype "bidirectional"))
      (node (ref "U13") (pin "5") (pinfunction "SI_5") (pintype "bidirectional"))
    )
    (net (code "41") (name "Net-(DISPLAY-PadA)") (class "Default")
      (node (ref "DISPLAY") (pin "A") (pinfunction "A_A") (pintype "passive"))
      (node (ref "R14") (pin "1") (pinfunction "1_1") (pintype "passive"))
    )
    (net (code "42") (name "Net-(FPGA-PadA)") (class "Default")
      (node (ref "FPGA") (pin "A") (pinfunction "A_A") (pintype "passive"))
      (node (ref "R11") (pin "1") (pinfunction "1_1") (pintype "passive"))
    )
    (net (code "43") (name "Net-(HDC1080-PadA)") (class "Default")
      (node (ref "HDC1080") (pin "A") (pinfunction "A_A") (pintype "passive"))
      (node (ref "R8") (pin "1") (pinfunction "1_1") (pintype "passive"))
    )
    (net (code "44") (name "Net-(JP12-NC{slash}TDI)") (class "Default")
      (node (ref "JP12") (pin "8") (pinfunction "NC/TDI_8") (pintype "bidirectional"))
      (node (ref "U12") (pin "92") (pinfunction "PJ.4/TDI/ADC14CLK_92") (pintype "bidirectional"))
    )
    (net (code "45") (name "Net-(JP12-SWDCLK{slash}TCK)") (class "Default")
      (node (ref "JP12") (pin "4") (pinfunction "SWDCLK/TCK_4") (pintype "bidirectional"))
      (node (ref "U12") (pin "95") (pinfunction "SWCLK/TCK_95") (pintype "bidirectional"))
    )
    (net (code "46") (name "Net-(JP12-SWDIO{slash}TMS)") (class "Default")
      (node (ref "JP12") (pin "2") (pinfunction "SWDIO/TMS_2") (pintype "bidirectional"))
      (node (ref "U12") (pin "94") (pinfunction "SWDIO/TMS_94") (pintype "bidirectional"))
    )
    (net (code "47") (name "Net-(JP12-SWO{slash}TDO)") (class "Default")
      (node (ref "JP12") (pin "6") (pinfunction "SWO/TDO_6") (pintype "bidirectional"))
      (node (ref "U12") (pin "93") (pinfunction "PJ.5/TDO/SWO_93") (pintype "bidirectional"))
    )
    (net (code "48") (name "Net-(JP12-VCC)") (class "Default")
      (node (ref "JP12") (pin "1") (pinfunction "VCC_1") (pintype "bidirectional"))
      (node (ref "R18") (pin "2") (pinfunction "2_2") (pintype "passive"))
    )
    (net (code "49") (name "Net-(LED1-PadA)") (class "Default")
      (node (ref "LED1") (pin "A") (pinfunction "A_A") (pintype "passive"))
      (node (ref "R6") (pin "1") (pinfunction "1_1") (pintype "passive"))
    )
    (net (code "50") (name "Net-(LED2-PadA)") (class "Default")
      (node (ref "LED2") (pin "A") (pinfunction "A_A") (pintype "passive"))
      (node (ref "R7") (pin "1") (pinfunction "1_1") (pintype "passive"))
    )
    (net (code "51") (name "Net-(LED12-PadC)") (class "Default")
      (node (ref "LED12") (pin "C") (pinfunction "C_C") (pintype "passive"))
      (node (ref "R27") (pin "1") (pinfunction "1_1") (pintype "passive"))
    )
    (net (code "52") (name "Net-(LED14-PadC)") (class "Default")
      (node (ref "LED14") (pin "C") (pinfunction "C_C") (pintype "passive"))
      (node (ref "R37") (pin "2") (pinfunction "2_2") (pintype "passive"))
    )
    (net (code "53") (name "Net-(LED15-PadC)") (class "Default")
      (node (ref "LED15") (pin "C") (pinfunction "C_C") (pintype "passive"))
      (node (ref "R38") (pin "2") (pinfunction "2_2") (pintype "passive"))
    )
    (net (code "54") (name "Net-(LED16-PadA)") (class "Default")
      (node (ref "LED16") (pin "A") (pinfunction "A_A") (pintype "passive"))
      (node (ref "R39") (pin "2") (pinfunction "2_2") (pintype "passive"))
    )
    (net (code "55") (name "Net-(LED17-PadA)") (class "Default")
      (node (ref "LED17") (pin "A") (pinfunction "A_A") (pintype "passive"))
      (node (ref "R40") (pin "2") (pinfunction "2_2") (pintype "passive"))
    )
    (net (code "56") (name "Net-(LED18-PadA)") (class "Default")
      (node (ref "LED18") (pin "A") (pinfunction "A_A") (pintype "passive"))
      (node (ref "R41") (pin "2") (pinfunction "2_2") (pintype "passive"))
    )
    (net (code "57") (name "Net-(MCU-PadA)") (class "Default")
      (node (ref "MCU") (pin "A") (pinfunction "A_A") (pintype "passive"))
      (node (ref "R10") (pin "1") (pinfunction "1_1") (pintype "passive"))
    )
    (net (code "58") (name "Net-(MEMORY-PadA)") (class "Default")
      (node (ref "MEMORY") (pin "A") (pinfunction "A_A") (pintype "passive"))
      (node (ref "R13") (pin "1") (pinfunction "1_1") (pintype "passive"))
    )
    (net (code "59") (name "Net-(OPT3001-PadA)") (class "Default")
      (node (ref "OPT3001") (pin "A") (pinfunction "A_A") (pintype "passive"))
      (node (ref "R9") (pin "1") (pinfunction "1_1") (pintype "passive"))
    )
    (net (code "60") (name "Net-(Q1-2)") (class "Default")
      (node (ref "C23") (pin "1") (pinfunction "1_1") (pintype "passive"))
      (node (ref "Q1") (pin "P$4") (pinfunction "2_P$4") (pintype "passive"))
      (node (ref "U12") (pin "42") (pinfunction "PJ.1/LFXOUT_42") (pintype "bidirectional"))
    )
    (net (code "61") (name "Net-(Q2-2)") (class "Default")
      (node (ref "C25") (pin "1") (pinfunction "1_1") (pintype "passive"))
      (node (ref "Q2") (pin "P$3") (pinfunction "2_P$3") (pintype "passive"))
      (node (ref "U12") (pin "86") (pinfunction "PJ.3/HFXIN_86") (pintype "bidirectional"))
    )
    (net (code "62") (name "Net-(R12-Pad1)") (class "Default")
      (node (ref "R12") (pin "1") (pinfunction "1_1") (pintype "passive"))
      (node (ref "XBEE") (pin "A") (pinfunction "A_A") (pintype "passive"))
    )
    (net (code "63") (name "Net-(U2-PROG)") (class "Default")
      (node (ref "R16") (pin "1") (pinfunction "1_1") (pintype "passive"))
      (node (ref "U2") (pin "5") (pinfunction "PROG_5") (pintype "bidirectional"))
    )
    (net (code "64") (name "Net-(U2-STAT)") (class "Default")
      (node (ref "R17") (pin "2") (pinfunction "2_2") (pintype "passive"))
      (node (ref "U2") (pin "1") (pinfunction "STAT_1") (pintype "bidirectional"))
    )
    (net (code "65") (name "Net-(U12B-P1.5{slash}UCB0CLK)") (class "Default")
      (node (ref "R27") (pin "2") (pinfunction "2_2") (pintype "passive"))
      (node (ref "U12") (pin "9") (pinfunction "P1.5/UCB0CLK_9") (pintype "bidirectional"))
    )
    (net (code "66") (name "Net-(U12L-DCOR)") (class "Default")
      (node (ref "R26") (pin "2") (pinfunction "2_2") (pintype "passive"))
      (node (ref "U12") (pin "44") (pinfunction "DCOR_44") (pintype "bidirectional"))
    )
    (net (code "67") (name "Net-(U12L-VCORE)") (class "Default")
      (node (ref "C26") (pin "1") (pinfunction "1_1") (pintype "passive"))
      (node (ref "C27") (pin "1") (pinfunction "1_1") (pintype "passive"))
      (node (ref "L1") (pin "2") (pinfunction "2_2") (pintype "passive"))
      (node (ref "U12") (pin "12") (pinfunction "VCORE_12") (pintype "bidirectional"))
    )
    (net (code "68") (name "Net-(U12L-VSW)") (class "Default")
      (node (ref "L1") (pin "1") (pinfunction "1_1") (pintype "passive"))
      (node (ref "U12") (pin "14") (pinfunction "VSW_14") (pintype "bidirectional"))
    )
    (net (code "69") (name "Net-(U16-OSCI)") (class "Default")
      (node (ref "Q9") (pin "2") (pinfunction "2_2") (pintype "passive"))
      (node (ref "U16") (pin "1") (pinfunction "OSCI_1") (pintype "bidirectional"))
    )
    (net (code "70") (name "Net-(U16-OSCO)") (class "Default")
      (node (ref "Q9") (pin "1") (pinfunction "1_1") (pintype "passive"))
      (node (ref "U16") (pin "2") (pinfunction "OSCO_2") (pintype "bidirectional"))
    )
    (net (code "71") (name "P7.5") (class "Default")
      (node (ref "JP3") (pin "9") (pinfunction "9_9") (pintype "bidirectional"))
      (node (ref "U12") (pin "27") (pinfunction "P7.5/PM_TA1.3/C0.4_27") (pintype "bidirectional"))
    )
    (net (code "72") (name "P7.6") (class "Default")
      (node (ref "JP3") (pin "7") (pinfunction "7_7") (pintype "bidirectional"))
      (node (ref "U12") (pin "28") (pinfunction "P7.6/PM_TA1.2/C0.3_28") (pintype "bidirectional"))
    )
    (net (code "73") (name "P7.7") (class "Default")
      (node (ref "JP3") (pin "5") (pinfunction "5_5") (pintype "bidirectional"))
      (node (ref "U12") (pin "29") (pinfunction "P7.7/PM_TA1.1/C0.2_29") (pintype "bidirectional"))
    )
    (net (code "74") (name "P8.0") (class "Default")
      (node (ref "JP3") (pin "3") (pinfunction "3_3") (pintype "bidirectional"))
      (node (ref "U12") (pin "30") (pinfunction "P8.0/UCB3STE/TA1.0/C0.1_30") (pintype "bidirectional"))
    )
    (net (code "75") (name "P8.1") (class "Default")
      (node (ref "JP3") (pin "1") (pinfunction "1_1") (pintype "bidirectional"))
      (node (ref "U12") (pin "31") (pinfunction "P8.1/UCB3CLK/TA2.0/C0.0_31") (pintype "bidirectional"))
    )
    (net (code "76") (name "P10.5") (class "Default")
      (node (ref "JP3") (pin "6") (pinfunction "6_6") (pintype "bidirectional"))
      (node (ref "U12") (pin "25") (pinfunction "P10.5/TA3.1/C0.6_25") (pintype "bidirectional"))
    )
    (net (code "77") (name "PREVGH") (class "Default")
      (node (ref "C48") (pin "1") (pinfunction "1_1") (pintype "passive"))
      (node (ref "D1") (pin "2") (pinfunction "C_2") (pintype "passive"))
      (node (ref "U18") (pin "21") (pinfunction "PREVGH_21") (pintype "bidirectional"))
    )
    (net (code "78") (name "PREVGL") (class "Default")
      (node (ref "C49") (pin "1") (pinfunction "1_1") (pintype "passive"))
      (node (ref "D3") (pin "1") (pinfunction "A_1") (pintype "passive"))
      (node (ref "U18") (pin "23") (pinfunction "PREVGL_23") (pintype "bidirectional"))
    )
    (net (code "79") (name "PT9A") (class "Default")
      (node (ref "JP1") (pin "8") (pinfunction "8_8") (pintype "bidirectional"))
      (node (ref "U1") (pin "88") (pinfunction "PT9A/PCLKT0_1_88") (pintype "bidirectional"))
    )
    (net (code "80") (name "PT9B") (class "Default")
      (node (ref "JP1") (pin "6") (pinfunction "6_6") (pintype "bidirectional"))
      (node (ref "U1") (pin "87") (pinfunction "PT9B/PCLKC0_1_87") (pintype "bidirectional"))
    )
    (net (code "81") (name "PT9C") (class "Default")
      (node (ref "JP1") (pin "4") (pinfunction "4_4") (pintype "bidirectional"))
      (node (ref "U1") (pin "86") (pinfunction "PT9C/SCL/PCLKT0_0_86") (pintype "bidirectional"))
    )
    (net (code "82") (name "PT9D") (class "Default")
      (node (ref "JP1") (pin "2") (pinfunction "2_2") (pintype "bidirectional"))
      (node (ref "U1") (pin "85") (pinfunction "PT9D/SDA/PCLKC0_0_85") (pintype "bidirectional"))
    )
    (net (code "83") (name "PT10A") (class "Default")
      (node (ref "JP1") (pin "3") (pinfunction "3_3") (pintype "bidirectional"))
      (node (ref "U1") (pin "84") (pinfunction "PT10A_84") (pintype "bidirectional"))
    )
    (net (code "84") (name "PT10B") (class "Default")
      (node (ref "JP1") (pin "5") (pinfunction "5_5") (pintype "bidirectional"))
      (node (ref "U1") (pin "83") (pinfunction "PT10B_83") (pintype "bidirectional"))
    )
    (net (code "85") (name "PT10C") (class "Default")
      (node (ref "JP1") (pin "7") (pinfunction "7_7") (pintype "bidirectional"))
      (node (ref "U1") (pin "82") (pinfunction "PT10C/JTAGENB_82") (pintype "bidirectional"))
    )
    (net (code "86") (name "PT10D") (class "Default")
      (node (ref "JP1") (pin "9") (pinfunction "9_9") (pintype "bidirectional"))
      (node (ref "U1") (pin "81") (pinfunction "PT10D/PROGRAMN_81") (pintype "bidirectional"))
    )
    (net (code "87") (name "RESE") (class "Default")
      (node (ref "Q3") (pin "2") (pinfunction "S_2") (pintype "bidirectional"))
      (node (ref "R1") (pin "2") (pinfunction "2_2") (pintype "passive"))
      (node (ref "U18") (pin "3") (pinfunction "RESE_3") (pintype "bidirectional"))
    )
    (net (code "88") (name "RSSI") (class "Default")
      (node (ref "JP26") (pin "6") (pinfunction "RSSI_6") (pintype "bidirectional"))
      (node (ref "R41") (pin "1") (pinfunction "1_1") (pintype "passive"))
    )
    (net (code "89") (name "RTC_CLKOUT") (class "Default")
      (node (ref "TP41") (pin "TP") (pinfunction "TP_TP") (pintype "input"))
      (node (ref "U12") (pin "21") (pinfunction "P2.5/PM_TA0.2_21") (pintype "bidirectional"))
      (node (ref "U16") (pin "8") (pinfunction "CLKOUT_8") (pintype "bidirectional"))
    )
    (net (code "90") (name "RTC_VCAP") (class "Default")
      (node (ref "C68") (pin "1") (pinfunction "1_1") (pintype "passive"))
      (node (ref "R3") (pin "1") (pinfunction "1_1") (pintype "passive"))
    )
    (net (code "91") (name "SPI_CLK") (class "Default")
      (node (ref "TP24") (pin "TP") (pinfunction "TP_TP") (pintype "input"))
      (node (ref "U12") (pin "33") (pinfunction "P3.1/PM_UCA2CLK_33") (pintype "bidirectional"))
      (node (ref "U18") (pin "13") (pinfunction "D0(SCK)_13") (pintype "bidirectional"))
    )
    (net (code "92") (name "SPI_CS_DISPLAY") (class "Default")
      (node (ref "TP28") (pin "TP") (pinfunction "TP_TP") (pintype "input"))
      (node (ref "U12") (pin "37") (pinfunction "P3.5/PM_UCB2CLK_37") (pintype "bidirectional"))
      (node (ref "U18") (pin "12") (pinfunction "~{CS}_12") (pintype "bidirectional"))
    )
    (net (code "93") (name "SPI_CS_FPGA") (class "Default")
      (node (ref "U1") (pin "48") (pinfunction "PB14C/SN_48") (pintype "bidirectional"))
      (node (ref "U12") (pin "38") (pinfunction "P3.6/PM_UCB2SIMO/PM_UCB2SDA_38") (pintype "bidirectional"))
    )
    (net (code "94") (name "SPI_MISO") (class "Default")
      (node (ref "U12") (pin "34") (pinfunction "P3.2/PM_UCA2RXD/PM_UCA2SOMI_34") (pintype "bidirectional"))
    )
    (net (code "95") (name "SPI_MOSI") (class "Default")
      (node (ref "TP26") (pin "TP") (pinfunction "TP_TP") (pintype "input"))
      (node (ref "U12") (pin "35") (pinfunction "P3.3/PM_UCA2TXD/PM_UCA2SIMO_35") (pintype "bidirectional"))
      (node (ref "U18") (pin "14") (pinfunction "D1(MOSI)_14") (pintype "bidirectional"))
    )
    (net (code "96") (name "STATUS_LED") (class "Default")
      (node (ref "JP26") (pin "13") (pinfunction "DIO9_13") (pintype "bidirectional"))
      (node (ref "R40") (pin "1") (pinfunction "1_1") (pintype "passive"))
    )
    (net (code "97") (name "SW") (class "Default")
      (node (ref "C52") (pin "1") (pinfunction "1_1") (pintype "passive"))
      (node (ref "D1") (pin "1") (pinfunction "A_1") (pintype "passive"))
      (node (ref "L2") (pin "1") (pinfunction "1_1") (pintype "passive"))
      (node (ref "Q3") (pin "3") (pinfunction "D_3") (pintype "bidirectional"))
    )
    (net (code "98") (name "SWGL") (class "Default")
      (node (ref "C52") (pin "2") (pinfunction "2_2") (pintype "passive"))
      (node (ref "D3") (pin "2") (pinfunction "C_2") (pintype "passive"))
      (node (ref "D4") (pin "1") (pinfunction "A_1") (pintype "passive"))
    )
    (net (code "99") (name "TCK") (class "Default")
      (node (ref "JP4") (pin "6") (pinfunction "6_6") (pintype "bidirectional"))
      (node (ref "R35") (pin "2") (pinfunction "2_2") (pintype "passive"))
      (node (ref "U1") (pin "91") (pinfunction "PT7C/TCK_91") (pintype "bidirectional"))
    )
    (net (code "100") (name "TDI") (class "Default")
      (node (ref "JP4") (pin "5") (pinfunction "5_5") (pintype "bidirectional"))
      (node (ref "R31") (pin "1") (pinfunction "1_1") (pintype "passive"))
      (node (ref "U1") (pin "94") (pinfunction "PT7B/TDI_94") (pintype "bidirectional"))
    )
    (net (code "101") (name "TDO") (class "Default")
      (node (ref "JP4") (pin "7") (pinfunction "7_7") (pintype "bidirectional"))
      (node (ref "R30") (pin "1") (pinfunction "1_1") (pintype "passive"))
      (node (ref "U1") (pin "95") (pinfunction "PT7A/TDO_95") (pintype "bidirectional"))
    )
    (net (code "102") (name "TMS") (class "Default")
      (node (ref "JP4") (pin "3") (pinfunction "3_3") (pintype "bidirectional"))
      (node (ref "R32") (pin "1") (pinfunction "1_1") (pintype "passive"))
      (node (ref "U1") (pin "90") (pinfunction "PT7D/TMS_90") (pintype "bidirectional"))
    )
    (net (code "103") (name "UART_RX_XBEE") (class "Default")
      (node (ref "JP26") (pin "2") (pinfunction "DOUT_2") (pintype "output"))
      (node (ref "R37") (pin "1") (pinfunction "1_1") (pintype "passive"))
      (node (ref "TP23") (pin "TP") (pinfunction "TP_TP") (pintype "input"))
      (node (ref "U12") (pin "6") (pinfunction "P1.2/UCA0RXD/UCA0SOMI_6") (pintype "bidirectional"))
    )
    (net (code "104") (name "UART_TX_XBEE") (class "Default")
      (node (ref "JP26") (pin "3") (pinfunction "DIN_3") (pintype "input"))
      (node (ref "R38") (pin "1") (pinfunction "1_1") (pintype "passive"))
      (node (ref "TP22") (pin "TP") (pinfunction "TP_TP") (pintype "input"))
      (node (ref "U12") (pin "7") (pinfunction "P1.3/UCA0TXD/UCA0SIMO_7") (pintype "bidirectional"))
    )
    (net (code "105") (name "VCC_DISPLAY") (class "Default")
      (node (ref "C12") (pin "1") (pinfunction "1_1") (pintype "passive"))
      (node (ref "C41") (pin "1") (pinfunction "1_1") (pintype "passive"))
      (node (ref "L2") (pin "2") (pinfunction "2_2") (pintype "passive"))
      (node (ref "R14") (pin "2") (pinfunction "2_2") (pintype "passive"))
      (node (ref "TP9") (pin "TP") (pinfunction "TP_TP") (pintype "input"))
      (node (ref "U18") (pin "15") (pinfunction "VDDIO_15") (pintype "bidirectional"))
      (node (ref "U18") (pin "16") (pinfunction "VCI_16") (pintype "bidirectional"))
      (node (ref "U6") (pin "5") (pinfunction "VOUT_5") (pintype "bidirectional"))
    )
    (net (code "106") (name "VCC_FPGA") (class "Default")
      (node (ref "C15") (pin "1") (pinfunction "1_1") (pintype "passive"))
      (node (ref "C37") (pin "1") (pinfunction "1_1") (pintype "passive"))
      (node (ref "C38") (pin "1") (pinfunction "1_1") (pintype "passive"))
      (node (ref "C42") (pin "1") (pinfunction "1_1") (pintype "passive"))
      (node (ref "C43") (pin "1") (pinfunction "1_1") (pintype "passive"))
      (node (ref "C46") (pin "1") (pinfunction "1_1") (pintype "passive"))
      (node (ref "C47") (pin "1") (pinfunction "1_1") (pintype "passive"))
      (node (ref "C50") (pin "1") (pinfunction "1_1") (pintype "passive"))
      (node (ref "C51") (pin "1") (pinfunction "1_1") (pintype "passive"))
      (node (ref "C54") (pin "1") (pinfunction "1_1") (pintype "passive"))
      (node (ref "C55") (pin "1") (pinfunction "1_1") (pintype "passive"))
      (node (ref "JP1") (pin "1") (pinfunction "1_1") (pintype "bidirectional"))
      (node (ref "JP4") (pin "1") (pinfunction "1_1") (pintype "bidirectional"))
      (node (ref "R11") (pin "2") (pinfunction "2_2") (pintype "passive"))
      (node (ref "R30") (pin "2") (pinfunction "2_2") (pintype "passive"))
      (node (ref "R31") (pin "2") (pinfunction "2_2") (pintype "passive"))
      (node (ref "R32") (pin "2") (pinfunction "2_2") (pintype "passive"))
      (node (ref "TP6") (pin "TP") (pinfunction "TP_TP") (pintype "input"))
      (node (ref "U1") (pin "100") (pinfunction "VCC_100") (pintype "bidirectional"))
      (node (ref "U1") (pin "23") (pinfunction "VCCIO3_23") (pintype "bidirectional"))
      (node (ref "U1") (pin "26") (pinfunction "VCCIO2_26") (pintype "bidirectional"))
      (node (ref "U1") (pin "46") (pinfunction "VCCIO2_46") (pintype "bidirectional"))
      (node (ref "U1") (pin "5") (pinfunction "VCCIO3_5") (pintype "bidirectional"))
      (node (ref "U1") (pin "50") (pinfunction "VCC_50") (pintype "bidirectional"))
      (node (ref "U1") (pin "55") (pinfunction "VCCIO1_55") (pintype "bidirectional"))
      (node (ref "U1") (pin "73") (pinfunction "VCCIO1_73") (pintype "bidirectional"))
      (node (ref "U1") (pin "80") (pinfunction "VCCIO0_80") (pintype "bidirectional"))
      (node (ref "U1") (pin "93") (pinfunction "VCCIO0_93") (pintype "bidirectional"))
      (node (ref "U7") (pin "5") (pinfunction "VOUT_5") (pintype "bidirectional"))
    )
    (net (code "107") (name "VCC_HDC1080") (class "Default")
      (node (ref "C19") (pin "1") (pinfunction "1_1") (pintype "passive"))
      (node (ref "C7") (pin "1") (pinfunction "1_1") (pintype "passive"))
      (node (ref "R8") (pin "2") (pinfunction "2_2") (pintype "passive"))
      (node (ref "TP4") (pin "TP") (pinfunction "TP_TP") (pintype "input"))
      (node (ref "U10") (pin "5") (pinfunction "VDD_5") (pintype "bidirectional"))
      (node (ref "U3") (pin "5") (pinfunction "VOUT_5") (pintype "bidirectional"))
    )
    (net (code "108") (name "VCC_MCU") (class "Default")
      (node (ref "C16") (pin "1") (pinfunction "1_1") (pintype "passive"))
      (node (ref "C28") (pin "1") (pinfunction "1_1") (pintype "passive"))
      (node (ref "C29") (pin "1") (pinfunction "1_1") (pintype "passive"))
      (node (ref "C30") (pin "1") (pinfunction "1_1") (pintype "passive"))
      (node (ref "C31") (pin "1") (pinfunction "1_1") (pintype "passive"))
      (node (ref "C32") (pin "1") (pinfunction "1_1") (pintype "passive"))
      (node (ref "C33") (pin "1") (pinfunction "1_1") (pintype "passive"))
      (node (ref "C34") (pin "1") (pinfunction "1_1") (pintype "passive"))
      (node (ref "C35") (pin "1") (pinfunction "1_1") (pintype "passive"))
      (node (ref "JP3") (pin "10") (pinfunction "10_10") (pintype "bidirectional"))
      (node (ref "JP3") (pin "8") (pinfunction "8_8") (pintype "bidirectional"))
      (node (ref "LED12") (pin "A") (pinfunction "A_A") (pintype "passive"))
      (node (ref "R10") (pin "2") (pinfunction "2_2") (pintype "passive"))
      (node (ref "R18") (pin "1") (pinfunction "1_1") (pintype "passive"))
      (node (ref "R20") (pin "1") (pinfunction "1_1") (pintype "passive"))
      (node (ref "R24") (pin "2") (pinfunction "2_2") (pintype "passive"))
      (node (ref "R25") (pin "2") (pinfunction "2_2") (pintype "passive"))
      (node (ref "TP10") (pin "TP") (pinfunction "TP_TP") (pintype "input"))
      (node (ref "U12") (pin "13") (pinfunction "DVCC1_13") (pintype "bidirectional"))
      (node (ref "U12") (pin "45") (pinfunction "AVCC1_45") (pintype "bidirectional"))
      (node (ref "U12") (pin "73") (pinfunction "DVCC2_73") (pintype "bidirectional"))
      (node (ref "U12") (pin "87") (pinfunction "AVCC2_87") (pintype "bidirectional"))
      (node (ref "U8") (pin "5") (pinfunction "VOUT_5") (pintype "bidirectional"))
    )
    (net (code "109") (name "VCC_MEMORY") (class "Default")
      (node (ref "C53") (pin "1") (pinfunction "1_1") (pintype "passive"))
      (node (ref "C8") (pin "1") (pinfunction "1_1") (pintype "passive"))
      (node (ref "R13") (pin "2") (pinfunction "2_2") (pintype "passive"))
      (node (ref "TP8") (pin "TP") (pinfunction "TP_TP") (pintype "input"))
      (node (ref "U13") (pin "8") (pinfunction "VCC_8") (pintype "bidirectional"))
      (node (ref "U17") (pin "8") (pinfunction "VDD_8") (pintype "bidirectional"))
      (node (ref "U4") (pin "5") (pinfunction "VOUT_5") (pintype "bidirectional"))
    )
    (net (code "110") (name "VCC_OPT3001") (class "Default")
      (node (ref "C11") (pin "1") (pinfunction "1_1") (pintype "passive"))
      (node (ref "C20") (pin "1") (pinfunction "1_1") (pintype "passive"))
      (node (ref "R9") (pin "2") (pinfunction "2_2") (pintype "passive"))
      (node (ref "TP5") (pin "TP") (pinfunction "TP_TP") (pintype "input"))
      (node (ref "U11") (pin "1") (pinfunction "VDD_1") (pintype "bidirectional"))
      (node (ref "U11") (pin "2") (pinfunction "ADDR_2") (pintype "bidirectional"))
      (node (ref "U5") (pin "5") (pinfunction "VOUT_5") (pintype "bidirectional"))
    )
    (net (code "111") (name "VCC_USB") (class "Default")
      (node (ref "C3") (pin "1") (pinfunction "1_1") (pintype "passive"))
      (node (ref "LED11") (pin "A") (pinfunction "A_A") (pintype "passive"))
      (node (ref "R7") (pin "2") (pinfunction "2_2") (pintype "passive"))
      (node (ref "TP3") (pin "TP") (pinfunction "TP_TP") (pintype "input"))
      (node (ref "U2") (pin "4") (pinfunction "VDD_4") (pintype "bidirectional"))
      (node (ref "X1") (pin "1") (pinfunction "1_1") (pintype "passive"))
    )
    (net (code "112") (name "VCC_XBEE") (class "Default")
      (node (ref "C18") (pin "1") (pinfunction "1_1") (pintype "passive"))
      (node (ref "C57") (pin "1") (pinfunction "1_1") (pintype "passive"))
      (node (ref "JP26") (pin "1") (pinfunction "VDD_1") (pintype "power_in"))
      (node (ref "LED14") (pin "A") (pinfunction "A_A") (pintype "passive"))
      (node (ref "LED15") (pin "A") (pinfunction "A_A") (pintype "passive"))
      (node (ref "R12") (pin "2") (pinfunction "2_2") (pintype "passive"))
      (node (ref "TP7") (pin "TP") (pinfunction "TP_TP") (pintype "input"))
      (node (ref "U9") (pin "5") (pinfunction "VOUT_5") (pintype "bidirectional"))
    )
    (net (code "113") (name "VCOM") (class "Default")
      (node (ref "C40") (pin "1") (pinfunction "1_1") (pintype "passive"))
      (node (ref "U18") (pin "24") (pinfunction "VCOM_24") (pintype "bidirectional"))
    )
    (net (code "114") (name "VDD") (class "Default")
      (node (ref "C1") (pin "1") (pinfunction "1_1") (pintype "passive"))
      (node (ref "U18") (pin "18") (pinfunction "VDD_18") (pintype "bidirectional"))
    )
    (net (code "115") (name "VGH") (class "Default")
      (node (ref "C45") (pin "1") (pinfunction "1_1") (pintype "passive"))
      (node (ref "U18") (pin "5") (pinfunction "VGH_5") (pintype "bidirectional"))
    )
    (net (code "116") (name "VGL") (class "Default")
      (node (ref "C44") (pin "1") (pinfunction "1_1") (pintype "passive"))
      (node (ref "U18") (pin "4") (pinfunction "VGL_4") (pintype "bidirectional"))
    )
    (net (code "117") (name "VPP") (class "Default")
      (node (ref "C2") (pin "1") (pinfunction "1_1") (pintype "passive"))
      (node (ref "U18") (pin "19") (pinfunction "VPP_19") (pintype "bidirectional"))
    )
    (net (code "118") (name "VSH") (class "Default")
      (node (ref "C36") (pin "1") (pinfunction "1_1") (pintype "passive"))
      (node (ref "U18") (pin "20") (pinfunction "VSH_20") (pintype "bidirectional"))
    )
    (net (code "119") (name "VSL") (class "Default")
      (node (ref "C39") (pin "1") (pinfunction "1_1") (pintype "passive"))
      (node (ref "U18") (pin "22") (pinfunction "VSL_22") (pintype "bidirectional"))
    )
    (net (code "120") (name "XBEE_CTS") (class "Default")
      (node (ref "JP2") (pin "2") (pinfunction "2_2") (pintype "bidirectional"))
      (node (ref "JP26") (pin "12") (pinfunction "CTS_12") (pintype "output"))
    )
    (net (code "121") (name "XBEE_DTR") (class "Default")
      (node (ref "JP2") (pin "3") (pinfunction "3_3") (pintype "bidirectional"))
      (node (ref "JP26") (pin "9") (pinfunction "DTR_9") (pintype "bidirectional"))
    )
    (net (code "122") (name "XBEE_RESET") (class "Default")
      (node (ref "JP26") (pin "5") (pinfunction "RESET_5") (pintype "input"))
      (node (ref "U12") (pin "26") (pinfunction "P7.4/PM_TA1.4/C0.5_26") (pintype "bidirectional"))
    )
    (net (code "123") (name "XBEE_RTS") (class "Default")
      (node (ref "JP2") (pin "1") (pinfunction "1_1") (pintype "bidirectional"))
      (node (ref "JP26") (pin "16") (pinfunction "RTS_16") (pintype "input"))
    )
    (net (code "124") (name "unconnected-(J1-PAD1-PadNC1)") (class "Default")
      (node (ref "J1") (pin "NC1") (pinfunction "PAD1_NC1") (pintype "bidirectional"))
    )
    (net (code "125") (name "unconnected-(J1-PAD2-PadNC2)") (class "Default")
      (node (ref "J1") (pin "NC2") (pinfunction "PAD2_NC2") (pintype "bidirectional"))
    )
    (net (code "126") (name "unconnected-(JP4-Pad2)") (class "Default")
      (node (ref "JP4") (pin "2") (pinfunction "2_2") (pintype "bidirectional"))
    )
    (net (code "127") (name "unconnected-(JP4-Pad4)") (class "Default")
      (node (ref "JP4") (pin "4") (pinfunction "4_4") (pintype "bidirectional"))
    )
    (net (code "128") (name "unconnected-(JP4-Pad9)") (class "Default")
      (node (ref "JP4") (pin "9") (pinfunction "9_9") (pintype "bidirectional"))
    )
    (net (code "129") (name "unconnected-(JP4-Pad10)") (class "Default")
      (node (ref "JP4") (pin "10") (pinfunction "10_10") (pintype "bidirectional"))
    )
    (net (code "130") (name "unconnected-(JP12-KEY-Pad7)") (class "Default")
      (node (ref "JP12") (pin "7") (pinfunction "KEY_7") (pintype "bidirectional"))
    )
    (net (code "131") (name "unconnected-(JP26-DIO0-Pad20)") (class "Default")
      (node (ref "JP26") (pin "20") (pinfunction "DIO0_20") (pintype "bidirectional"))
    )
    (net (code "132") (name "unconnected-(JP26-DIO1-Pad19)") (class "Default")
      (node (ref "JP26") (pin "19") (pinfunction "DIO1_19") (pintype "bidirectional"))
    )
    (net (code "133") (name "unconnected-(JP26-DIO2-Pad18)") (class "Default")
      (node (ref "JP26") (pin "18") (pinfunction "DIO2_18") (pintype "bidirectional"))
    )
    (net (code "134") (name "unconnected-(JP26-DIO3-Pad17)") (class "Default")
      (node (ref "JP26") (pin "17") (pinfunction "DIO3_17") (pintype "bidirectional"))
    )
    (net (code "135") (name "unconnected-(JP26-DIO4-Pad11)") (class "Default")
      (node (ref "JP26") (pin "11") (pinfunction "DIO4_11") (pintype "bidirectional"))
    )
    (net (code "136") (name "unconnected-(JP26-DIO11-Pad7)") (class "Default")
      (node (ref "JP26") (pin "7") (pinfunction "DIO11_7") (pintype "bidirectional"))
    )
    (net (code "137") (name "unconnected-(JP26-DIO12-Pad4)") (class "Default")
      (node (ref "JP26") (pin "4") (pinfunction "DIO12_4") (pintype "bidirectional"))
    )
    (net (code "138") (name "unconnected-(JP26-RES-Pad8)") (class "Default")
      (node (ref "JP26") (pin "8") (pinfunction "RES_8") (pintype "bidirectional"))
    )
    (net (code "139") (name "unconnected-(JP26-RES-Pad14)") (class "Default")
      (node (ref "JP26") (pin "14") (pinfunction "RES_14") (pintype "bidirectional"))
    )
    (net (code "140") (name "unconnected-(U1A-PB4A{slash}CSSPIN-Pad27)") (class "Default")
      (node (ref "U1") (pin "27") (pinfunction "PB4A/CSSPIN_27") (pintype "bidirectional"))
    )
    (net (code "141") (name "unconnected-(U1A-PB14A-Pad45)") (class "Default")
      (node (ref "U1") (pin "45") (pinfunction "PB14A_45") (pintype "bidirectional"))
    )
    (net (code "142") (name "unconnected-(U1A-PB14B-Pad47)") (class "Default")
      (node (ref "U1") (pin "47") (pinfunction "PB14B_47") (pintype "bidirectional"))
    )
    (net (code "143") (name "unconnected-(U1A-PB14D{slash}SI{slash}SISPI-Pad49)") (class "Default")
      (node (ref "U1") (pin "49") (pinfunction "PB14D/SI/SISPI_49") (pintype "bidirectional"))
    )
    (net (code "144") (name "unconnected-(U1B-PL2A-Pad1)") (class "Default")
      (node (ref "U1") (pin "1") (pinfunction "PL2A_1") (pintype "bidirectional"))
    )
    (net (code "145") (name "unconnected-(U1B-PL2B-Pad2)") (class "Default")
      (node (ref "U1") (pin "2") (pinfunction "PL2B_2") (pintype "bidirectional"))
    )
    (net (code "146") (name "unconnected-(U1B-PL2C{slash}PCLKT3_2-Pad3)") (class "Default")
      (node (ref "U1") (pin "3") (pinfunction "PL2C/PCLKT3_2_3") (pintype "bidirectional"))
    )
    (net (code "147") (name "unconnected-(U1B-PL2D{slash}PCLKC3_2-Pad4)") (class "Default")
      (node (ref "U1") (pin "4") (pinfunction "PL2D/PCLKC3_2_4") (pintype "bidirectional"))
    )
    (net (code "148") (name "unconnected-(U1B-PL3A-Pad7)") (class "Default")
      (node (ref "U1") (pin "7") (pinfunction "PL3A_7") (pintype "bidirectional"))
    )
    (net (code "149") (name "unconnected-(U1B-PL3B-Pad8)") (class "Default")
      (node (ref "U1") (pin "8") (pinfunction "PL3B_8") (pintype "bidirectional"))
    )
    (net (code "150") (name "unconnected-(U1B-PL3C-Pad9)") (class "Default")
      (node (ref "U1") (pin "9") (pinfunction "PL3C_9") (pintype "bidirectional"))
    )
    (net (code "151") (name "unconnected-(U1B-PL3D-Pad10)") (class "Default")
      (node (ref "U1") (pin "10") (pinfunction "PL3D_10") (pintype "bidirectional"))
    )
    (net (code "152") (name "unconnected-(U1B-PL5A{slash}PCLKT3_1-Pad12)") (class "Default")
      (node (ref "U1") (pin "12") (pinfunction "PL5A/PCLKT3_1_12") (pintype "bidirectional"))
    )
    (net (code "153") (name "unconnected-(U1B-PL5B{slash}PCLKC3_1-Pad13)") (class "Default")
      (node (ref "U1") (pin "13") (pinfunction "PL5B/PCLKC3_1_13") (pintype "bidirectional"))
    )
    (net (code "154") (name "unconnected-(U1B-PL5C-Pad14)") (class "Default")
      (node (ref "U1") (pin "14") (pinfunction "PL5C_14") (pintype "bidirectional"))
    )
    (net (code "155") (name "unconnected-(U1B-PL5D-Pad15)") (class "Default")
      (node (ref "U1") (pin "15") (pinfunction "PL5D_15") (pintype "bidirectional"))
    )
    (net (code "156") (name "unconnected-(U1B-PL6A-Pad16)") (class "Default")
      (node (ref "U1") (pin "16") (pinfunction "PL6A_16") (pintype "bidirectional"))
    )
    (net (code "157") (name "unconnected-(U1B-PL6B-Pad17)") (class "Default")
      (node (ref "U1") (pin "17") (pinfunction "PL6B_17") (pintype "bidirectional"))
    )
    (net (code "158") (name "unconnected-(U1B-PL6C-Pad18)") (class "Default")
      (node (ref "U1") (pin "18") (pinfunction "PL6C_18") (pintype "bidirectional"))
    )
    (net (code "159") (name "unconnected-(U1B-PL6D-Pad19)") (class "Default")
      (node (ref "U1") (pin "19") (pinfunction "PL6D_19") (pintype "bidirectional"))
    )
    (net (code "160") (name "unconnected-(U1B-PL7A{slash}PCLKT3_0-Pad20)") (class "Default")
      (node (ref "U1") (pin "20") (pinfunction "PL7A/PCLKT3_0_20") (pintype "bidirectional"))
    )
    (net (code "161") (name "unconnected-(U1B-PL7BPCLKT3_0-Pad21)") (class "Default")
      (node (ref "U1") (pin "21") (pinfunction "PL7BPCLKT3_0_21") (pintype "bidirectional"))
    )
    (net (code "162") (name "unconnected-(U1B-PL7C-Pad24)") (class "Default")
      (node (ref "U1") (pin "24") (pinfunction "PL7C_24") (pintype "bidirectional"))
    )
    (net (code "163") (name "unconnected-(U1B-PL7D-Pad25)") (class "Default")
      (node (ref "U1") (pin "25") (pinfunction "PL7D_25") (pintype "bidirectional"))
    )
    (net (code "164") (name "unconnected-(U1C-PR2A-Pad75)") (class "Default")
      (node (ref "U1") (pin "75") (pinfunction "PR2A_75") (pintype "bidirectional"))
    )
    (net (code "165") (name "unconnected-(U1C-PR2B-Pad74)") (class "Default")
      (node (ref "U1") (pin "74") (pinfunction "PR2B_74") (pintype "bidirectional"))
    )
    (net (code "166") (name "unconnected-(U1C-PR2C-Pad71)") (class "Default")
      (node (ref "U1") (pin "71") (pinfunction "PR2C_71") (pintype "bidirectional"))
    )
    (net (code "167") (name "unconnected-(U1C-PR2D-Pad70)") (class "Default")
      (node (ref "U1") (pin "70") (pinfunction "PR2D_70") (pintype "bidirectional"))
    )
    (net (code "168") (name "unconnected-(U1C-PR3A-Pad69)") (class "Default")
      (node (ref "U1") (pin "69") (pinfunction "PR3A_69") (pintype "bidirectional"))
    )
    (net (code "169") (name "unconnected-(U1C-PR3B-Pad68)") (class "Default")
      (node (ref "U1") (pin "68") (pinfunction "PR3B_68") (pintype "bidirectional"))
    )
    (net (code "170") (name "unconnected-(U1C-PR3C-Pad67)") (class "Default")
      (node (ref "U1") (pin "67") (pinfunction "PR3C_67") (pintype "bidirectional"))
    )
    (net (code "171") (name "unconnected-(U1C-PR3D-Pad66)") (class "Default")
      (node (ref "U1") (pin "66") (pinfunction "PR3D_66") (pintype "bidirectional"))
    )
    (net (code "172") (name "unconnected-(U1C-PR5A-Pad65)") (class "Default")
      (node (ref "U1") (pin "65") (pinfunction "PR5A_65") (pintype "bidirectional"))
    )
    (net (code "173") (name "unconnected-(U1C-PR5B-Pad64)") (class "Default")
      (node (ref "U1") (pin "64") (pinfunction "PR5B_64") (pintype "bidirectional"))
    )
    (net (code "174") (name "unconnected-(U1C-PR5C{slash}PCLKT1_0-Pad63)") (class "Default")
      (node (ref "U1") (pin "63") (pinfunction "PR5C/PCLKT1_0_63") (pintype "bidirectional"))
    )
    (net (code "175") (name "unconnected-(U1C-PR5D{slash}PCLKC1_0-Pad62)") (class "Default")
      (node (ref "U1") (pin "62") (pinfunction "PR5D/PCLKC1_0_62") (pintype "bidirectional"))
    )
    (net (code "176") (name "unconnected-(U1C-PR6A-Pad60)") (class "Default")
      (node (ref "U1") (pin "60") (pinfunction "PR6A_60") (pintype "bidirectional"))
    )
    (net (code "177") (name "unconnected-(U1C-PR6B-Pad59)") (class "Default")
      (node (ref "U1") (pin "59") (pinfunction "PR6B_59") (pintype "bidirectional"))
    )
    (net (code "178") (name "unconnected-(U1C-PR6C-Pad58)") (class "Default")
      (node (ref "U1") (pin "58") (pinfunction "PR6C_58") (pintype "bidirectional"))
    )
    (net (code "179") (name "unconnected-(U1C-PR6D-Pad57)") (class "Default")
      (node (ref "U1") (pin "57") (pinfunction "PR6D_57") (pintype "bidirectional"))
    )
    (net (code "180") (name "unconnected-(U1C-PR7A-Pad54)") (class "Default")
      (node (ref "U1") (pin "54") (pinfunction "PR7A_54") (pintype "bidirectional"))
    )
    (net (code "181") (name "unconnected-(U1C-PR7B-Pad53)") (class "Default")
      (node (ref "U1") (pin "53") (pinfunction "PR7B_53") (pintype "bidirectional"))
    )
    (net (code "182") (name "unconnected-(U1C-PR7C-Pad52)") (class "Default")
      (node (ref "U1") (pin "52") (pinfunction "PR7C_52") (pintype "bidirectional"))
    )
    (net (code "183") (name "unconnected-(U1C-PR7D-Pad51)") (class "Default")
      (node (ref "U1") (pin "51") (pinfunction "PR7D_51") (pintype "bidirectional"))
    )
    (net (code "184") (name "unconnected-(U1D-PT6A-Pad99)") (class "Default")
      (node (ref "U1") (pin "99") (pinfunction "PT6A_99") (pintype "bidirectional"))
    )
    (net (code "185") (name "unconnected-(U1D-PT6B-Pad98)") (class "Default")
      (node (ref "U1") (pin "98") (pinfunction "PT6B_98") (pintype "bidirectional"))
    )
    (net (code "186") (name "unconnected-(U1D-PT6C-Pad97)") (class "Default")
      (node (ref "U1") (pin "97") (pinfunction "PT6C_97") (pintype "bidirectional"))
    )
    (net (code "187") (name "unconnected-(U1D-PT6D-Pad96)") (class "Default")
      (node (ref "U1") (pin "96") (pinfunction "PT6D_96") (pintype "bidirectional"))
    )
    (net (code "188") (name "unconnected-(U1D-PT11A-Pad78)") (class "Default")
      (node (ref "U1") (pin "78") (pinfunction "PT11A_78") (pintype "bidirectional"))
    )
    (net (code "189") (name "unconnected-(U1D-PT11C{slash}INITN-Pad77)") (class "Default")
      (node (ref "U1") (pin "77") (pinfunction "PT11C/INITN_77") (pintype "bidirectional"))
    )
    (net (code "190") (name "unconnected-(U3-NC-Pad4)") (class "Default")
      (node (ref "U3") (pin "4") (pinfunction "NC_4") (pintype "no_connect"))
    )
    (net (code "191") (name "unconnected-(U4-NC-Pad4)") (class "Default")
      (node (ref "U4") (pin "4") (pinfunction "NC_4") (pintype "no_connect"))
    )
    (net (code "192") (name "unconnected-(U5-NC-Pad4)") (class "Default")
      (node (ref "U5") (pin "4") (pinfunction "NC_4") (pintype "no_connect"))
    )
    (net (code "193") (name "unconnected-(U6-NC-Pad4)") (class "Default")
      (node (ref "U6") (pin "4") (pinfunction "NC_4") (pintype "no_connect"))
    )
    (net (code "194") (name "unconnected-(U7-NC-Pad4)") (class "Default")
      (node (ref "U7") (pin "4") (pinfunction "NC_4") (pintype "no_connect"))
    )
    (net (code "195") (name "unconnected-(U8-NC-Pad4)") (class "Default")
      (node (ref "U8") (pin "4") (pinfunction "NC_4") (pintype "no_connect"))
    )
    (net (code "196") (name "unconnected-(U9-NC-Pad4)") (class "Default")
      (node (ref "U9") (pin "4") (pinfunction "NC_4") (pintype "no_connect"))
    )
    (net (code "197") (name "unconnected-(U10-NC-Pad3)") (class "Default")
      (node (ref "U10") (pin "3") (pinfunction "NC_3") (pintype "no_connect"))
    )
    (net (code "198") (name "unconnected-(U10-NC-Pad4)") (class "Default")
      (node (ref "U10") (pin "4") (pinfunction "NC_4") (pintype "no_connect"))
    )
    (net (code "199") (name "unconnected-(U12B-P1.4{slash}UCB0STE-Pad8)") (class "Default")
      (node (ref "U12") (pin "8") (pinfunction "P1.4/UCB0STE_8") (pintype "bidirectional"))
    )
    (net (code "200") (name "unconnected-(U12C-P10.0{slash}UCB3STE-Pad100)") (class "Default")
      (node (ref "U12") (pin "100") (pinfunction "P10.0/UCB3STE_100") (pintype "bidirectional"))
    )
    (net (code "201") (name "unconnected-(U12C-P10.1{slash}UCB3CLK-Pad1)") (class "Default")
      (node (ref "U12") (pin "1") (pinfunction "P10.1/UCB3CLK_1") (pintype "bidirectional"))
    )
    (net (code "202") (name "unconnected-(U12C-P10.2{slash}UCB3SIMO{slash}UCB3SDA-Pad2)") (class "Default")
      (node (ref "U12") (pin "2") (pinfunction "P10.2/UCB3SIMO/UCB3SDA_2") (pintype "bidirectional"))
    )
    (net (code "203") (name "unconnected-(U12C-P10.3{slash}UCB3SOMI{slash}UCB3SCL-Pad3)") (class "Default")
      (node (ref "U12") (pin "3") (pinfunction "P10.3/UCB3SOMI/UCB3SCL_3") (pintype "bidirectional"))
    )
    (net (code "204") (name "unconnected-(U12F-P4.0{slash}A13-Pad56)") (class "Default")
      (node (ref "U12") (pin "56") (pinfunction "P4.0/A13_56") (pintype "bidirectional"))
    )
    (net (code "205") (name "unconnected-(U12F-P4.1{slash}A12-Pad57)") (class "Default")
      (node (ref "U12") (pin "57") (pinfunction "P4.1/A12_57") (pintype "bidirectional"))
    )
    (net (code "206") (name "unconnected-(U12H-P6.0{slash}A15-Pad54)") (class "Default")
      (node (ref "U12") (pin "54") (pinfunction "P6.0/A15_54") (pintype "bidirectional"))
    )
    (net (code "207") (name "unconnected-(U12H-P6.1{slash}A14-Pad55)") (class "Default")
      (node (ref "U12") (pin "55") (pinfunction "P6.1/A14_55") (pintype "bidirectional"))
    )
    (net (code "208") (name "unconnected-(U12H-P6.7{slash}TA2.4{slash}UCB3SOMI{slash}UCB3SCL{slash}C1.0-Pad81)") (class "Default")
      (node (ref "U12") (pin "81") (pinfunction "P6.7/TA2.4/UCB3SOMI/UCB3SCL/C1.0_81") (pintype "bidirectional"))
    )
    (net (code "209") (name "unconnected-(U12I-P7.0{slash}PM_SMCLK{slash}PM_DMAE0-Pad88)") (class "Default")
      (node (ref "U12") (pin "88") (pinfunction "P7.0/PM_SMCLK/PM_DMAE0_88") (pintype "bidirectional"))
    )
    (net (code "210") (name "unconnected-(U12I-P7.1{slash}PM_C0OUT{slash}PM_TA0CLK-Pad89)") (class "Default")
      (node (ref "U12") (pin "89") (pinfunction "P7.1/PM_C0OUT/PM_TA0CLK_89") (pintype "bidirectional"))
    )
    (net (code "211") (name "unconnected-(U12I-P7.2{slash}PM_C1OUT{slash}PM_TA1CLK-Pad90)") (class "Default")
      (node (ref "U12") (pin "90") (pinfunction "P7.2/PM_C1OUT/PM_TA1CLK_90") (pintype "bidirectional"))
    )
    (net (code "212") (name "unconnected-(U12I-P7.3{slash}PM_TA0.0-Pad91)") (class "Default")
      (node (ref "U12") (pin "91") (pinfunction "P7.3/PM_TA0.0_91") (pintype "bidirectional"))
    )
    (net (code "213") (name "unconnected-(U12J-P8.4{slash}A21-Pad48)") (class "Default")
      (node (ref "U12") (pin "48") (pinfunction "P8.4/A21_48") (pintype "bidirectional"))
    )
    (net (code "214") (name "unconnected-(U12J-P8.5{slash}A20-Pad49)") (class "Default")
      (node (ref "U12") (pin "49") (pinfunction "P8.5/A20_49") (pintype "bidirectional"))
    )
    (net (code "215") (name "unconnected-(U12J-P8.6{slash}A19-Pad50)") (class "Default")
      (node (ref "U12") (pin "50") (pinfunction "P8.6/A19_50") (pintype "bidirectional"))
    )
    (net (code "216") (name "unconnected-(U12J-P8.7{slash}A18-Pad51)") (class "Default")
      (node (ref "U12") (pin "51") (pinfunction "P8.7/A18_51") (pintype "bidirectional"))
    )
    (net (code "217") (name "unconnected-(U12K-P9.0{slash}A17-Pad52)") (class "Default")
      (node (ref "U12") (pin "52") (pinfunction "P9.0/A17_52") (pintype "bidirectional"))
    )
    (net (code "218") (name "unconnected-(U12K-P9.1{slash}A16-Pad53)") (class "Default")
      (node (ref "U12") (pin "53") (pinfunction "P9.1/A16_53") (pintype "bidirectional"))
    )
    (net (code "219") (name "unconnected-(U12K-P9.4{slash}UCA3STE-Pad96)") (class "Default")
      (node (ref "U12") (pin "96") (pinfunction "P9.4/UCA3STE_96") (pintype "bidirectional"))
    )
    (net (code "220") (name "unconnected-(U12K-P9.5{slash}UCA3CLK-Pad97)") (class "Default")
      (node (ref "U12") (pin "97") (pinfunction "P9.5/UCA3CLK_97") (pintype "bidirectional"))
    )
    (net (code "221") (name "unconnected-(U12K-P9.6{slash}UCA3RXD{slash}UCA3SOMI-Pad98)") (class "Default")
      (node (ref "U12") (pin "98") (pinfunction "P9.6/UCA3RXD/UCA3SOMI_98") (pintype "bidirectional"))
    )
    (net (code "222") (name "unconnected-(U12K-P9.7{slash}UCA3TXD{slash}UCA3SIMO-Pad99)") (class "Default")
      (node (ref "U12") (pin "99") (pinfunction "P9.7/UCA3TXD/UCA3SIMO_99") (pintype "bidirectional"))
    )
    (net (code "223") (name "unconnected-(U16-NC-Pad3)") (class "Default")
      (node (ref "U16") (pin "3") (pinfunction "NC_3") (pintype "no_connect"))
    )
    (net (code "224") (name "unconnected-(U16-NC-Pad6)") (class "Default")
      (node (ref "U16") (pin "6") (pinfunction "NC_6") (pintype "bidirectional"))
    )
    (net (code "225") (name "unconnected-(U16-NC-Pad9)") (class "Default")
      (node (ref "U16") (pin "9") (pinfunction "NC_9") (pintype "no_connect"))
    )
    (net (code "226") (name "unconnected-(U16-NC-Pad12)") (class "Default")
      (node (ref "U16") (pin "12") (pinfunction "NC_12") (pintype "no_connect"))
    )
    (net (code "227") (name "unconnected-(U18-NC-Pad1)") (class "Default")
      (node (ref "U18") (pin "1") (pinfunction "NC_1") (pintype "bidirectional"))
    )
    (net (code "228") (name "unconnected-(U18-TSCL-Pad6)") (class "Default")
      (node (ref "U18") (pin "6") (pinfunction "TSCL_6") (pintype "bidirectional"))
    )
    (net (code "229") (name "unconnected-(U18-TSDA-Pad7)") (class "Default")
      (node (ref "U18") (pin "7") (pinfunction "TSDA_7") (pintype "bidirectional"))
    )
    (net (code "230") (name "unconnected-(X1-Pad2)") (class "Default")
      (node (ref "X1") (pin "2") (pinfunction "2_2") (pintype "passive"))
    )
    (net (code "231") (name "unconnected-(X1-Pad3)") (class "Default")
      (node (ref "X1") (pin "3") (pinfunction "3_3") (pintype "passive"))
    )
    (net (code "232") (name "unconnected-(X1-Pad4)") (class "Default")
      (node (ref "X1") (pin "4") (pinfunction "4_4") (pintype "passive"))
    )
    (net (code "233") (name "~{FLASH_HOLD}") (class "Default")
      (node (ref "TP35") (pin "TP") (pinfunction "TP_TP") (pintype "input"))
      (node (ref "U12") (pin "75") (pinfunction "P9.3/TA3.4_75") (pintype "bidirectional"))
      (node (ref "U13") (pin "7") (pinfunction "~{HOLD}(IO3)_7") (pintype "bidirectional"))
    )
    (net (code "234") (name "~{FLASH_WP}") (class "Default")
      (node (ref "TP33") (pin "TP") (pinfunction "TP_TP") (pintype "input"))
      (node (ref "U12") (pin "80") (pinfunction "P6.6/TA2.3/UCB3SIMO/UCB3SDA/C1.1_80") (pintype "bidirectional"))
      (node (ref "U13") (pin "3") (pinfunction "~{WP}(IO2)_3") (pintype "bidirectional"))
    )
    (net (code "235") (name "~{RST}") (class "Default")
      (node (ref "C21") (pin "1") (pinfunction "1_1") (pintype "passive"))
      (node (ref "JP12") (pin "10") (pinfunction "NRESET_10") (pintype "bidirectional"))
      (node (ref "R20") (pin "2") (pinfunction "2_2") (pintype "passive"))
      (node (ref "SW1") (pin "1") (pinfunction "1_1") (pintype "passive"))
      (node (ref "SW1") (pin "2") (pinfunction "2_2") (pintype "passive"))
      (node (ref "TP19") (pin "TP") (pinfunction "TP_TP") (pintype "input"))
      (node (ref "U12") (pin "83") (pinfunction "RSTN/NMI_83") (pintype "bidirectional"))
    )
    (net (code "236") (name "~{RTC_INT1}") (class "Default")
      (node (ref "TP40") (pin "TP") (pinfunction "TP_TP") (pintype "input"))
      (node (ref "U12") (pin "22") (pinfunction "P2.6/PM_TA0.3_22") (pintype "bidirectional"))
      (node (ref "U16") (pin "13") (pinfunction "~{INT1}_13") (pintype "bidirectional"))
    )
    (net (code "237") (name "~{RTC_INT2}") (class "Default")
      (node (ref "TP42") (pin "TP") (pinfunction "TP_TP") (pintype "input"))
      (node (ref "U12") (pin "24") (pinfunction "P10.4/TA3.0/C0.7_24") (pintype "bidirectional"))
      (node (ref "U16") (pin "7") (pinfunction "~{INT2}_7") (pintype "bidirectional"))
    )
  )
)
